# V4.net
KiCad netlist of a schematic drawn in Altium Designer
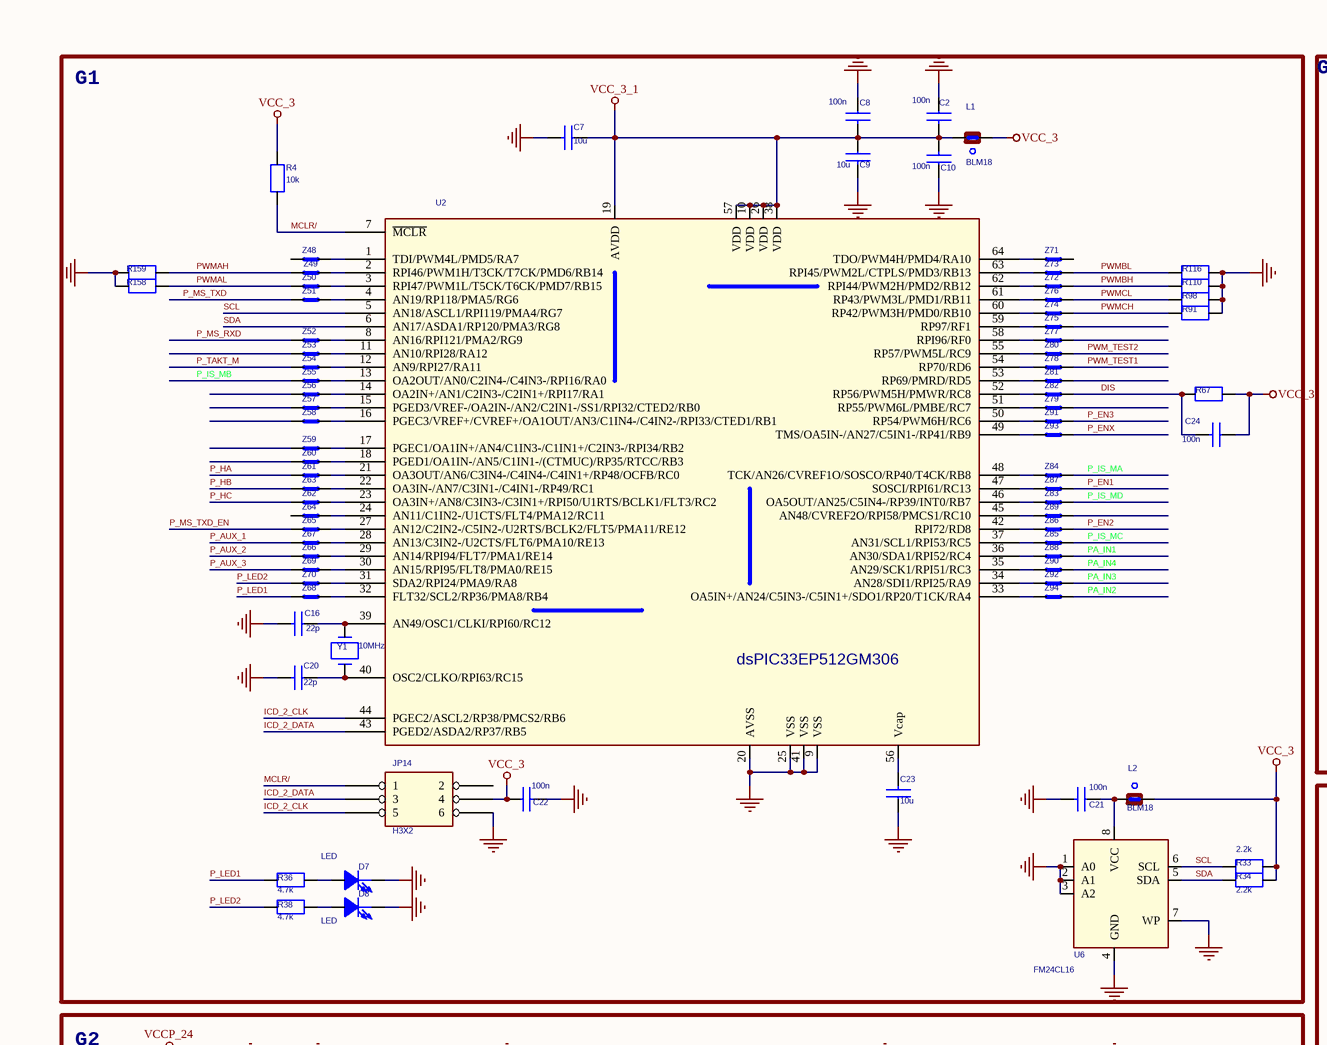
[diagram p0: V4.SchDoc, top left]
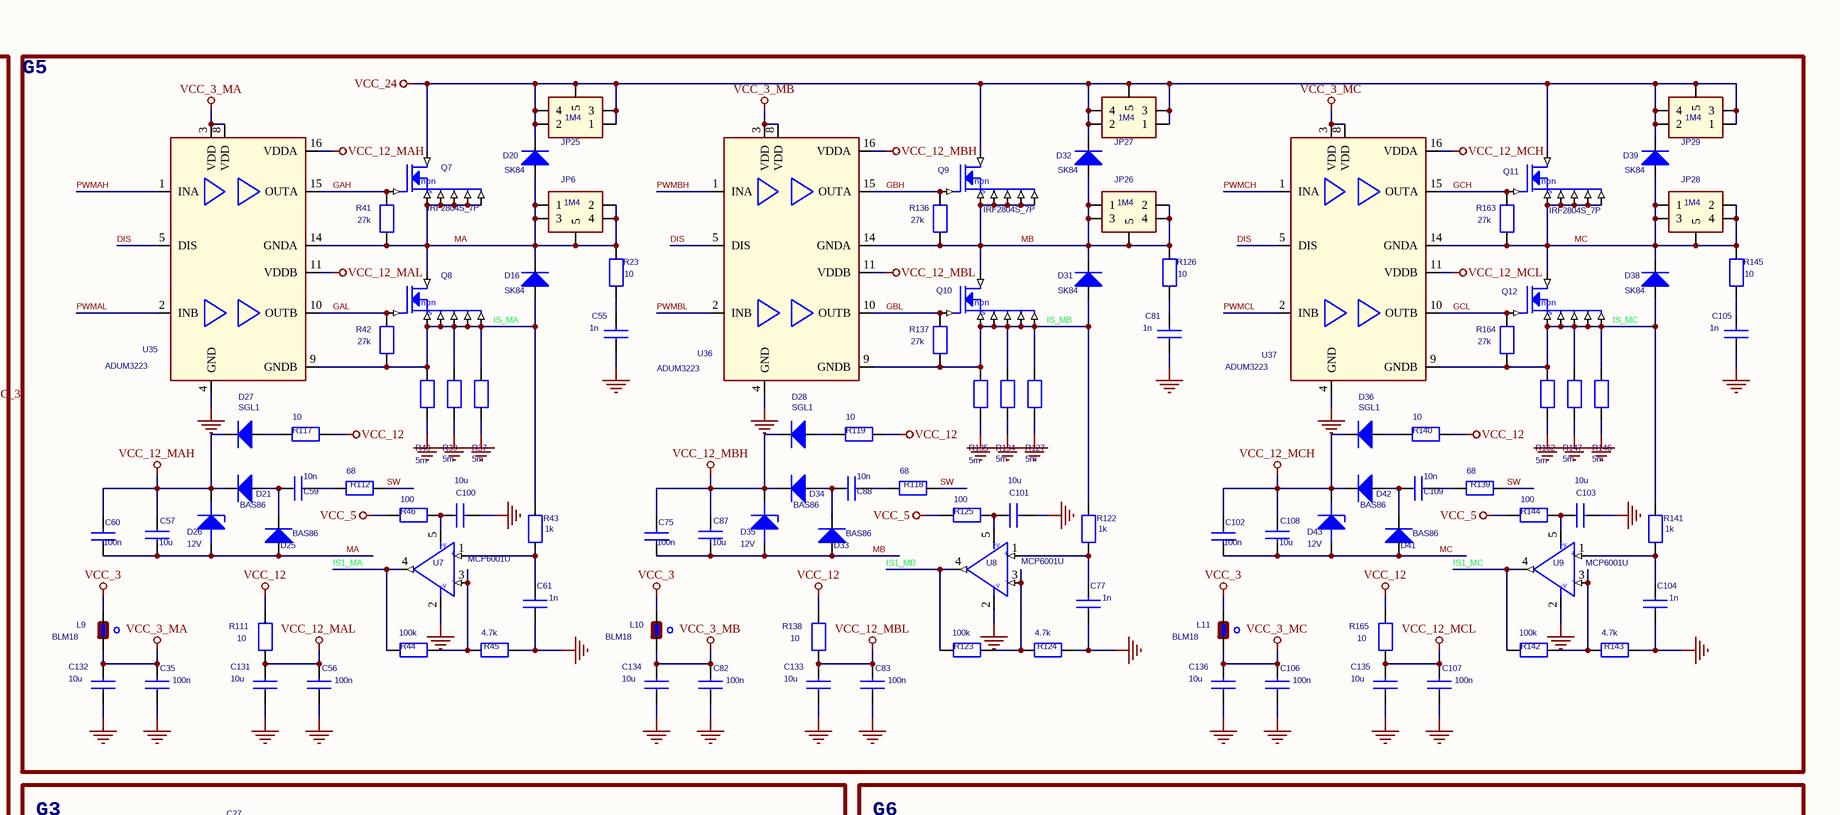
[diagram p1: V4.SchDoc, top right]
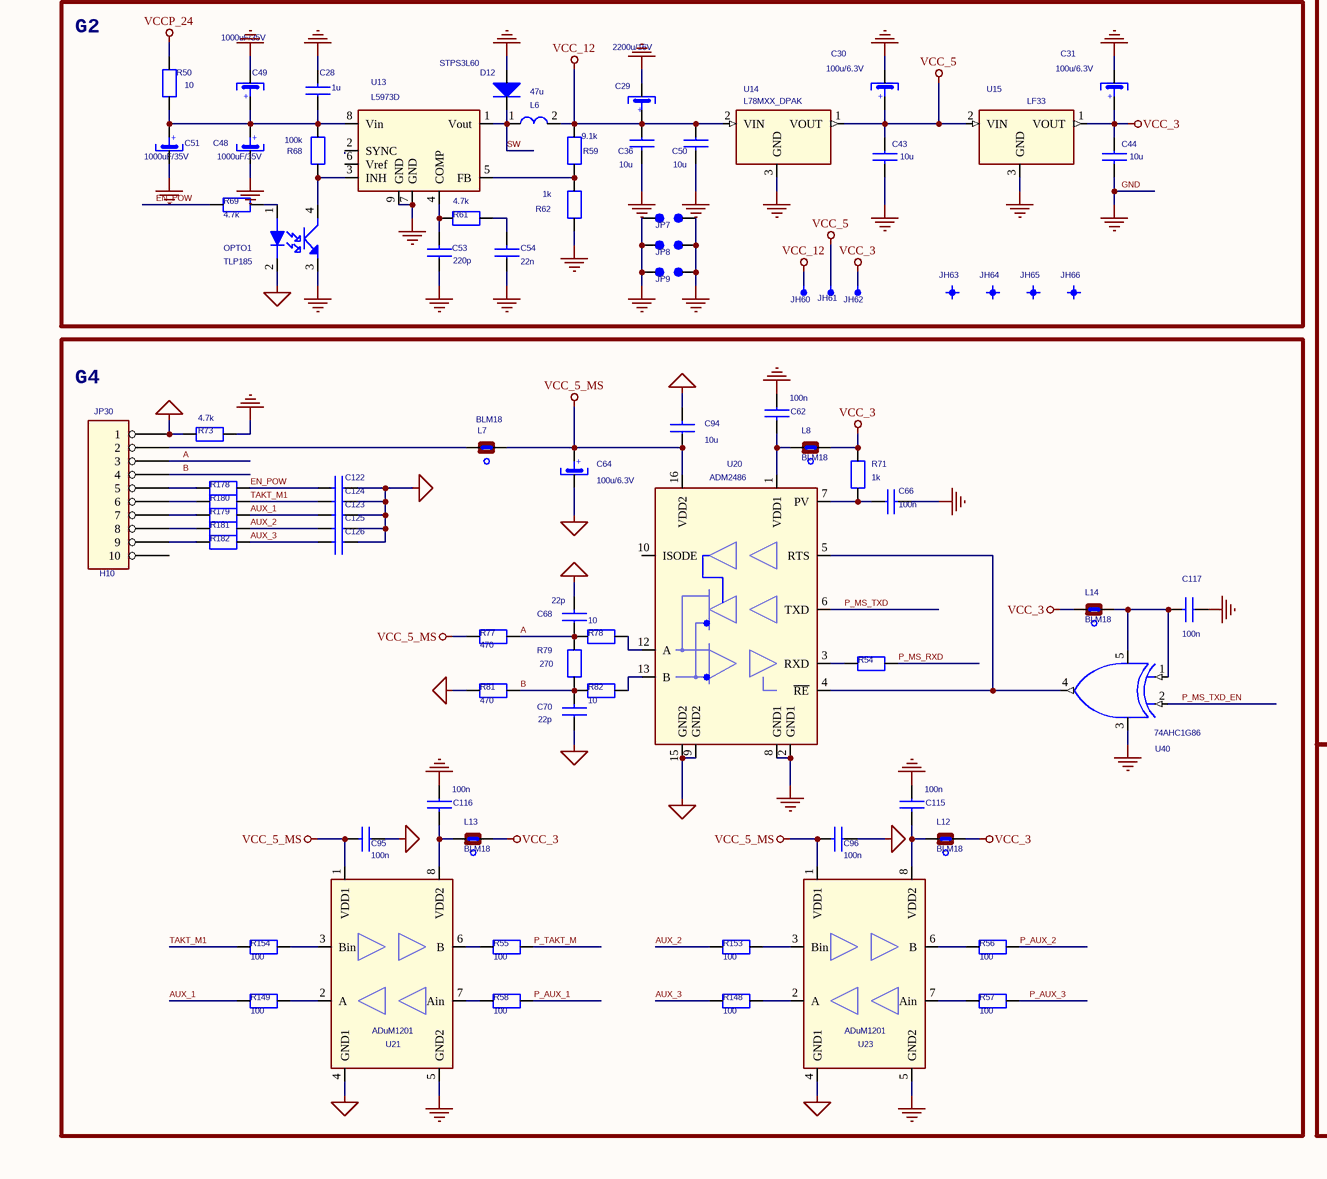
[diagram p2: V4.SchDoc, bottom left]
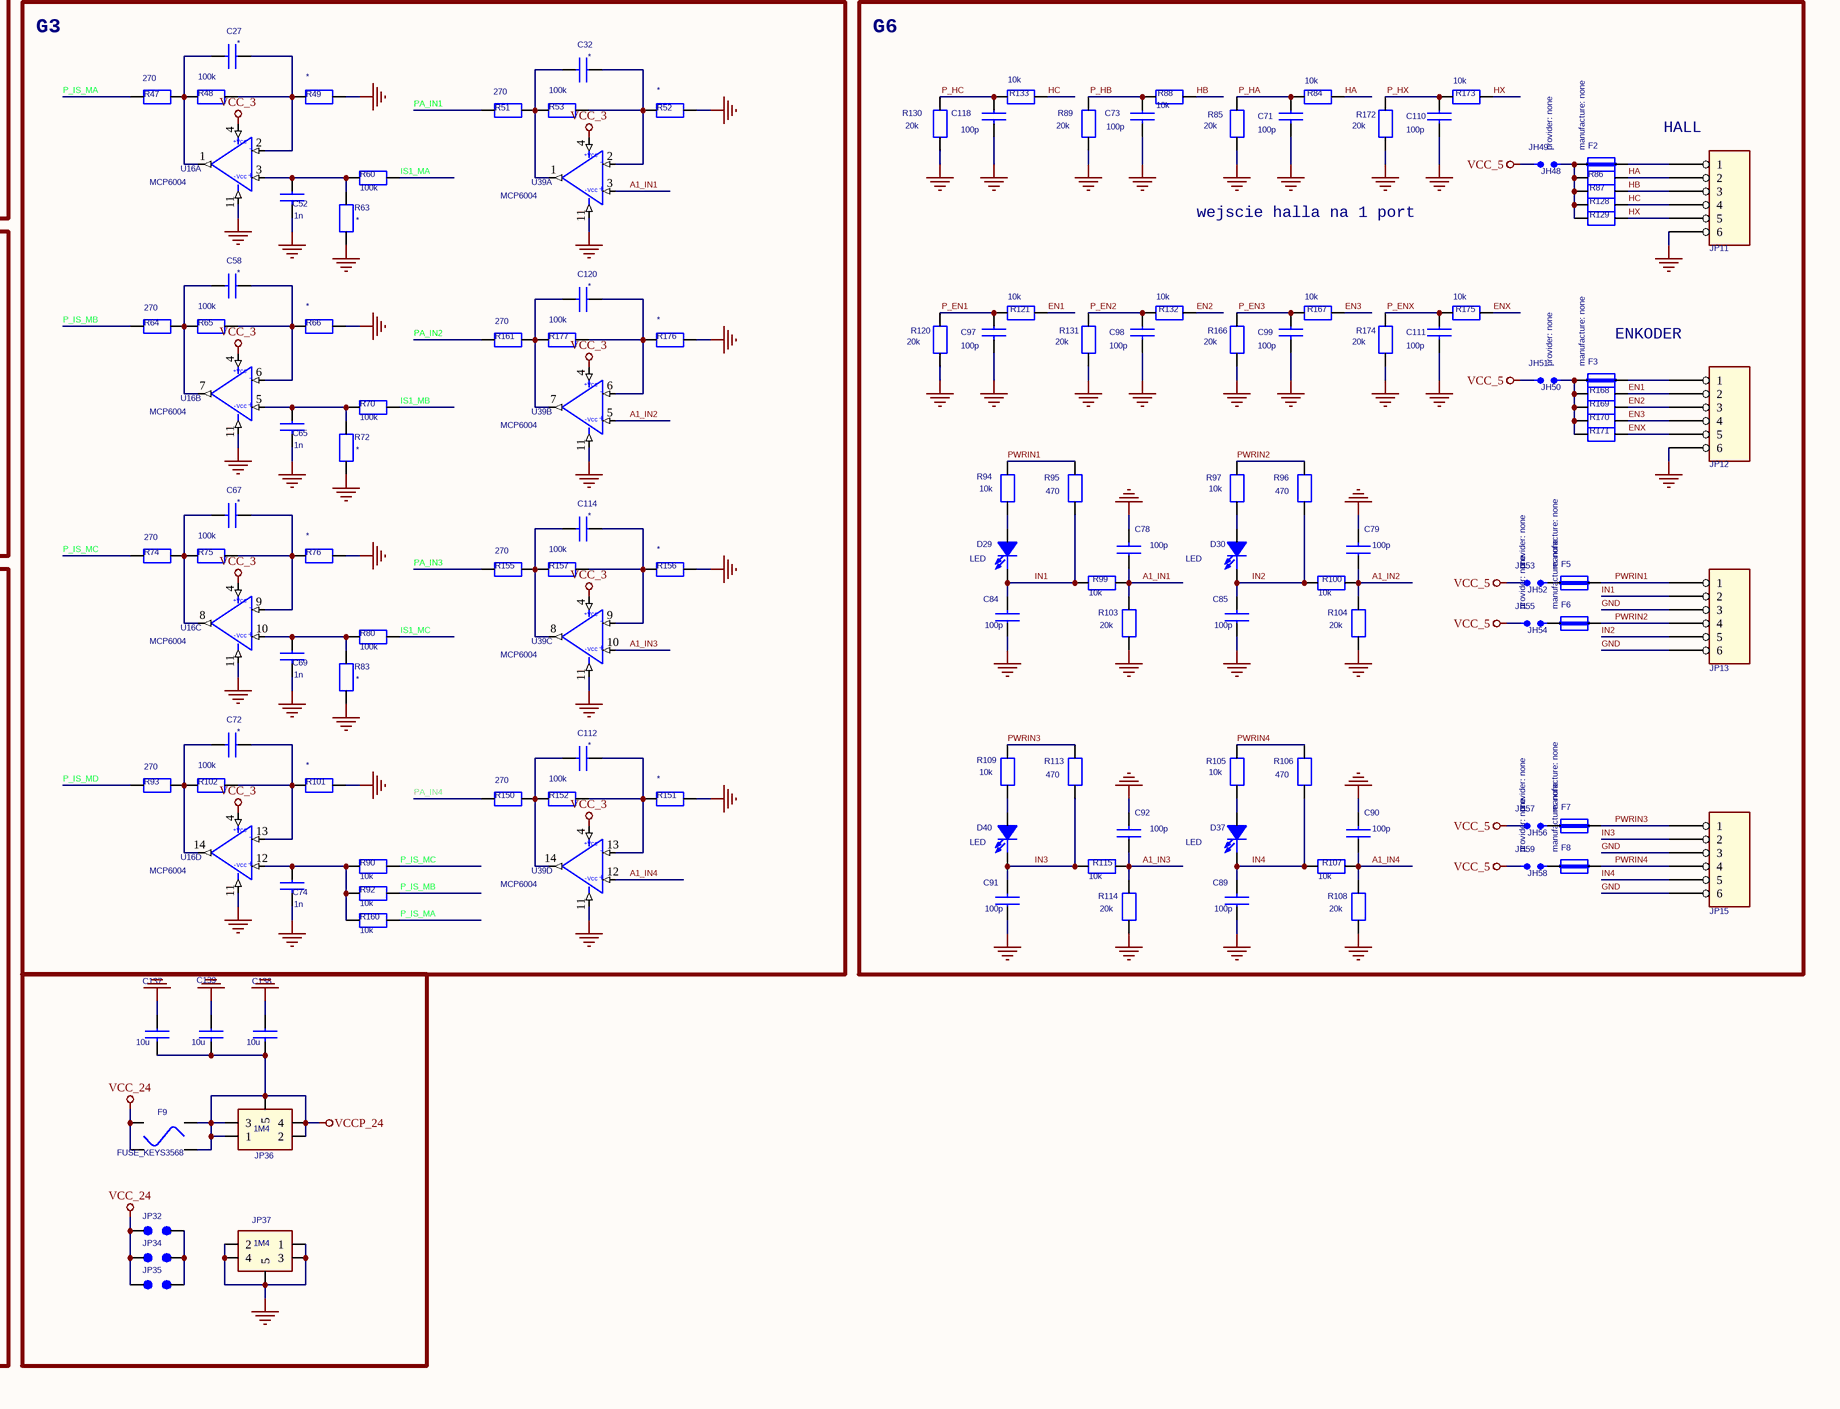
[diagram p3: V4.SchDoc, bottom right]

(export (version "E")
  (design (tool "Eeschema 10.0.6"))
  (components
    (comp (ref "C2")
      (value "100n")
      (footprint "0805")
      (description "100nF 0603 16V  X7R 10%")
      (fields (field (name "PROVIDER") "TME CL10B104KO8NNNC"))
      (libsource (lib "*") (part "C"))
    )
    (comp (ref "C7")
      (value "10u")
      (footprint "0805")
      (description "10uF 0603 6.3V 10% X5R")
      (fields (field (name "PROVIDER") "TME CL10A106KQ8NNNC"))
      (libsource (lib "*") (part "C"))
    )
    (comp (ref "C8") (value "100n") (footprint "0805") (libsource (lib "*") (part "C")))
    (comp (ref "C9")
      (value "10u")
      (footprint "0805")
      (description "10uF 0603 6.3V 10% X5R")
      (fields (field (name "PROVIDER") "TME CL10A106KQ8NNNC"))
      (libsource (lib "*") (part "C"))
    )
    (comp (ref "C10")
      (value "100n")
      (footprint "0805")
      (description "100nF 0603 16V  X7R 10%")
      (fields (field (name "PROVIDER") "TME CL10B104KO8NNNC"))
      (libsource (lib "*") (part "C"))
    )
    (comp (ref "C16")
      (value "22p")
      (footprint "0805")
      (description "22p 0603 50V C0G 5%")
      (fields (field (name "PROVIDER") "TME CL10C220JB8NNNC"))
      (libsource (lib "*") (part "C"))
    )
    (comp (ref "C20")
      (value "22p")
      (footprint "0805")
      (description "22p 0603 50V C0G 5%")
      (fields (field (name "PROVIDER") "TME CL10C220JB8NNNC"))
      (libsource (lib "*") (part "C"))
    )
    (comp (ref "C21") (value "100n") (footprint "0805") (libsource (lib "*") (part "C")))
    (comp (ref "C22")
      (value "100n")
      (footprint "0805")
      (description "100nF 0603 16V  X7R 10%")
      (fields (field (name "PROVIDER") "TME CL10B104KO8NNNC"))
      (libsource (lib "*") (part "C"))
    )
    (comp (ref "C23")
      (value "10u")
      (footprint "0805")
      (description "10uF 0603 6.3V 10% X5R")
      (fields (field (name "PROVIDER") "TME CL10A106KQ8NNNC"))
      (libsource (lib "*") (part "C"))
    )
    (comp (ref "C24") (value "100n") (footprint "0805") (libsource (lib "*") (part "C")))
    (comp (ref "C27")
      (value "*")
      (footprint "0805")
      (description "10nF 0603 50V X7R 10%")
      (fields (field (name "PROVIDER") "TME CL10B103KB8NNNC"))
      (libsource (lib "*") (part "C"))
    )
    (comp (ref "C28")
      (value "1u")
      (footprint "0805")
      (description "1u 1206 50V X7R 10%")
      (fields (field (name "PROVIDER") "TME CL31B105KBHNNNE"))
      (libsource (lib "*") (part "C"))
    )
    (comp (ref "C29")
      (value "2200u/16V")
      (description "2200u 16V LI 105C")
      (fields (field (name "PROVIDER") "TME GF2200/16"))
      (libsource (lib "*") (part "EL"))
    )
    (comp (ref "C30")
      (value "100u/6.3V")
      (description "100U 6.3V B LI 0.25")
      (fields (field (name "PROVIDER") "TME TPSB107K006R0250"))
      (libsource (lib "*") (part "EL"))
    )
    (comp (ref "C31")
      (value "100u/6.3V")
      (description "100U 6.3V B LI 0.25")
      (fields (field (name "PROVIDER") "TME TPSB107K006R0250"))
      (libsource (lib "*") (part "EL"))
    )
    (comp (ref "C32")
      (value "*")
      (footprint "0805")
      (description "10nF 0603 50V X7R 10%")
      (fields (field (name "PROVIDER") "TME CL10B103KB8NNNC"))
      (libsource (lib "*") (part "C"))
    )
    (comp (ref "C35") (value "100n") (footprint "0805") (libsource (lib "*") (part "C")))
    (comp (ref "C36") (value "10u") (footprint "0805") (libsource (lib "*") (part "C")))
    (comp (ref "C43")
      (value "10u")
      (footprint "0805")
      (description "10uF 0603 6.3V 10% X5R")
      (fields (field (name "PROVIDER") "TME CL10A106KQ8NNNC"))
      (libsource (lib "*") (part "C"))
    )
    (comp (ref "C44")
      (value "10u")
      (footprint "0805")
      (description "10uF 0603 6.3V 10% X5R")
      (fields (field (name "PROVIDER") "TME CL10A106KQ8NNNC"))
      (libsource (lib "*") (part "C"))
    )
    (comp (ref "C48")
      (value "1000uF/35V")
      (footprint "CE_16/RM7.5MM")
      (libsource (lib "*") (part "CE 2200uF/35V ST"))
    )
    (comp (ref "C49")
      (value "1000uF/35V")
      (footprint "CE_16/RM7.5MM")
      (libsource (lib "*") (part "CE 2200uF/35V ST"))
    )
    (comp (ref "C50") (value "10u") (footprint "0805") (libsource (lib "*") (part "C")))
    (comp (ref "C51")
      (value "1000uF/35V")
      (footprint "CE_16/RM7.5MM")
      (libsource (lib "*") (part "CE 2200uF/35V ST"))
    )
    (comp (ref "C52") (value "1n") (footprint "0805") (libsource (lib "*") (part "C")))
    (comp (ref "C53")
      (value "220p")
      (footprint "0805")
      (description "220p 0805 50V C0G 5%")
      (fields (field (name "PROVIDER") "TME CL21C221JBANNNC"))
      (libsource (lib "*") (part "C"))
    )
    (comp (ref "C54")
      (value "22n")
      (footprint "0805")
      (description "22n 0805 50V X7R 10%")
      (fields (field (name "PROVIDER") "TME CL21B223KBANNNC"))
      (libsource (lib "*") (part "C"))
    )
    (comp (ref "C55") (value "1n") (footprint "0805") (libsource (lib "*") (part "C")))
    (comp (ref "C56") (value "100n") (footprint "0805") (libsource (lib "*") (part "C")))
    (comp (ref "C57") (value "10u") (footprint "0805") (libsource (lib "*") (part "C")))
    (comp (ref "C58")
      (value "*")
      (footprint "0805")
      (description "10nF 0603 50V X7R 10%")
      (fields (field (name "PROVIDER") "TME CL10B103KB8NNNC"))
      (libsource (lib "*") (part "C"))
    )
    (comp (ref "C59") (value "10n") (footprint "0805") (libsource (lib "*") (part "C")))
    (comp (ref "C60") (value "100n") (footprint "0805") (libsource (lib "*") (part "C")))
    (comp (ref "C61")
      (value "1n")
      (footprint "0805")
      (description "1n 0603 50V 5% C0G")
      (fields (field (name "PROVIDER") "TME CL10C102JB8NNNC"))
      (libsource (lib "*") (part "C"))
    )
    (comp (ref "C62") (value "100n") (footprint "0805") (libsource (lib "*") (part "C")))
    (comp (ref "C64")
      (value "100u/6.3V")
      (description "100U 6.3V B LI 0.25")
      (fields (field (name "PROVIDER") "TME TPSB107K006R0250"))
      (libsource (lib "*") (part "EL"))
    )
    (comp (ref "C65") (value "1n") (footprint "0805") (libsource (lib "*") (part "C")))
    (comp (ref "C66") (value "100n") (footprint "0805") (libsource (lib "*") (part "C")))
    (comp (ref "C67")
      (value "*")
      (footprint "0805")
      (description "10nF 0603 50V X7R 10%")
      (fields (field (name "PROVIDER") "TME CL10B103KB8NNNC"))
      (libsource (lib "*") (part "C"))
    )
    (comp (ref "C68") (value "22p") (footprint "0805") (libsource (lib "*") (part "C")))
    (comp (ref "C69") (value "1n") (footprint "0805") (libsource (lib "*") (part "C")))
    (comp (ref "C70") (value "22p") (footprint "0805") (libsource (lib "*") (part "C")))
    (comp (ref "C71")
      (value "100p")
      (footprint "0805")
      (description "10nF 0603 50V X7R 10%")
      (fields (field (name "PROVIDER") "TME CL10B103KB8NNNC"))
      (libsource (lib "*") (part "C"))
    )
    (comp (ref "C72")
      (value "*")
      (footprint "0805")
      (description "10nF 0603 50V X7R 10%")
      (fields (field (name "PROVIDER") "TME CL10B103KB8NNNC"))
      (libsource (lib "*") (part "C"))
    )
    (comp (ref "C73")
      (value "100p")
      (footprint "0805")
      (description "10nF 0603 50V X7R 10%")
      (fields (field (name "PROVIDER") "TME CL10B103KB8NNNC"))
      (libsource (lib "*") (part "C"))
    )
    (comp (ref "C74") (value "1n") (footprint "0805") (libsource (lib "*") (part "C")))
    (comp (ref "C75") (value "100n") (footprint "0805") (libsource (lib "*") (part "C")))
    (comp (ref "C77")
      (value "1n")
      (footprint "0805")
      (description "1n 0603 50V 5% C0G")
      (fields (field (name "PROVIDER") "TME CL10C102JB8NNNC"))
      (libsource (lib "*") (part "C"))
    )
    (comp (ref "C78")
      (value "100p")
      (footprint "0805")
      (description "10nF 0603 50V X7R 10%")
      (fields (field (name "PROVIDER") "TME CL10B103KB8NNNC"))
      (libsource (lib "*") (part "C"))
    )
    (comp (ref "C79")
      (value "100p")
      (footprint "0805")
      (description "10nF 0603 50V X7R 10%")
      (fields (field (name "PROVIDER") "TME CL10B103KB8NNNC"))
      (libsource (lib "*") (part "C"))
    )
    (comp (ref "C81") (value "1n") (footprint "0805") (libsource (lib "*") (part "C")))
    (comp (ref "C82") (value "100n") (footprint "0805") (libsource (lib "*") (part "C")))
    (comp (ref "C83") (value "100n") (footprint "0805") (libsource (lib "*") (part "C")))
    (comp (ref "C84") (value "100p") (footprint "0805") (libsource (lib "*") (part "C")))
    (comp (ref "C85") (value "100p") (footprint "0805") (libsource (lib "*") (part "C")))
    (comp (ref "C87") (value "10u") (footprint "0805") (libsource (lib "*") (part "C")))
    (comp (ref "C88") (value "10n") (footprint "0805") (libsource (lib "*") (part "C")))
    (comp (ref "C89") (value "100p") (footprint "0805") (libsource (lib "*") (part "C")))
    (comp (ref "C90")
      (value "100p")
      (footprint "0805")
      (description "10nF 0603 50V X7R 10%")
      (fields (field (name "PROVIDER") "TME CL10B103KB8NNNC"))
      (libsource (lib "*") (part "C"))
    )
    (comp (ref "C91") (value "100p") (footprint "0805") (libsource (lib "*") (part "C")))
    (comp (ref "C92")
      (value "100p")
      (footprint "0805")
      (description "10nF 0603 50V X7R 10%")
      (fields (field (name "PROVIDER") "TME CL10B103KB8NNNC"))
      (libsource (lib "*") (part "C"))
    )
    (comp (ref "C94") (value "10u") (footprint "0805") (libsource (lib "*") (part "C")))
    (comp (ref "C95") (value "100n") (footprint "0805") (libsource (lib "*") (part "C")))
    (comp (ref "C96") (value "100n") (footprint "0805") (libsource (lib "*") (part "C")))
    (comp (ref "C97")
      (value "100p")
      (footprint "0805")
      (description "10nF 0603 50V X7R 10%")
      (fields (field (name "PROVIDER") "TME CL10B103KB8NNNC"))
      (libsource (lib "*") (part "C"))
    )
    (comp (ref "C98")
      (value "100p")
      (footprint "0805")
      (description "10nF 0603 50V X7R 10%")
      (fields (field (name "PROVIDER") "TME CL10B103KB8NNNC"))
      (libsource (lib "*") (part "C"))
    )
    (comp (ref "C99")
      (value "100p")
      (footprint "0805")
      (description "10nF 0603 50V X7R 10%")
      (fields (field (name "PROVIDER") "TME CL10B103KB8NNNC"))
      (libsource (lib "*") (part "C"))
    )
    (comp (ref "C100") (value "10u") (footprint "0805") (libsource (lib "*") (part "C")))
    (comp (ref "C101") (value "10u") (footprint "0805") (libsource (lib "*") (part "C")))
    (comp (ref "C102") (value "100n") (footprint "0805") (libsource (lib "*") (part "C")))
    (comp (ref "C103") (value "10u") (footprint "0805") (libsource (lib "*") (part "C")))
    (comp (ref "C104")
      (value "1n")
      (footprint "0805")
      (description "1n 0603 50V 5% C0G")
      (fields (field (name "PROVIDER") "TME CL10C102JB8NNNC"))
      (libsource (lib "*") (part "C"))
    )
    (comp (ref "C105") (value "1n") (footprint "0805") (libsource (lib "*") (part "C")))
    (comp (ref "C106") (value "100n") (footprint "0805") (libsource (lib "*") (part "C")))
    (comp (ref "C107") (value "100n") (footprint "0805") (libsource (lib "*") (part "C")))
    (comp (ref "C108") (value "10u") (footprint "0805") (libsource (lib "*") (part "C")))
    (comp (ref "C109") (value "10n") (footprint "0805") (libsource (lib "*") (part "C")))
    (comp (ref "C110")
      (value "100p")
      (footprint "0805")
      (description "10nF 0603 50V X7R 10%")
      (fields (field (name "PROVIDER") "TME CL10B103KB8NNNC"))
      (libsource (lib "*") (part "C"))
    )
    (comp (ref "C111")
      (value "100p")
      (footprint "0805")
      (description "10nF 0603 50V X7R 10%")
      (fields (field (name "PROVIDER") "TME CL10B103KB8NNNC"))
      (libsource (lib "*") (part "C"))
    )
    (comp (ref "C112")
      (value "*")
      (footprint "0805")
      (description "10nF 0603 50V X7R 10%")
      (fields (field (name "PROVIDER") "TME CL10B103KB8NNNC"))
      (libsource (lib "*") (part "C"))
    )
    (comp (ref "C114")
      (value "*")
      (footprint "0805")
      (description "10nF 0603 50V X7R 10%")
      (fields (field (name "PROVIDER") "TME CL10B103KB8NNNC"))
      (libsource (lib "*") (part "C"))
    )
    (comp (ref "C115") (value "100n") (footprint "0805") (libsource (lib "*") (part "C")))
    (comp (ref "C116") (value "100n") (footprint "0805") (libsource (lib "*") (part "C")))
    (comp (ref "C117") (value "100n") (footprint "0805") (libsource (lib "*") (part "C")))
    (comp (ref "C118")
      (value "100p")
      (footprint "0805")
      (description "10nF 0603 50V X7R 10%")
      (fields (field (name "PROVIDER") "TME CL10B103KB8NNNC"))
      (libsource (lib "*") (part "C"))
    )
    (comp (ref "C120")
      (value "*")
      (footprint "0805")
      (description "10nF 0603 50V X7R 10%")
      (fields (field (name "PROVIDER") "TME CL10B103KB8NNNC"))
      (libsource (lib "*") (part "C"))
    )
    (comp (ref "C122") (value "22p") (footprint "0805") (libsource (lib "*") (part "C")))
    (comp (ref "C123") (value "22p") (footprint "0805") (libsource (lib "*") (part "C")))
    (comp (ref "C124") (value "22p") (footprint "0805") (libsource (lib "*") (part "C")))
    (comp (ref "C125") (value "22p") (footprint "0805") (libsource (lib "*") (part "C")))
    (comp (ref "C126") (value "22p") (footprint "0805") (libsource (lib "*") (part "C")))
    (comp (ref "C131") (value "10u") (footprint "0805") (libsource (lib "*") (part "C")))
    (comp (ref "C132") (value "10u") (footprint "0805") (libsource (lib "*") (part "C")))
    (comp (ref "C133") (value "10u") (footprint "0805") (libsource (lib "*") (part "C")))
    (comp (ref "C134") (value "10u") (footprint "0805") (libsource (lib "*") (part "C")))
    (comp (ref "C135") (value "10u") (footprint "0805") (libsource (lib "*") (part "C")))
    (comp (ref "C136") (value "10u") (footprint "0805") (libsource (lib "*") (part "C")))
    (comp (ref "C137") (value "10u") (footprint "0805") (libsource (lib "*") (part "C")))
    (comp (ref "C138") (value "10u") (footprint "0805") (libsource (lib "*") (part "C")))
    (comp (ref "C139") (value "10u") (footprint "0805") (libsource (lib "*") (part "C")))
    (comp (ref "D7")
      (value "LED")
      (footprint "led5")
      (description "OSR50603C1C")
      (fields (field (name "PROVIDER") "TME  OSR50603C1C"))
      (libsource (lib "*") (part "LED"))
    )
    (comp (ref "D8")
      (value "LED")
      (footprint "led5")
      (description "OSR50603C1C")
      (fields (field (name "PROVIDER") "TME  OSR50603C1C"))
      (libsource (lib "*") (part "LED"))
    )
    (comp (ref "D12")
      (value "STPS3L60")
      (footprint "minimelf")
      (description "STPS3L60U")
      (fields (field (name "PROVIDER") "TME STPS3L60U"))
      (libsource (lib "*") (part "D"))
    )
    (comp (ref "D16") (value "SK84") (footprint "minimelf") (libsource (lib "*") (part "D")))
    (comp (ref "D20") (value "SK84") (footprint "minimelf") (libsource (lib "*") (part "D")))
    (comp (ref "D21")
      (value "BAS86")
      (footprint "minimelf")
      (fields (field (name "PROVIDER") "TME BAS86"))
      (libsource (lib "*") (part "D"))
    )
    (comp (ref "D25")
      (value "BAS86")
      (footprint "minimelf")
      (fields (field (name "PROVIDER") "TME BAS86"))
      (libsource (lib "*") (part "D"))
    )
    (comp (ref "D26") (value "12V") (footprint "D_minimelf") (libsource (lib "*") (part "DZ")))
    (comp (ref "D27")
      (value "SGL1")
      (footprint "minimelf")
      (fields (field (name "PROVIDER") "TME SGL1"))
      (libsource (lib "*") (part "D"))
    )
    (comp (ref "D28")
      (value "SGL1")
      (footprint "minimelf")
      (fields (field (name "PROVIDER") "TME SGL1"))
      (libsource (lib "*") (part "D"))
    )
    (comp (ref "D29")
      (value "LED")
      (footprint "led5")
      (description "OSR50603C1C")
      (fields (field (name "PROVIDER") "TME  OSR50603C1C"))
      (libsource (lib "*") (part "LED"))
    )
    (comp (ref "D30")
      (value "LED")
      (footprint "led5")
      (description "OSR50603C1C")
      (fields (field (name "PROVIDER") "TME  OSR50603C1C"))
      (libsource (lib "*") (part "LED"))
    )
    (comp (ref "D31") (value "SK84") (footprint "minimelf") (libsource (lib "*") (part "D")))
    (comp (ref "D32") (value "SK84") (footprint "minimelf") (libsource (lib "*") (part "D")))
    (comp (ref "D33")
      (value "BAS86")
      (footprint "minimelf")
      (fields (field (name "PROVIDER") "TME BAS86"))
      (libsource (lib "*") (part "D"))
    )
    (comp (ref "D34")
      (value "BAS86")
      (footprint "minimelf")
      (fields (field (name "PROVIDER") "TME BAS86"))
      (libsource (lib "*") (part "D"))
    )
    (comp (ref "D35") (value "12V") (footprint "D_minimelf") (libsource (lib "*") (part "DZ")))
    (comp (ref "D36")
      (value "SGL1")
      (footprint "minimelf")
      (fields (field (name "PROVIDER") "TME SGL1"))
      (libsource (lib "*") (part "D"))
    )
    (comp (ref "D37")
      (value "LED")
      (footprint "led5")
      (description "OSR50603C1C")
      (fields (field (name "PROVIDER") "TME  OSR50603C1C"))
      (libsource (lib "*") (part "LED"))
    )
    (comp (ref "D38") (value "SK84") (footprint "minimelf") (libsource (lib "*") (part "D")))
    (comp (ref "D39") (value "SK84") (footprint "minimelf") (libsource (lib "*") (part "D")))
    (comp (ref "D40")
      (value "LED")
      (footprint "led5")
      (description "OSR50603C1C")
      (fields (field (name "PROVIDER") "TME  OSR50603C1C"))
      (libsource (lib "*") (part "LED"))
    )
    (comp (ref "D41")
      (value "BAS86")
      (footprint "minimelf")
      (fields (field (name "PROVIDER") "TME BAS86"))
      (libsource (lib "*") (part "D"))
    )
    (comp (ref "D42")
      (value "BAS86")
      (footprint "minimelf")
      (fields (field (name "PROVIDER") "TME BAS86"))
      (libsource (lib "*") (part "D"))
    )
    (comp (ref "D43") (value "12V") (footprint "D_minimelf") (libsource (lib "*") (part "DZ")))
    (comp (ref "F2")
      (value "FUSE_PTC_1206")
      (footprint "1206")
      (description "none")
      (fields (field (name "MANUFACTURE") "none") (field (name "PROVIDER") "none"))
      (libsource (lib "*") (part "FUSE_PTC_1206"))
    )
    (comp (ref "F3")
      (value "FUSE_PTC_1206")
      (footprint "1206")
      (description "none")
      (fields (field (name "MANUFACTURE") "none") (field (name "PROVIDER") "none"))
      (libsource (lib "*") (part "FUSE_PTC_1206"))
    )
    (comp (ref "F5")
      (value "FUSE_PTC_1206")
      (footprint "1206")
      (description "none")
      (fields (field (name "MANUFACTURE") "none") (field (name "PROVIDER") "none"))
      (libsource (lib "*") (part "FUSE_PTC_1206"))
    )
    (comp (ref "F6")
      (value "FUSE_PTC_1206")
      (footprint "1206")
      (description "none")
      (fields (field (name "MANUFACTURE") "none") (field (name "PROVIDER") "none"))
      (libsource (lib "*") (part "FUSE_PTC_1206"))
    )
    (comp (ref "F7")
      (value "FUSE_PTC_1206")
      (footprint "1206")
      (description "none")
      (fields (field (name "MANUFACTURE") "none") (field (name "PROVIDER") "none"))
      (libsource (lib "*") (part "FUSE_PTC_1206"))
    )
    (comp (ref "F8")
      (value "FUSE_PTC_1206")
      (footprint "1206")
      (description "none")
      (fields (field (name "MANUFACTURE") "none") (field (name "PROVIDER") "none"))
      (libsource (lib "*") (part "FUSE_PTC_1206"))
    )
    (comp (ref "F9")
      (value "FUSE_KEYS3568")
      (footprint "FUSE_KEYS3557-2")
      (libsource (lib "*") (part "FUSE_KEYS3568_CAR"))
    )
    (comp (ref "JH48") (value "H1") (libsource (lib "*") (part "H1")))
    (comp (ref "JH49") (value "H1") (libsource (lib "*") (part "H1")))
    (comp (ref "JH50") (value "H1") (libsource (lib "*") (part "H1")))
    (comp (ref "JH51") (value "H1") (libsource (lib "*") (part "H1")))
    (comp (ref "JH52") (value "H1") (libsource (lib "*") (part "H1")))
    (comp (ref "JH53") (value "H1") (libsource (lib "*") (part "H1")))
    (comp (ref "JH54") (value "H1") (libsource (lib "*") (part "H1")))
    (comp (ref "JH55") (value "H1") (libsource (lib "*") (part "H1")))
    (comp (ref "JH56") (value "H1") (libsource (lib "*") (part "H1")))
    (comp (ref "JH57") (value "H1") (libsource (lib "*") (part "H1")))
    (comp (ref "JH58") (value "H1") (libsource (lib "*") (part "H1")))
    (comp (ref "JH59") (value "H1") (libsource (lib "*") (part "H1")))
    (comp (ref "JH60") (value "H1") (libsource (lib "*") (part "H1")))
    (comp (ref "JH61") (value "H1") (libsource (lib "*") (part "H1")))
    (comp (ref "JH62") (value "H1") (libsource (lib "*") (part "H1")))
    (comp (ref "JH63") (value "HOLE_4MM") (footprint "SMD_CENT1") (libsource (lib "*") (part "SRUBA_3MM")))
    (comp (ref "JH64") (value "HOLE_4MM") (footprint "SMD_CENT1") (libsource (lib "*") (part "SRUBA_3MM")))
    (comp (ref "JH65") (value "HOLE_4MM") (footprint "SMD_CENT1") (libsource (lib "*") (part "SRUBA_3MM")))
    (comp (ref "JH66") (value "HOLE_4MM") (footprint "SMD_CENT1") (libsource (lib "*") (part "SRUBA_3MM")))
    (comp (ref "JP6")
      (value "1M4")
      (fields (field (name "PROVIDER") "TME 1M4"))
      (libsource (lib "*") (part "PCB-1M4"))
    )
    (comp (ref "JP7") (value "JUMPER") (libsource (lib "*") (part "JUMPER")))
    (comp (ref "JP8") (value "JUMPER") (libsource (lib "*") (part "JUMPER")))
    (comp (ref "JP9") (value "JUMPER") (libsource (lib "*") (part "JUMPER")))
    (comp (ref "JP11") (value "H6") (libsource (lib "*") (part "H6")))
    (comp (ref "JP12") (value "H6") (libsource (lib "*") (part "H6")))
    (comp (ref "JP13") (value "H6") (libsource (lib "*") (part "H6")))
    (comp (ref "JP14") (value "H3X2") (libsource (lib "*") (part "H3X2")))
    (comp (ref "JP15") (value "H6") (libsource (lib "*") (part "H6")))
    (comp (ref "JP25")
      (value "1M4")
      (fields (field (name "PROVIDER") "TME 1M4"))
      (libsource (lib "") (part "PCB-1M4_2"))
    )
    (comp (ref "JP26")
      (value "1M4")
      (fields (field (name "PROVIDER") "TME 1M4"))
      (libsource (lib "*") (part "PCB-1M4"))
    )
    (comp (ref "JP27")
      (value "1M4")
      (fields (field (name "PROVIDER") "TME 1M4"))
      (libsource (lib "") (part "PCB-1M4_2"))
    )
    (comp (ref "JP28")
      (value "1M4")
      (fields (field (name "PROVIDER") "TME 1M4"))
      (libsource (lib "*") (part "PCB-1M4"))
    )
    (comp (ref "JP29")
      (value "1M4")
      (fields (field (name "PROVIDER") "TME 1M4"))
      (libsource (lib "") (part "PCB-1M4_2"))
    )
    (comp (ref "JP30") (value "H10") (libsource (lib "*") (part "H10")))
    (comp (ref "JP32") (value "JUMPER") (libsource (lib "*") (part "JUMPER")))
    (comp (ref "JP34") (value "JUMPER") (libsource (lib "*") (part "JUMPER")))
    (comp (ref "JP35") (value "JUMPER") (libsource (lib "*") (part "JUMPER")))
    (comp (ref "JP36")
      (value "1M4")
      (fields (field (name "PROVIDER") "TME 1M4"))
      (libsource (lib "") (part "PCB-1M4_1"))
    )
    (comp (ref "JP37")
      (value "1M4")
      (fields (field (name "PROVIDER") "TME 1M4"))
      (libsource (lib "") (part "PCB-1M4_3"))
    )
    (comp (ref "L1")
      (value "BLM18")
      (footprint "0603")
      (fields (field (name "PROVIDER") "TME LCBA-601"))
      (libsource (lib "*") (part "BLM18"))
    )
    (comp (ref "L2")
      (value "BLM18")
      (footprint "0603")
      (fields (field (name "PROVIDER") "TME LCBA-601"))
      (libsource (lib "") (part "BLM18_2"))
    )
    (comp (ref "L6")
      (value "47u")
      (footprint "L10")
      (description "47u 1205 3A")
      (fields (field (name "PROVIDER") "TME DE1205-47"))
      (libsource (lib "*") (part "L"))
    )
    (comp (ref "L7")
      (value "BLM18")
      (footprint "0603")
      (fields (field (name "PROVIDER") "TME LCBA-601"))
      (libsource (lib "*") (part "BLM18"))
    )
    (comp (ref "L8") (value "BLM18") (footprint "0603") (libsource (lib "*") (part "BLM18")))
    (comp (ref "L9")
      (value "BLM18")
      (footprint "0603")
      (fields (field (name "PROVIDER") "TME LCBA-601"))
      (libsource (lib "") (part "BLM18_1"))
    )
    (comp (ref "L10")
      (value "BLM18")
      (footprint "0603")
      (fields (field (name "PROVIDER") "TME LCBA-601"))
      (libsource (lib "") (part "BLM18_1"))
    )
    (comp (ref "L11")
      (value "BLM18")
      (footprint "0603")
      (fields (field (name "PROVIDER") "TME LCBA-601"))
      (libsource (lib "") (part "BLM18_1"))
    )
    (comp (ref "L12") (value "BLM18") (footprint "0603") (libsource (lib "*") (part "BLM18")))
    (comp (ref "L13") (value "BLM18") (footprint "0603") (libsource (lib "*") (part "BLM18")))
    (comp (ref "L14") (value "BLM18") (footprint "0603") (libsource (lib "*") (part "BLM18")))
    (comp (ref "OPTO1")
      (value "TLP185")
      (footprint "SMDIP4")
      (libsource (lib "*") (part "OPTO_TLP185_SMDIP4"))
    )
    (comp (ref "Q7") (value "IRF2804S_7P") (footprint "D2PAK_7P") (libsource (lib "*") (part "IRF2804S_7P")))
    (comp (ref "Q8") (value "IRF2804S_7P") (footprint "D2PAK_7P") (libsource (lib "*") (part "IRF2804S_7P")))
    (comp (ref "Q9") (value "IRF2804S_7P") (footprint "D2PAK_7P") (libsource (lib "*") (part "IRF2804S_7P")))
    (comp (ref "Q10") (value "IRF2804S_7P") (footprint "D2PAK_7P") (libsource (lib "*") (part "IRF2804S_7P")))
    (comp (ref "Q11") (value "IRF2804S_7P") (footprint "D2PAK_7P") (libsource (lib "*") (part "IRF2804S_7P")))
    (comp (ref "Q12") (value "IRF2804S_7P") (footprint "D2PAK_7P") (libsource (lib "*") (part "IRF2804S_7P")))
    (comp (ref "R4")
      (value "10k")
      (footprint "0805")
      (description "10k 0603")
      (fields (field (name "PROVIDER") "TME SMD0603-10K-1%"))
      (libsource (lib "*") (part "R"))
    )
    (comp (ref "R23") (value "10") (footprint "0805") (libsource (lib "*") (part "R")))
    (comp (ref "R33")
      (value "2.2k")
      (footprint "0805")
      (description "2.2k 0603")
      (libsource (lib "*") (part "R"))
    )
    (comp (ref "R34")
      (value "2.2k")
      (footprint "0805")
      (description "2.2k 0603")
      (libsource (lib "*") (part "R"))
    )
    (comp (ref "R36")
      (value "4.7k")
      (footprint "0805")
      (description "4.7k 0805")
      (fields (field (name "PROVIDER") "TME SMD0805-4K7-1%"))
      (libsource (lib "*") (part "R"))
    )
    (comp (ref "R37") (value "5m") (footprint "0805") (libsource (lib "*") (part "R")))
    (comp (ref "R38")
      (value "4.7k")
      (footprint "0805")
      (description "4.7k 0805")
      (fields (field (name "PROVIDER") "TME SMD0805-4K7-1%"))
      (libsource (lib "*") (part "R"))
    )
    (comp (ref "R39") (value "5m") (footprint "0805") (libsource (lib "*") (part "R")))
    (comp (ref "R40") (value "5m") (footprint "0805") (libsource (lib "*") (part "R")))
    (comp (ref "R41") (value "27k") (footprint "0805") (libsource (lib "*") (part "R")))
    (comp (ref "R42") (value "27k") (footprint "0805") (libsource (lib "*") (part "R")))
    (comp (ref "R43") (value "1k") (footprint "0805") (libsource (lib "*") (part "R")))
    (comp (ref "R44")
      (value "100k")
      (footprint "0805")
      (description "100k 0805")
      (fields (field (name "PROVIDER") "TME SMD0805-100K-1%"))
      (libsource (lib "*") (part "R"))
    )
    (comp (ref "R45")
      (value "4.7k")
      (footprint "0805")
      (description "100k 0805")
      (fields (field (name "PROVIDER") "TME SMD0805-100K-1%"))
      (libsource (lib "*") (part "R"))
    )
    (comp (ref "R46") (value "100") (footprint "0805") (libsource (lib "*") (part "R")))
    (comp (ref "R47")
      (value "270")
      (footprint "0805")
      (description "270 0603")
      (libsource (lib "*") (part "R"))
    )
    (comp (ref "R48")
      (value "100k")
      (footprint "0805")
      (description "100k 0805")
      (fields (field (name "PROVIDER") "TME SMD0805-100K-1%"))
      (libsource (lib "*") (part "R"))
    )
    (comp (ref "R49")
      (value "*")
      (footprint "0805")
      (description "100k 0805")
      (fields (field (name "PROVIDER") "TME SMD0805-100K-1%"))
      (libsource (lib "*") (part "R"))
    )
    (comp (ref "R50")
      (value "10")
      (footprint "0805")
      (description "10   2010")
      (libsource (lib "*") (part "R"))
    )
    (comp (ref "R51")
      (value "270")
      (footprint "0805")
      (description "270 0603")
      (libsource (lib "*") (part "R"))
    )
    (comp (ref "R52")
      (value "*")
      (footprint "0805")
      (description "100k 0805")
      (fields (field (name "PROVIDER") "TME SMD0805-100K-1%"))
      (libsource (lib "*") (part "R"))
    )
    (comp (ref "R53")
      (value "100k")
      (footprint "0805")
      (description "100k 0805")
      (fields (field (name "PROVIDER") "TME SMD0805-100K-1%"))
      (libsource (lib "*") (part "R"))
    )
    (comp (ref "R54") (value "100") (footprint "0805") (libsource (lib "*") (part "R")))
    (comp (ref "R55") (value "100") (footprint "0805") (libsource (lib "*") (part "R")))
    (comp (ref "R56") (value "100") (footprint "0805") (libsource (lib "*") (part "R")))
    (comp (ref "R57") (value "100") (footprint "0805") (libsource (lib "*") (part "R")))
    (comp (ref "R58") (value "100") (footprint "0805") (libsource (lib "*") (part "R")))
    (comp (ref "R59")
      (value "9.1k")
      (footprint "0805")
      (description "9.1k 0805 1%")
      (fields (field (name "PROVIDER") "TME SMD0805-9K1-1%"))
      (libsource (lib "*") (part "R"))
    )
    (comp (ref "R60")
      (value "100k")
      (footprint "0805")
      (description "100k 0805")
      (fields (field (name "PROVIDER") "TME SMD0805-100K-1%"))
      (libsource (lib "*") (part "R"))
    )
    (comp (ref "R61")
      (value "4.7k")
      (footprint "0805")
      (description "4.7k 0805")
      (fields (field (name "PROVIDER") "TME SMD0805-4K7-1%"))
      (libsource (lib "*") (part "R"))
    )
    (comp (ref "R62")
      (value "1k")
      (footprint "0805")
      (description "1k 0805 1%")
      (fields (field (name "PROVIDER") "TME SMD0805-1K-1%"))
      (libsource (lib "*") (part "R"))
    )
    (comp (ref "R63")
      (value "*")
      (footprint "0805")
      (description "68k 0805")
      (fields (field (name "PROVIDER") "TME SMD0805-68K-1%"))
      (libsource (lib "*") (part "R"))
    )
    (comp (ref "R64")
      (value "270")
      (footprint "0805")
      (description "270 0603")
      (libsource (lib "*") (part "R"))
    )
    (comp (ref "R65")
      (value "100k")
      (footprint "0805")
      (description "100k 0805")
      (fields (field (name "PROVIDER") "TME SMD0805-100K-1%"))
      (libsource (lib "*") (part "R"))
    )
    (comp (ref "R66")
      (value "*")
      (footprint "0805")
      (description "100k 0805")
      (fields (field (name "PROVIDER") "TME SMD0805-100K-1%"))
      (libsource (lib "*") (part "R"))
    )
    (comp (ref "R67") (value "10k") (footprint "0805") (libsource (lib "*") (part "R")))
    (comp (ref "R68")
      (value "100k")
      (footprint "0805")
      (description "9.1k 0805 1%")
      (fields (field (name "PROVIDER") "TME SMD0805-9K1-1%"))
      (libsource (lib "*") (part "R"))
    )
    (comp (ref "R69")
      (value "4.7k")
      (footprint "0805")
      (description "4.7k 0805")
      (fields (field (name "PROVIDER") "TME SMD0805-4K7-1%"))
      (libsource (lib "*") (part "R"))
    )
    (comp (ref "R70")
      (value "100k")
      (footprint "0805")
      (description "100k 0805")
      (fields (field (name "PROVIDER") "TME SMD0805-100K-1%"))
      (libsource (lib "*") (part "R"))
    )
    (comp (ref "R71")
      (value "1k")
      (footprint "0805")
      (description "1k 0805 1%")
      (fields (field (name "PROVIDER") "TME SMD0805-1K-1%"))
      (libsource (lib "*") (part "R"))
    )
    (comp (ref "R72")
      (value "*")
      (footprint "0805")
      (description "68k 0805")
      (fields (field (name "PROVIDER") "TME SMD0805-68K-1%"))
      (libsource (lib "*") (part "R"))
    )
    (comp (ref "R73")
      (value "4.7k")
      (footprint "0805")
      (description "4.7k 0805")
      (fields (field (name "PROVIDER") "TME SMD0805-4K7-1%"))
      (libsource (lib "*") (part "R"))
    )
    (comp (ref "R74")
      (value "270")
      (footprint "0805")
      (description "270 0603")
      (libsource (lib "*") (part "R"))
    )
    (comp (ref "R75")
      (value "100k")
      (footprint "0805")
      (description "100k 0805")
      (fields (field (name "PROVIDER") "TME SMD0805-100K-1%"))
      (libsource (lib "*") (part "R"))
    )
    (comp (ref "R76")
      (value "*")
      (footprint "0805")
      (description "100k 0805")
      (fields (field (name "PROVIDER") "TME SMD0805-100K-1%"))
      (libsource (lib "*") (part "R"))
    )
    (comp (ref "R77")
      (value "470")
      (footprint "0805")
      (description "4.7k 0805")
      (fields (field (name "PROVIDER") "TME SMD0805-4K7-1%"))
      (libsource (lib "*") (part "R"))
    )
    (comp (ref "R78")
      (value "10")
      (footprint "0805")
      (description "4.7k 0805")
      (fields (field (name "PROVIDER") "TME SMD0805-4K7-1%"))
      (libsource (lib "*") (part "R"))
    )
    (comp (ref "R79")
      (value "270")
      (footprint "0805")
      (description "4.7k 0805")
      (fields (field (name "PROVIDER") "TME SMD0805-4K7-1%"))
      (libsource (lib "*") (part "R"))
    )
    (comp (ref "R80")
      (value "100k")
      (footprint "0805")
      (description "100k 0805")
      (fields (field (name "PROVIDER") "TME SMD0805-100K-1%"))
      (libsource (lib "*") (part "R"))
    )
    (comp (ref "R81")
      (value "470")
      (footprint "0805")
      (description "4.7k 0805")
      (fields (field (name "PROVIDER") "TME SMD0805-4K7-1%"))
      (libsource (lib "*") (part "R"))
    )
    (comp (ref "R82")
      (value "10")
      (footprint "0805")
      (description "4.7k 0805")
      (fields (field (name "PROVIDER") "TME SMD0805-4K7-1%"))
      (libsource (lib "*") (part "R"))
    )
    (comp (ref "R83")
      (value "*")
      (footprint "0805")
      (description "68k 0805")
      (fields (field (name "PROVIDER") "TME SMD0805-68K-1%"))
      (libsource (lib "*") (part "R"))
    )
    (comp (ref "R84") (value "10k") (footprint "0805") (libsource (lib "*") (part "R")))
    (comp (ref "R85") (value "20k") (footprint "0805") (libsource (lib "*") (part "R")))
    (comp (ref "R86") (value "470") (footprint "0805") (libsource (lib "*") (part "R")))
    (comp (ref "R87") (value "470") (footprint "0805") (libsource (lib "*") (part "R")))
    (comp (ref "R88") (value "10k") (footprint "0805") (libsource (lib "*") (part "R")))
    (comp (ref "R89") (value "20k") (footprint "0805") (libsource (lib "*") (part "R")))
    (comp (ref "R90") (value "10k") (footprint "0805") (libsource (lib "*") (part "R")))
    (comp (ref "R91") (value "10k") (footprint "0805") (libsource (lib "*") (part "R")))
    (comp (ref "R92") (value "10k") (footprint "0805") (libsource (lib "*") (part "R")))
    (comp (ref "R93")
      (value "270")
      (footprint "0805")
      (description "270 0603")
      (libsource (lib "*") (part "R"))
    )
    (comp (ref "R94")
      (value "10k")
      (footprint "0805")
      (description "10k 0603")
      (fields (field (name "PROVIDER") "TME SMD0603-10K-1%"))
      (libsource (lib "*") (part "R"))
    )
    (comp (ref "R95")
      (value "470")
      (footprint "0805")
      (description "470 1206 1% HP06")
      (fields (field (name "PROVIDER") "TME  HP06-470R1%"))
      (libsource (lib "*") (part "R"))
    )
    (comp (ref "R96")
      (value "470")
      (footprint "0805")
      (description "470 1206 1% HP06")
      (fields (field (name "PROVIDER") "TME  HP06-470R1%"))
      (libsource (lib "*") (part "R"))
    )
    (comp (ref "R97")
      (value "10k")
      (footprint "0805")
      (description "10k 0603")
      (fields (field (name "PROVIDER") "TME SMD0603-10K-1%"))
      (libsource (lib "*") (part "R"))
    )
    (comp (ref "R98") (value "10k") (footprint "0805") (libsource (lib "*") (part "R")))
    (comp (ref "R99") (value "10k") (footprint "0805") (libsource (lib "*") (part "R")))
    (comp (ref "R100") (value "10k") (footprint "0805") (libsource (lib "*") (part "R")))
    (comp (ref "R101")
      (value "*")
      (footprint "0805")
      (description "100k 0805")
      (fields (field (name "PROVIDER") "TME SMD0805-100K-1%"))
      (libsource (lib "*") (part "R"))
    )
    (comp (ref "R102")
      (value "100k")
      (footprint "0805")
      (description "100k 0805")
      (fields (field (name "PROVIDER") "TME SMD0805-100K-1%"))
      (libsource (lib "*") (part "R"))
    )
    (comp (ref "R103") (value "20k") (footprint "0805") (libsource (lib "*") (part "R")))
    (comp (ref "R104") (value "20k") (footprint "0805") (libsource (lib "*") (part "R")))
    (comp (ref "R105")
      (value "10k")
      (footprint "0805")
      (description "10k 0603")
      (fields (field (name "PROVIDER") "TME SMD0603-10K-1%"))
      (libsource (lib "*") (part "R"))
    )
    (comp (ref "R106")
      (value "470")
      (footprint "0805")
      (description "470 1206 1% HP06")
      (fields (field (name "PROVIDER") "TME  HP06-470R1%"))
      (libsource (lib "*") (part "R"))
    )
    (comp (ref "R107") (value "10k") (footprint "0805") (libsource (lib "*") (part "R")))
    (comp (ref "R108") (value "20k") (footprint "0805") (libsource (lib "*") (part "R")))
    (comp (ref "R109")
      (value "10k")
      (footprint "0805")
      (description "10k 0603")
      (fields (field (name "PROVIDER") "TME SMD0603-10K-1%"))
      (libsource (lib "*") (part "R"))
    )
    (comp (ref "R110") (value "10k") (footprint "0805") (libsource (lib "*") (part "R")))
    (comp (ref "R111") (value "10") (footprint "0805") (libsource (lib "*") (part "R")))
    (comp (ref "R112") (value "68") (footprint "0805") (libsource (lib "*") (part "R")))
    (comp (ref "R113")
      (value "470")
      (footprint "0805")
      (description "470 1206 1% HP06")
      (fields (field (name "PROVIDER") "TME  HP06-470R1%"))
      (libsource (lib "*") (part "R"))
    )
    (comp (ref "R114") (value "20k") (footprint "0805") (libsource (lib "*") (part "R")))
    (comp (ref "R115") (value "10k") (footprint "0805") (libsource (lib "*") (part "R")))
    (comp (ref "R116") (value "10k") (footprint "0805") (libsource (lib "*") (part "R")))
    (comp (ref "R117") (value "10") (footprint "0805") (libsource (lib "*") (part "R")))
    (comp (ref "R118") (value "68") (footprint "0805") (libsource (lib "*") (part "R")))
    (comp (ref "R119") (value "10") (footprint "0805") (libsource (lib "*") (part "R")))
    (comp (ref "R120") (value "20k") (footprint "0805") (libsource (lib "*") (part "R")))
    (comp (ref "R121") (value "10k") (footprint "0805") (libsource (lib "*") (part "R")))
    (comp (ref "R122") (value "1k") (footprint "0805") (libsource (lib "*") (part "R")))
    (comp (ref "R123")
      (value "100k")
      (footprint "0805")
      (description "100k 0805")
      (fields (field (name "PROVIDER") "TME SMD0805-100K-1%"))
      (libsource (lib "*") (part "R"))
    )
    (comp (ref "R124")
      (value "4.7k")
      (footprint "0805")
      (description "100k 0805")
      (fields (field (name "PROVIDER") "TME SMD0805-100K-1%"))
      (libsource (lib "*") (part "R"))
    )
    (comp (ref "R125") (value "100") (footprint "0805") (libsource (lib "*") (part "R")))
    (comp (ref "R126") (value "10") (footprint "0805") (libsource (lib "*") (part "R")))
    (comp (ref "R127") (value "5m") (footprint "0805") (libsource (lib "*") (part "R")))
    (comp (ref "R128") (value "470") (footprint "0805") (libsource (lib "*") (part "R")))
    (comp (ref "R129") (value "470") (footprint "0805") (libsource (lib "*") (part "R")))
    (comp (ref "R130") (value "20k") (footprint "0805") (libsource (lib "*") (part "R")))
    (comp (ref "R131") (value "20k") (footprint "0805") (libsource (lib "*") (part "R")))
    (comp (ref "R132") (value "10k") (footprint "0805") (libsource (lib "*") (part "R")))
    (comp (ref "R133") (value "10k") (footprint "0805") (libsource (lib "*") (part "R")))
    (comp (ref "R134") (value "5m") (footprint "0805") (libsource (lib "*") (part "R")))
    (comp (ref "R135") (value "5m") (footprint "0805") (libsource (lib "*") (part "R")))
    (comp (ref "R136") (value "27k") (footprint "0805") (libsource (lib "*") (part "R")))
    (comp (ref "R137") (value "27k") (footprint "0805") (libsource (lib "*") (part "R")))
    (comp (ref "R138") (value "10") (footprint "0805") (libsource (lib "*") (part "R")))
    (comp (ref "R139") (value "68") (footprint "0805") (libsource (lib "*") (part "R")))
    (comp (ref "R140") (value "10") (footprint "0805") (libsource (lib "*") (part "R")))
    (comp (ref "R141") (value "1k") (footprint "0805") (libsource (lib "*") (part "R")))
    (comp (ref "R142")
      (value "100k")
      (footprint "0805")
      (description "100k 0805")
      (fields (field (name "PROVIDER") "TME SMD0805-100K-1%"))
      (libsource (lib "*") (part "R"))
    )
    (comp (ref "R143")
      (value "4.7k")
      (footprint "0805")
      (description "100k 0805")
      (fields (field (name "PROVIDER") "TME SMD0805-100K-1%"))
      (libsource (lib "*") (part "R"))
    )
    (comp (ref "R144") (value "100") (footprint "0805") (libsource (lib "*") (part "R")))
    (comp (ref "R145") (value "10") (footprint "0805") (libsource (lib "*") (part "R")))
    (comp (ref "R146") (value "5m") (footprint "0805") (libsource (lib "*") (part "R")))
    (comp (ref "R147") (value "5m") (footprint "0805") (libsource (lib "*") (part "R")))
    (comp (ref "R148") (value "100") (footprint "0805") (libsource (lib "*") (part "R")))
    (comp (ref "R149") (value "100") (footprint "0805") (libsource (lib "*") (part "R")))
    (comp (ref "R150")
      (value "270")
      (footprint "0805")
      (description "270 0603")
      (libsource (lib "*") (part "R"))
    )
    (comp (ref "R151")
      (value "*")
      (footprint "0805")
      (description "100k 0805")
      (fields (field (name "PROVIDER") "TME SMD0805-100K-1%"))
      (libsource (lib "*") (part "R"))
    )
    (comp (ref "R152")
      (value "100k")
      (footprint "0805")
      (description "100k 0805")
      (fields (field (name "PROVIDER") "TME SMD0805-100K-1%"))
      (libsource (lib "*") (part "R"))
    )
    (comp (ref "R153") (value "100") (footprint "0805") (libsource (lib "*") (part "R")))
    (comp (ref "R154") (value "100") (footprint "0805") (libsource (lib "*") (part "R")))
    (comp (ref "R155")
      (value "270")
      (footprint "0805")
      (description "270 0603")
      (libsource (lib "*") (part "R"))
    )
    (comp (ref "R156")
      (value "*")
      (footprint "0805")
      (description "100k 0805")
      (fields (field (name "PROVIDER") "TME SMD0805-100K-1%"))
      (libsource (lib "*") (part "R"))
    )
    (comp (ref "R157")
      (value "100k")
      (footprint "0805")
      (description "100k 0805")
      (fields (field (name "PROVIDER") "TME SMD0805-100K-1%"))
      (libsource (lib "*") (part "R"))
    )
    (comp (ref "R158") (value "10k") (footprint "0805") (libsource (lib "*") (part "R")))
    (comp (ref "R159") (value "10k") (footprint "0805") (libsource (lib "*") (part "R")))
    (comp (ref "R160") (value "10k") (footprint "0805") (libsource (lib "*") (part "R")))
    (comp (ref "R161")
      (value "270")
      (footprint "0805")
      (description "270 0603")
      (libsource (lib "*") (part "R"))
    )
    (comp (ref "R162") (value "5m") (footprint "0805") (libsource (lib "*") (part "R")))
    (comp (ref "R163") (value "27k") (footprint "0805") (libsource (lib "*") (part "R")))
    (comp (ref "R164") (value "27k") (footprint "0805") (libsource (lib "*") (part "R")))
    (comp (ref "R165") (value "10") (footprint "0805") (libsource (lib "*") (part "R")))
    (comp (ref "R166") (value "20k") (footprint "0805") (libsource (lib "*") (part "R")))
    (comp (ref "R167") (value "10k") (footprint "0805") (libsource (lib "*") (part "R")))
    (comp (ref "R168") (value "470") (footprint "0805") (libsource (lib "*") (part "R")))
    (comp (ref "R169") (value "470") (footprint "0805") (libsource (lib "*") (part "R")))
    (comp (ref "R170") (value "470") (footprint "0805") (libsource (lib "*") (part "R")))
    (comp (ref "R171") (value "470") (footprint "0805") (libsource (lib "*") (part "R")))
    (comp (ref "R172") (value "20k") (footprint "0805") (libsource (lib "*") (part "R")))
    (comp (ref "R173") (value "10k") (footprint "0805") (libsource (lib "*") (part "R")))
    (comp (ref "R174") (value "20k") (footprint "0805") (libsource (lib "*") (part "R")))
    (comp (ref "R175") (value "10k") (footprint "0805") (libsource (lib "*") (part "R")))
    (comp (ref "R176")
      (value "*")
      (footprint "0805")
      (description "100k 0805")
      (fields (field (name "PROVIDER") "TME SMD0805-100K-1%"))
      (libsource (lib "*") (part "R"))
    )
    (comp (ref "R177")
      (value "100k")
      (footprint "0805")
      (description "100k 0805")
      (fields (field (name "PROVIDER") "TME SMD0805-100K-1%"))
      (libsource (lib "*") (part "R"))
    )
    (comp (ref "R178") (value "100") (footprint "0805") (libsource (lib "*") (part "R")))
    (comp (ref "R179") (value "100") (footprint "0805") (libsource (lib "*") (part "R")))
    (comp (ref "R180") (value "100") (footprint "0805") (libsource (lib "*") (part "R")))
    (comp (ref "R181") (value "100") (footprint "0805") (libsource (lib "*") (part "R")))
    (comp (ref "R182") (value "100") (footprint "0805") (libsource (lib "*") (part "R")))
    (comp (ref "U2")
      (value "dsPIC33EP512GM306")
      (footprint "TQFP64/0.50MM")
      (libsource (lib "*") (part "dsPIC33EP512GM306_QFN64_B"))
    )
    (comp (ref "U6")
      (value "FM24CL16")
      (footprint "SOIC8")
      (description "FM24CL16B-GTR")
      (fields (field (name "PROVIDER") "TME FM24CL16B-GTR"))
      (libsource (lib "*") (part "24LC64"))
    )
    (comp (ref "U7")
      (value "MCP6001U")
      (footprint "SOT23-5")
      (libsource (lib "*") (part "OP_MCP6001U_SOT23-5"))
    )
    (comp (ref "U8")
      (value "MCP6001U")
      (footprint "SOT23-5")
      (libsource (lib "*") (part "OP_MCP6001U_SOT23-5"))
    )
    (comp (ref "U9")
      (value "MCP6001U")
      (footprint "SOT23-5")
      (libsource (lib "*") (part "OP_MCP6001U_SOT23-5"))
    )
    (comp (ref "U13")
      (value "L5973D")
      (footprint "SOIC8_PWR1")
      (libsource (lib "*") (part "L5973D_SOIC8_PWR1"))
    )
    (comp (ref "U14") (value "L78MXX_DPAK") (footprint "DPAK") (libsource (lib "*") (part "L78MXX_DPAK")))
    (comp (ref "U15")
      (value "LF33")
      (footprint "DPAK")
      (description "LF33CDT")
      (fields (field (name "PROVIDER") "TME LF33CDT"))
      (libsource (lib "*") (part "LFxx_DPAK"))
    )
    (comp (ref "U16")
      (value "MCP6004")
      (footprint "SOIC14")
      (description "MCP6004-I/SL")
      (fields (field (name "PROVIDER") "TMP MCP6004-I/SL"))
      (libsource (lib "*") (part "324"))
    )
    (comp (ref "U20")
      (value "ADM2486")
      (footprint "SOIC16M")
      (libsource (lib "*") (part "RS485_ISOL_ADM2486_SOIC16M"))
    )
    (comp (ref "U21")
      (value "ADuM1201")
      (footprint "SOIC8")
      (libsource (lib "*") (part "ISOL_ADuM1201_SOIC8"))
    )
    (comp (ref "U23")
      (value "ADuM1201")
      (footprint "SOIC8")
      (libsource (lib "*") (part "ISOL_ADuM1201_SOIC8"))
    )
    (comp (ref "U35")
      (value "ADUM3223")
      (footprint "SOIC16")
      (libsource (lib "*") (part "ISOL_MOS_DRV_ADUM3223_SOIC16"))
    )
    (comp (ref "U36")
      (value "ADUM3223")
      (footprint "SOIC16")
      (libsource (lib "*") (part "ISOL_MOS_DRV_ADUM3223_SOIC16"))
    )
    (comp (ref "U37")
      (value "ADUM3223")
      (footprint "SOIC16")
      (libsource (lib "*") (part "ISOL_MOS_DRV_ADUM3223_SOIC16"))
    )
    (comp (ref "U39")
      (value "MCP6004")
      (footprint "SOIC14")
      (description "MCP6004-I/SL")
      (fields (field (name "PROVIDER") "TMP MCP6004-I/SL"))
      (libsource (lib "*") (part "324"))
    )
    (comp (ref "U40") (value "74AHC1G86") (footprint "SOT23") (libsource (lib "*") (part "74_1G86_SOT23")))
    (comp (ref "Y1")
      (value "10MHz")
      (footprint "QS")
      (description "KWARC 10MHz")
      (fields (field (name "PROVIDER") "TME 10.00M-HC49-S"))
      (libsource (lib "*") (part "QS"))
    )
    (comp (ref "Z48") (value "ZWTP") (footprint "ZWTP") (libsource (lib "*") (part "ZWTP")))
    (comp (ref "Z49") (value "ZWTP") (footprint "ZWTP") (libsource (lib "*") (part "ZWTP")))
    (comp (ref "Z50") (value "ZWTP") (footprint "ZWTP") (libsource (lib "*") (part "ZWTP")))
    (comp (ref "Z51") (value "ZWTP") (footprint "ZWTP") (libsource (lib "*") (part "ZWTP")))
    (comp (ref "Z52") (value "ZWTP") (footprint "ZWTP") (libsource (lib "*") (part "ZWTP")))
    (comp (ref "Z53") (value "ZWTP") (footprint "ZWTP") (libsource (lib "*") (part "ZWTP")))
    (comp (ref "Z54") (value "ZWTP") (footprint "ZWTP") (libsource (lib "*") (part "ZWTP")))
    (comp (ref "Z55") (value "ZWTP") (footprint "ZWTP") (libsource (lib "*") (part "ZWTP")))
    (comp (ref "Z56") (value "ZWTP") (footprint "ZWTP") (libsource (lib "*") (part "ZWTP")))
    (comp (ref "Z57") (value "ZWTP") (footprint "ZWTP") (libsource (lib "*") (part "ZWTP")))
    (comp (ref "Z58") (value "ZWTP") (footprint "ZWTP") (libsource (lib "*") (part "ZWTP")))
    (comp (ref "Z59") (value "ZWTP") (footprint "ZWTP") (libsource (lib "*") (part "ZWTP")))
    (comp (ref "Z60") (value "ZWTP") (footprint "ZWTP") (libsource (lib "*") (part "ZWTP")))
    (comp (ref "Z61") (value "ZWTP") (footprint "ZWTP") (libsource (lib "*") (part "ZWTP")))
    (comp (ref "Z62") (value "ZWTP") (footprint "ZWTP") (libsource (lib "*") (part "ZWTP")))
    (comp (ref "Z63") (value "ZWTP") (footprint "ZWTP") (libsource (lib "*") (part "ZWTP")))
    (comp (ref "Z64") (value "ZWTP") (footprint "ZWTP") (libsource (lib "*") (part "ZWTP")))
    (comp (ref "Z65") (value "ZWTP") (footprint "ZWTP") (libsource (lib "*") (part "ZWTP")))
    (comp (ref "Z66") (value "ZWTP") (footprint "ZWTP") (libsource (lib "*") (part "ZWTP")))
    (comp (ref "Z67") (value "ZWTP") (footprint "ZWTP") (libsource (lib "*") (part "ZWTP")))
    (comp (ref "Z68") (value "ZWTP") (footprint "ZWTP") (libsource (lib "*") (part "ZWTP")))
    (comp (ref "Z69") (value "ZWTP") (footprint "ZWTP") (libsource (lib "*") (part "ZWTP")))
    (comp (ref "Z70") (value "ZWTP") (footprint "ZWTP") (libsource (lib "*") (part "ZWTP")))
    (comp (ref "Z71") (value "ZWTP") (footprint "ZWTP") (libsource (lib "*") (part "ZWTP")))
    (comp (ref "Z72") (value "ZWTP") (footprint "ZWTP") (libsource (lib "*") (part "ZWTP")))
    (comp (ref "Z73") (value "ZWTP") (footprint "ZWTP") (libsource (lib "*") (part "ZWTP")))
    (comp (ref "Z74") (value "ZWTP") (footprint "ZWTP") (libsource (lib "*") (part "ZWTP")))
    (comp (ref "Z75") (value "ZWTP") (footprint "ZWTP") (libsource (lib "*") (part "ZWTP")))
    (comp (ref "Z76") (value "ZWTP") (footprint "ZWTP") (libsource (lib "*") (part "ZWTP")))
    (comp (ref "Z77") (value "ZWTP") (footprint "ZWTP") (libsource (lib "*") (part "ZWTP")))
    (comp (ref "Z78") (value "ZWTP") (footprint "ZWTP") (libsource (lib "*") (part "ZWTP")))
    (comp (ref "Z79") (value "ZWTP") (footprint "ZWTP") (libsource (lib "*") (part "ZWTP")))
    (comp (ref "Z80") (value "ZWTP") (footprint "ZWTP") (libsource (lib "*") (part "ZWTP")))
    (comp (ref "Z81") (value "ZWTP") (footprint "ZWTP") (libsource (lib "*") (part "ZWTP")))
    (comp (ref "Z82") (value "ZWTP") (footprint "ZWTP") (libsource (lib "*") (part "ZWTP")))
    (comp (ref "Z83") (value "ZWTP") (footprint "ZWTP") (libsource (lib "*") (part "ZWTP")))
    (comp (ref "Z84") (value "ZWTP") (footprint "ZWTP") (libsource (lib "*") (part "ZWTP")))
    (comp (ref "Z85") (value "ZWTP") (footprint "ZWTP") (libsource (lib "*") (part "ZWTP")))
    (comp (ref "Z86") (value "ZWTP") (footprint "ZWTP") (libsource (lib "*") (part "ZWTP")))
    (comp (ref "Z87") (value "ZWTP") (footprint "ZWTP") (libsource (lib "*") (part "ZWTP")))
    (comp (ref "Z88") (value "ZWTP") (footprint "ZWTP") (libsource (lib "*") (part "ZWTP")))
    (comp (ref "Z89") (value "ZWTP") (footprint "ZWTP") (libsource (lib "*") (part "ZWTP")))
    (comp (ref "Z90") (value "ZWTP") (footprint "ZWTP") (libsource (lib "*") (part "ZWTP")))
    (comp (ref "Z91") (value "ZWTP") (footprint "ZWTP") (libsource (lib "*") (part "ZWTP")))
    (comp (ref "Z92") (value "ZWTP") (footprint "ZWTP") (libsource (lib "*") (part "ZWTP")))
    (comp (ref "Z93") (value "ZWTP") (footprint "ZWTP") (libsource (lib "*") (part "ZWTP")))
    (comp (ref "Z94") (value "ZWTP") (footprint "ZWTP") (libsource (lib "*") (part "ZWTP")))
  )
  (nets
    (net (code "1") (name "/A") (class "Default")
      (node (ref "C68") (pin "1") (pinfunction "1_1") (pintype "passive"))
      (node (ref "JP30") (pin "3") (pinfunction "3_3") (pintype "passive"))
      (node (ref "R77") (pin "1") (pinfunction "1_1") (pintype "passive"))
      (node (ref "R78") (pin "2") (pinfunction "2_2") (pintype "passive"))
      (node (ref "R79") (pin "2") (pinfunction "2_2") (pintype "passive"))
    )
    (net (code "2") (name "/A1_IN1") (class "Default")
      (node (ref "C78") (pin "1") (pinfunction "1_1") (pintype "passive"))
      (node (ref "R103") (pin "2") (pinfunction "2_2") (pintype "passive"))
      (node (ref "R99") (pin "1") (pinfunction "1_1") (pintype "passive"))
      (node (ref "U39") (pin "3") (pinfunction "IN+_3") (pintype "input"))
    )
    (net (code "3") (name "/A1_IN2") (class "Default")
      (node (ref "C79") (pin "1") (pinfunction "1_1") (pintype "passive"))
      (node (ref "R100") (pin "1") (pinfunction "1_1") (pintype "passive"))
      (node (ref "R104") (pin "2") (pinfunction "2_2") (pintype "passive"))
      (node (ref "U39") (pin "5") (pinfunction "IN+_5") (pintype "input"))
    )
    (net (code "4") (name "/A1_IN3") (class "Default")
      (node (ref "C92") (pin "1") (pinfunction "1_1") (pintype "passive"))
      (node (ref "R114") (pin "2") (pinfunction "2_2") (pintype "passive"))
      (node (ref "R115") (pin "1") (pinfunction "1_1") (pintype "passive"))
      (node (ref "U39") (pin "10") (pinfunction "IN+_10") (pintype "input"))
    )
    (net (code "5") (name "/A1_IN4") (class "Default")
      (node (ref "C90") (pin "1") (pinfunction "1_1") (pintype "passive"))
      (node (ref "R107") (pin "1") (pinfunction "1_1") (pintype "passive"))
      (node (ref "R108") (pin "2") (pinfunction "2_2") (pintype "passive"))
      (node (ref "U39") (pin "12") (pinfunction "IN+_12") (pintype "input"))
    )
    (net (code "6") (name "/AUX_1") (class "Default")
      (node (ref "C123") (pin "2") (pinfunction "2_2") (pintype "passive"))
      (node (ref "R149") (pin "2") (pinfunction "2_2") (pintype "passive"))
      (node (ref "R179") (pin "1") (pinfunction "1_1") (pintype "passive"))
    )
    (net (code "7") (name "/AUX_2") (class "Default")
      (node (ref "C125") (pin "2") (pinfunction "2_2") (pintype "passive"))
      (node (ref "R153") (pin "2") (pinfunction "2_2") (pintype "passive"))
      (node (ref "R181") (pin "1") (pinfunction "1_1") (pintype "passive"))
    )
    (net (code "8") (name "/AUX_3") (class "Default")
      (node (ref "C126") (pin "2") (pinfunction "2_2") (pintype "passive"))
      (node (ref "R148") (pin "2") (pinfunction "2_2") (pintype "passive"))
      (node (ref "R182") (pin "1") (pinfunction "1_1") (pintype "passive"))
    )
    (net (code "9") (name "/B") (class "Default")
      (node (ref "C70") (pin "2") (pinfunction "2_2") (pintype "passive"))
      (node (ref "JP30") (pin "4") (pinfunction "4_4") (pintype "passive"))
      (node (ref "R79") (pin "1") (pinfunction "1_1") (pintype "passive"))
      (node (ref "R81") (pin "1") (pinfunction "1_1") (pintype "passive"))
      (node (ref "R82") (pin "2") (pinfunction "2_2") (pintype "passive"))
    )
    (net (code "10") (name "/DIS") (class "Default")
      (node (ref "C24") (pin "2") (pinfunction "2_2") (pintype "passive"))
      (node (ref "R67") (pin "1") (pinfunction "1_1") (pintype "passive"))
      (node (ref "U35") (pin "5") (pinfunction "DIS_5") (pintype "passive"))
      (node (ref "U36") (pin "5") (pinfunction "DIS_5") (pintype "passive"))
      (node (ref "U37") (pin "5") (pinfunction "DIS_5") (pintype "passive"))
      (node (ref "Z82") (pin "2") (pinfunction "2_2") (pintype "passive"))
    )
    (net (code "11") (name "/EN1") (class "Default")
      (node (ref "JP12") (pin "2") (pinfunction "2_2") (pintype "passive"))
      (node (ref "R121") (pin "1") (pinfunction "1_1") (pintype "passive"))
      (node (ref "R168") (pin "1") (pinfunction "1_1") (pintype "passive"))
    )
    (net (code "12") (name "/EN2") (class "Default")
      (node (ref "JP12") (pin "3") (pinfunction "3_3") (pintype "passive"))
      (node (ref "R132") (pin "1") (pinfunction "1_1") (pintype "passive"))
      (node (ref "R169") (pin "1") (pinfunction "1_1") (pintype "passive"))
    )
    (net (code "13") (name "/EN3") (class "Default")
      (node (ref "JP12") (pin "4") (pinfunction "4_4") (pintype "passive"))
      (node (ref "R167") (pin "1") (pinfunction "1_1") (pintype "passive"))
      (node (ref "R170") (pin "1") (pinfunction "1_1") (pintype "passive"))
    )
    (net (code "14") (name "/ENX") (class "Default")
      (node (ref "JP12") (pin "5") (pinfunction "5_5") (pintype "passive"))
      (node (ref "R171") (pin "1") (pinfunction "1_1") (pintype "passive"))
      (node (ref "R175") (pin "1") (pinfunction "1_1") (pintype "passive"))
    )
    (net (code "15") (name "/EN_POW") (class "Default")
      (node (ref "C122") (pin "2") (pinfunction "2_2") (pintype "passive"))
      (node (ref "R178") (pin "1") (pinfunction "1_1") (pintype "passive"))
      (node (ref "R69") (pin "1") (pinfunction "1_1") (pintype "passive"))
    )
    (net (code "16") (name "/GAH") (class "Default")
      (node (ref "Q7") (pin "1") (pinfunction "1_1") (pintype "input"))
      (node (ref "R41") (pin "2") (pinfunction "2_2") (pintype "passive"))
      (node (ref "U35") (pin "15") (pinfunction "OUTA_15") (pintype "passive"))
    )
    (net (code "17") (name "/GAL") (class "Default")
      (node (ref "Q8") (pin "1") (pinfunction "1_1") (pintype "input"))
      (node (ref "R42") (pin "1") (pinfunction "1_1") (pintype "passive"))
      (node (ref "U35") (pin "10") (pinfunction "OUTB_10") (pintype "passive"))
    )
    (net (code "18") (name "/GBH") (class "Default")
      (node (ref "Q9") (pin "1") (pinfunction "1_1") (pintype "input"))
      (node (ref "R136") (pin "2") (pinfunction "2_2") (pintype "passive"))
      (node (ref "U36") (pin "15") (pinfunction "OUTA_15") (pintype "passive"))
    )
    (net (code "19") (name "/GBL") (class "Default")
      (node (ref "Q10") (pin "1") (pinfunction "1_1") (pintype "input"))
      (node (ref "R137") (pin "1") (pinfunction "1_1") (pintype "passive"))
      (node (ref "U36") (pin "10") (pinfunction "OUTB_10") (pintype "passive"))
    )
    (net (code "20") (name "/GCH") (class "Default")
      (node (ref "Q11") (pin "1") (pinfunction "1_1") (pintype "input"))
      (node (ref "R163") (pin "2") (pinfunction "2_2") (pintype "passive"))
      (node (ref "U37") (pin "15") (pinfunction "OUTA_15") (pintype "passive"))
    )
    (net (code "21") (name "/GCL") (class "Default")
      (node (ref "Q12") (pin "1") (pinfunction "1_1") (pintype "input"))
      (node (ref "R164") (pin "1") (pinfunction "1_1") (pintype "passive"))
      (node (ref "U37") (pin "10") (pinfunction "OUTB_10") (pintype "passive"))
    )
    (net (code "22") (name "/HA") (class "Default")
      (node (ref "JP11") (pin "2") (pinfunction "2_2") (pintype "passive"))
      (node (ref "R84") (pin "1") (pinfunction "1_1") (pintype "passive"))
      (node (ref "R86") (pin "1") (pinfunction "1_1") (pintype "passive"))
    )
    (net (code "23") (name "/HB") (class "Default")
      (node (ref "JP11") (pin "3") (pinfunction "3_3") (pintype "passive"))
      (node (ref "R87") (pin "1") (pinfunction "1_1") (pintype "passive"))
      (node (ref "R88") (pin "1") (pinfunction "1_1") (pintype "passive"))
    )
    (net (code "24") (name "/HC") (class "Default")
      (node (ref "JP11") (pin "4") (pinfunction "4_4") (pintype "passive"))
      (node (ref "R128") (pin "1") (pinfunction "1_1") (pintype "passive"))
      (node (ref "R133") (pin "1") (pinfunction "1_1") (pintype "passive"))
    )
    (net (code "25") (name "/HX") (class "Default")
      (node (ref "JP11") (pin "5") (pinfunction "5_5") (pintype "passive"))
      (node (ref "R129") (pin "1") (pinfunction "1_1") (pintype "passive"))
      (node (ref "R173") (pin "1") (pinfunction "1_1") (pintype "passive"))
    )
    (net (code "26") (name "/ICD_2_CLK") (class "Default")
      (node (ref "JP14") (pin "5") (pinfunction "5_5") (pintype "passive"))
      (node (ref "U2") (pin "44") (pinfunction "PGEC2/ASCL2/RP38/PMCS2/RB6_44") (pintype "passive"))
    )
    (net (code "27") (name "/ICD_2_DATA") (class "Default")
      (node (ref "JP14") (pin "3") (pinfunction "3_3") (pintype "passive"))
      (node (ref "U2") (pin "43") (pinfunction "PGED2/ASDA2/RP37/RB5_43") (pintype "passive"))
    )
    (net (code "28") (name "/IN1") (class "Default")
      (node (ref "C84") (pin "2") (pinfunction "2_2") (pintype "passive"))
      (node (ref "D29") (pin "1") (pinfunction "1_1") (pintype "passive"))
      (node (ref "JP13") (pin "2") (pinfunction "2_2") (pintype "passive"))
      (node (ref "R95") (pin "2") (pinfunction "2_2") (pintype "passive"))
      (node (ref "R99") (pin "2") (pinfunction "2_2") (pintype "passive"))
    )
    (net (code "29") (name "/IN2") (class "Default")
      (node (ref "C85") (pin "2") (pinfunction "2_2") (pintype "passive"))
      (node (ref "D30") (pin "1") (pinfunction "1_1") (pintype "passive"))
      (node (ref "JP13") (pin "5") (pinfunction "5_5") (pintype "passive"))
      (node (ref "R100") (pin "2") (pinfunction "2_2") (pintype "passive"))
      (node (ref "R96") (pin "2") (pinfunction "2_2") (pintype "passive"))
    )
    (net (code "30") (name "/IN3") (class "Default")
      (node (ref "C91") (pin "2") (pinfunction "2_2") (pintype "passive"))
      (node (ref "D40") (pin "1") (pinfunction "1_1") (pintype "passive"))
      (node (ref "JP15") (pin "2") (pinfunction "2_2") (pintype "passive"))
      (node (ref "R113") (pin "2") (pinfunction "2_2") (pintype "passive"))
      (node (ref "R115") (pin "2") (pinfunction "2_2") (pintype "passive"))
    )
    (net (code "31") (name "/IN4") (class "Default")
      (node (ref "C89") (pin "2") (pinfunction "2_2") (pintype "passive"))
      (node (ref "D37") (pin "1") (pinfunction "1_1") (pintype "passive"))
      (node (ref "JP15") (pin "5") (pinfunction "5_5") (pintype "passive"))
      (node (ref "R106") (pin "2") (pinfunction "2_2") (pintype "passive"))
      (node (ref "R107") (pin "2") (pinfunction "2_2") (pintype "passive"))
    )
    (net (code "32") (name "/IS1_MA") (class "Default")
      (node (ref "R44") (pin "2") (pinfunction "2_2") (pintype "passive"))
      (node (ref "R60") (pin "2") (pinfunction "2_2") (pintype "passive"))
      (node (ref "U7") (pin "4") (pinfunction "OUT_4") (pintype "output"))
    )
    (net (code "33") (name "/IS1_MB") (class "Default")
      (node (ref "R123") (pin "2") (pinfunction "2_2") (pintype "passive"))
      (node (ref "R70") (pin "2") (pinfunction "2_2") (pintype "passive"))
      (node (ref "U8") (pin "4") (pinfunction "OUT_4") (pintype "output"))
    )
    (net (code "34") (name "/IS1_MC") (class "Default")
      (node (ref "R142") (pin "2") (pinfunction "2_2") (pintype "passive"))
      (node (ref "R80") (pin "2") (pinfunction "2_2") (pintype "passive"))
      (node (ref "U9") (pin "4") (pinfunction "OUT_4") (pintype "output"))
    )
    (net (code "35") (name "/IS_MA") (class "Default")
      (node (ref "D16") (pin "2") (pinfunction "2_2") (pintype "passive"))
      (node (ref "Q8") (pin "2") (pinfunction "2_2") (pintype "input"))
      (node (ref "Q8") (pin "3") (pinfunction "3_3") (pintype "input"))
      (node (ref "Q8") (pin "5") (pinfunction "5_5") (pintype "input"))
      (node (ref "Q8") (pin "6") (pinfunction "6_6") (pintype "input"))
      (node (ref "Q8") (pin "7") (pinfunction "7_7") (pintype "input"))
      (node (ref "R37") (pin "2") (pinfunction "2_2") (pintype "passive"))
      (node (ref "R39") (pin "2") (pinfunction "2_2") (pintype "passive"))
      (node (ref "R40") (pin "2") (pinfunction "2_2") (pintype "passive"))
      (node (ref "R42") (pin "2") (pinfunction "2_2") (pintype "passive"))
      (node (ref "R43") (pin "1") (pinfunction "1_1") (pintype "passive"))
      (node (ref "U35") (pin "9") (pinfunction "GNDB_9") (pintype "passive"))
    )
    (net (code "36") (name "/IS_MB") (class "Default")
      (node (ref "D31") (pin "2") (pinfunction "2_2") (pintype "passive"))
      (node (ref "Q10") (pin "2") (pinfunction "2_2") (pintype "input"))
      (node (ref "Q10") (pin "3") (pinfunction "3_3") (pintype "input"))
      (node (ref "Q10") (pin "5") (pinfunction "5_5") (pintype "input"))
      (node (ref "Q10") (pin "6") (pinfunction "6_6") (pintype "input"))
      (node (ref "Q10") (pin "7") (pinfunction "7_7") (pintype "input"))
      (node (ref "R122") (pin "1") (pinfunction "1_1") (pintype "passive"))
      (node (ref "R127") (pin "2") (pinfunction "2_2") (pintype "passive"))
      (node (ref "R134") (pin "2") (pinfunction "2_2") (pintype "passive"))
      (node (ref "R135") (pin "2") (pinfunction "2_2") (pintype "passive"))
      (node (ref "R137") (pin "2") (pinfunction "2_2") (pintype "passive"))
      (node (ref "U36") (pin "9") (pinfunction "GNDB_9") (pintype "passive"))
    )
    (net (code "37") (name "/IS_MC") (class "Default")
      (node (ref "D38") (pin "2") (pinfunction "2_2") (pintype "passive"))
      (node (ref "Q12") (pin "2") (pinfunction "2_2") (pintype "input"))
      (node (ref "Q12") (pin "3") (pinfunction "3_3") (pintype "input"))
      (node (ref "Q12") (pin "5") (pinfunction "5_5") (pintype "input"))
      (node (ref "Q12") (pin "6") (pinfunction "6_6") (pintype "input"))
      (node (ref "Q12") (pin "7") (pinfunction "7_7") (pintype "input"))
      (node (ref "R141") (pin "1") (pinfunction "1_1") (pintype "passive"))
      (node (ref "R146") (pin "2") (pinfunction "2_2") (pintype "passive"))
      (node (ref "R147") (pin "2") (pinfunction "2_2") (pintype "passive"))
      (node (ref "R162") (pin "2") (pinfunction "2_2") (pintype "passive"))
      (node (ref "R164") (pin "2") (pinfunction "2_2") (pintype "passive"))
      (node (ref "U37") (pin "9") (pinfunction "GNDB_9") (pintype "passive"))
    )
    (net (code "38") (name "/MA") (class "Default")
      (node (ref "C57") (pin "2") (pinfunction "2_2") (pintype "passive"))
      (node (ref "C60") (pin "1") (pinfunction "1_1") (pintype "passive"))
      (node (ref "D16") (pin "1") (pinfunction "1_1") (pintype "passive"))
      (node (ref "D20") (pin "2") (pinfunction "2_2") (pintype "passive"))
      (node (ref "D25") (pin "2") (pinfunction "2_2") (pintype "passive"))
      (node (ref "D26") (pin "2") (pinfunction "2_2") (pintype "passive"))
      (node (ref "JP6") (pin "1") (pinfunction "1_1") (pintype "passive"))
      (node (ref "JP6") (pin "2") (pinfunction "2_2") (pintype "passive"))
      (node (ref "JP6") (pin "3") (pinfunction "3_3") (pintype "passive"))
      (node (ref "JP6") (pin "4") (pinfunction "4_4") (pintype "passive"))
      (node (ref "JP6") (pin "5") (pinfunction "5_5") (pintype "passive"))
      (node (ref "Q7") (pin "2") (pinfunction "2_2") (pintype "input"))
      (node (ref "Q7") (pin "3") (pinfunction "3_3") (pintype "input"))
      (node (ref "Q7") (pin "5") (pinfunction "5_5") (pintype "input"))
      (node (ref "Q7") (pin "6") (pinfunction "6_6") (pintype "input"))
      (node (ref "Q7") (pin "7") (pinfunction "7_7") (pintype "input"))
      (node (ref "Q8") (pin "8") (pinfunction "8_8") (pintype "input"))
      (node (ref "R23") (pin "2") (pinfunction "2_2") (pintype "passive"))
      (node (ref "R41") (pin "1") (pinfunction "1_1") (pintype "passive"))
      (node (ref "U35") (pin "14") (pinfunction "GNDA_14") (pintype "passive"))
    )
    (net (code "39") (name "/MB") (class "Default")
      (node (ref "C75") (pin "1") (pinfunction "1_1") (pintype "passive"))
      (node (ref "C87") (pin "2") (pinfunction "2_2") (pintype "passive"))
      (node (ref "D31") (pin "1") (pinfunction "1_1") (pintype "passive"))
      (node (ref "D32") (pin "2") (pinfunction "2_2") (pintype "passive"))
      (node (ref "D33") (pin "2") (pinfunction "2_2") (pintype "passive"))
      (node (ref "D35") (pin "2") (pinfunction "2_2") (pintype "passive"))
      (node (ref "JP26") (pin "1") (pinfunction "1_1") (pintype "passive"))
      (node (ref "JP26") (pin "2") (pinfunction "2_2") (pintype "passive"))
      (node (ref "JP26") (pin "3") (pinfunction "3_3") (pintype "passive"))
      (node (ref "JP26") (pin "4") (pinfunction "4_4") (pintype "passive"))
      (node (ref "JP26") (pin "5") (pinfunction "5_5") (pintype "passive"))
      (node (ref "Q10") (pin "8") (pinfunction "8_8") (pintype "input"))
      (node (ref "Q9") (pin "2") (pinfunction "2_2") (pintype "input"))
      (node (ref "Q9") (pin "3") (pinfunction "3_3") (pintype "input"))
      (node (ref "Q9") (pin "5") (pinfunction "5_5") (pintype "input"))
      (node (ref "Q9") (pin "6") (pinfunction "6_6") (pintype "input"))
      (node (ref "Q9") (pin "7") (pinfunction "7_7") (pintype "input"))
      (node (ref "R126") (pin "2") (pinfunction "2_2") (pintype "passive"))
      (node (ref "R136") (pin "1") (pinfunction "1_1") (pintype "passive"))
      (node (ref "U36") (pin "14") (pinfunction "GNDA_14") (pintype "passive"))
    )
    (net (code "40") (name "/MC") (class "Default")
      (node (ref "C102") (pin "1") (pinfunction "1_1") (pintype "passive"))
      (node (ref "C108") (pin "2") (pinfunction "2_2") (pintype "passive"))
      (node (ref "D38") (pin "1") (pinfunction "1_1") (pintype "passive"))
      (node (ref "D39") (pin "2") (pinfunction "2_2") (pintype "passive"))
      (node (ref "D41") (pin "2") (pinfunction "2_2") (pintype "passive"))
      (node (ref "D43") (pin "2") (pinfunction "2_2") (pintype "passive"))
      (node (ref "JP28") (pin "1") (pinfunction "1_1") (pintype "passive"))
      (node (ref "JP28") (pin "2") (pinfunction "2_2") (pintype "passive"))
      (node (ref "JP28") (pin "3") (pinfunction "3_3") (pintype "passive"))
      (node (ref "JP28") (pin "4") (pinfunction "4_4") (pintype "passive"))
      (node (ref "JP28") (pin "5") (pinfunction "5_5") (pintype "passive"))
      (node (ref "Q11") (pin "2") (pinfunction "2_2") (pintype "input"))
      (node (ref "Q11") (pin "3") (pinfunction "3_3") (pintype "input"))
      (node (ref "Q11") (pin "5") (pinfunction "5_5") (pintype "input"))
      (node (ref "Q11") (pin "6") (pinfunction "6_6") (pintype "input"))
      (node (ref "Q11") (pin "7") (pinfunction "7_7") (pintype "input"))
      (node (ref "Q12") (pin "8") (pinfunction "8_8") (pintype "input"))
      (node (ref "R145") (pin "2") (pinfunction "2_2") (pintype "passive"))
      (node (ref "R163") (pin "1") (pinfunction "1_1") (pintype "passive"))
      (node (ref "U37") (pin "14") (pinfunction "GNDA_14") (pintype "passive"))
    )
    (net (code "41") (name "/MCLR{slash}") (class "Default")
      (node (ref "JP14") (pin "1") (pinfunction "1_1") (pintype "passive"))
      (node (ref "R4") (pin "2") (pinfunction "2_2") (pintype "passive"))
      (node (ref "U2") (pin "7") (pinfunction "~{MCLR}_7") (pintype "passive"))
    )
    (net (code "42") (name "/PA_IN1") (class "Default")
      (node (ref "R51") (pin "2") (pinfunction "2_2") (pintype "passive"))
      (node (ref "Z88") (pin "2") (pinfunction "2_2") (pintype "passive"))
    )
    (net (code "43") (name "/PA_IN2") (class "Default")
      (node (ref "R161") (pin "2") (pinfunction "2_2") (pintype "passive"))
      (node (ref "Z94") (pin "2") (pinfunction "2_2") (pintype "passive"))
    )
    (net (code "44") (name "/PA_IN3") (class "Default")
      (node (ref "R155") (pin "2") (pinfunction "2_2") (pintype "passive"))
      (node (ref "Z92") (pin "2") (pinfunction "2_2") (pintype "passive"))
    )
    (net (code "45") (name "/PA_IN4") (class "Default")
      (node (ref "R150") (pin "2") (pinfunction "2_2") (pintype "passive"))
      (node (ref "Z90") (pin "2") (pinfunction "2_2") (pintype "passive"))
    )
    (net (code "46") (name "/PWMAH") (class "Default")
      (node (ref "R159") (pin "1") (pinfunction "1_1") (pintype "passive"))
      (node (ref "U35") (pin "1") (pinfunction "INA_1") (pintype "passive"))
      (node (ref "Z49") (pin "1") (pinfunction "1_1") (pintype "passive"))
    )
    (net (code "47") (name "/PWMAL") (class "Default")
      (node (ref "R158") (pin "1") (pinfunction "1_1") (pintype "passive"))
      (node (ref "U35") (pin "2") (pinfunction "INB_2") (pintype "passive"))
      (node (ref "Z50") (pin "1") (pinfunction "1_1") (pintype "passive"))
    )
    (net (code "48") (name "/PWMBH") (class "Default")
      (node (ref "R110") (pin "1") (pinfunction "1_1") (pintype "passive"))
      (node (ref "U36") (pin "1") (pinfunction "INA_1") (pintype "passive"))
      (node (ref "Z72") (pin "2") (pinfunction "2_2") (pintype "passive"))
    )
    (net (code "49") (name "/PWMBL") (class "Default")
      (node (ref "R116") (pin "1") (pinfunction "1_1") (pintype "passive"))
      (node (ref "U36") (pin "2") (pinfunction "INB_2") (pintype "passive"))
      (node (ref "Z73") (pin "2") (pinfunction "2_2") (pintype "passive"))
    )
    (net (code "50") (name "/PWMCH") (class "Default")
      (node (ref "R91") (pin "1") (pinfunction "1_1") (pintype "passive"))
      (node (ref "U37") (pin "1") (pinfunction "INA_1") (pintype "passive"))
      (node (ref "Z74") (pin "2") (pinfunction "2_2") (pintype "passive"))
    )
    (net (code "51") (name "/PWMCL") (class "Default")
      (node (ref "R98") (pin "1") (pinfunction "1_1") (pintype "passive"))
      (node (ref "U37") (pin "2") (pinfunction "INB_2") (pintype "passive"))
      (node (ref "Z76") (pin "2") (pinfunction "2_2") (pintype "passive"))
    )
    (net (code "52") (name "/PWM_TEST1") (class "Default")
      (node (ref "Z78") (pin "2") (pinfunction "2_2") (pintype "passive"))
    )
    (net (code "53") (name "/PWM_TEST2") (class "Default")
      (node (ref "Z80") (pin "2") (pinfunction "2_2") (pintype "passive"))
    )
    (net (code "54") (name "/PWRIN1") (class "Default")
      (node (ref "F5") (pin "1") (pinfunction "1_1") (pintype "passive"))
      (node (ref "JP13") (pin "1") (pinfunction "1_1") (pintype "passive"))
      (node (ref "R94") (pin "1") (pinfunction "1_1") (pintype "passive"))
      (node (ref "R95") (pin "1") (pinfunction "1_1") (pintype "passive"))
    )
    (net (code "55") (name "/PWRIN2") (class "Default")
      (node (ref "F6") (pin "1") (pinfunction "1_1") (pintype "passive"))
      (node (ref "JP13") (pin "4") (pinfunction "4_4") (pintype "passive"))
      (node (ref "R96") (pin "1") (pinfunction "1_1") (pintype "passive"))
      (node (ref "R97") (pin "1") (pinfunction "1_1") (pintype "passive"))
    )
    (net (code "56") (name "/PWRIN3") (class "Default")
      (node (ref "F7") (pin "1") (pinfunction "1_1") (pintype "passive"))
      (node (ref "JP15") (pin "1") (pinfunction "1_1") (pintype "passive"))
      (node (ref "R109") (pin "1") (pinfunction "1_1") (pintype "passive"))
      (node (ref "R113") (pin "1") (pinfunction "1_1") (pintype "passive"))
    )
    (net (code "57") (name "/PWRIN4") (class "Default")
      (node (ref "F8") (pin "1") (pinfunction "1_1") (pintype "passive"))
      (node (ref "JP15") (pin "4") (pinfunction "4_4") (pintype "passive"))
      (node (ref "R105") (pin "1") (pinfunction "1_1") (pintype "passive"))
      (node (ref "R106") (pin "1") (pinfunction "1_1") (pintype "passive"))
    )
    (net (code "58") (name "/P_AUX_1") (class "Default")
      (node (ref "R58") (pin "1") (pinfunction "1_1") (pintype "passive"))
      (node (ref "Z67") (pin "1") (pinfunction "1_1") (pintype "passive"))
    )
    (net (code "59") (name "/P_AUX_2") (class "Default")
      (node (ref "R56") (pin "1") (pinfunction "1_1") (pintype "passive"))
      (node (ref "Z66") (pin "1") (pinfunction "1_1") (pintype "passive"))
    )
    (net (code "60") (name "/P_AUX_3") (class "Default")
      (node (ref "R57") (pin "1") (pinfunction "1_1") (pintype "passive"))
      (node (ref "Z69") (pin "1") (pinfunction "1_1") (pintype "passive"))
    )
    (net (code "61") (name "/P_EN1") (class "Default")
      (node (ref "C97") (pin "1") (pinfunction "1_1") (pintype "passive"))
      (node (ref "R120") (pin "1") (pinfunction "1_1") (pintype "passive"))
      (node (ref "R121") (pin "2") (pinfunction "2_2") (pintype "passive"))
      (node (ref "Z87") (pin "2") (pinfunction "2_2") (pintype "passive"))
    )
    (net (code "62") (name "/P_EN2") (class "Default")
      (node (ref "C98") (pin "1") (pinfunction "1_1") (pintype "passive"))
      (node (ref "R131") (pin "1") (pinfunction "1_1") (pintype "passive"))
      (node (ref "R132") (pin "2") (pinfunction "2_2") (pintype "passive"))
      (node (ref "Z86") (pin "2") (pinfunction "2_2") (pintype "passive"))
    )
    (net (code "63") (name "/P_EN3") (class "Default")
      (node (ref "C99") (pin "1") (pinfunction "1_1") (pintype "passive"))
      (node (ref "R166") (pin "1") (pinfunction "1_1") (pintype "passive"))
      (node (ref "R167") (pin "2") (pinfunction "2_2") (pintype "passive"))
      (node (ref "Z91") (pin "2") (pinfunction "2_2") (pintype "passive"))
    )
    (net (code "64") (name "/P_ENX") (class "Default")
      (node (ref "C111") (pin "1") (pinfunction "1_1") (pintype "passive"))
      (node (ref "R174") (pin "1") (pinfunction "1_1") (pintype "passive"))
      (node (ref "R175") (pin "2") (pinfunction "2_2") (pintype "passive"))
      (node (ref "Z93") (pin "2") (pinfunction "2_2") (pintype "passive"))
    )
    (net (code "65") (name "/P_HA") (class "Default")
      (node (ref "C71") (pin "1") (pinfunction "1_1") (pintype "passive"))
      (node (ref "R84") (pin "2") (pinfunction "2_2") (pintype "passive"))
      (node (ref "R85") (pin "1") (pinfunction "1_1") (pintype "passive"))
      (node (ref "Z61") (pin "1") (pinfunction "1_1") (pintype "passive"))
    )
    (net (code "66") (name "/P_HB") (class "Default")
      (node (ref "C73") (pin "1") (pinfunction "1_1") (pintype "passive"))
      (node (ref "R88") (pin "2") (pinfunction "2_2") (pintype "passive"))
      (node (ref "R89") (pin "1") (pinfunction "1_1") (pintype "passive"))
      (node (ref "Z63") (pin "1") (pinfunction "1_1") (pintype "passive"))
    )
    (net (code "67") (name "/P_HC") (class "Default")
      (node (ref "C118") (pin "1") (pinfunction "1_1") (pintype "passive"))
      (node (ref "R130") (pin "1") (pinfunction "1_1") (pintype "passive"))
      (node (ref "R133") (pin "2") (pinfunction "2_2") (pintype "passive"))
      (node (ref "Z62") (pin "1") (pinfunction "1_1") (pintype "passive"))
    )
    (net (code "68") (name "/P_HX") (class "Default")
      (node (ref "C110") (pin "1") (pinfunction "1_1") (pintype "passive"))
      (node (ref "R172") (pin "1") (pinfunction "1_1") (pintype "passive"))
      (node (ref "R173") (pin "2") (pinfunction "2_2") (pintype "passive"))
    )
    (net (code "69") (name "/P_IS_MA") (class "Default")
      (node (ref "R160") (pin "2") (pinfunction "2_2") (pintype "passive"))
      (node (ref "R47") (pin "2") (pinfunction "2_2") (pintype "passive"))
      (node (ref "Z84") (pin "2") (pinfunction "2_2") (pintype "passive"))
    )
    (net (code "70") (name "/P_IS_MB") (class "Default")
      (node (ref "R64") (pin "2") (pinfunction "2_2") (pintype "passive"))
      (node (ref "R92") (pin "2") (pinfunction "2_2") (pintype "passive"))
      (node (ref "Z55") (pin "1") (pinfunction "1_1") (pintype "passive"))
    )
    (net (code "71") (name "/P_IS_MC") (class "Default")
      (node (ref "R74") (pin "2") (pinfunction "2_2") (pintype "passive"))
      (node (ref "R90") (pin "2") (pinfunction "2_2") (pintype "passive"))
      (node (ref "Z85") (pin "2") (pinfunction "2_2") (pintype "passive"))
    )
    (net (code "72") (name "/P_IS_MD") (class "Default")
      (node (ref "R93") (pin "2") (pinfunction "2_2") (pintype "passive"))
      (node (ref "Z83") (pin "2") (pinfunction "2_2") (pintype "passive"))
    )
    (net (code "73") (name "/P_LED1") (class "Default")
      (node (ref "R36") (pin "2") (pinfunction "2_2") (pintype "passive"))
      (node (ref "Z68") (pin "1") (pinfunction "1_1") (pintype "passive"))
    )
    (net (code "74") (name "/P_LED2") (class "Default")
      (node (ref "R38") (pin "2") (pinfunction "2_2") (pintype "passive"))
      (node (ref "Z70") (pin "1") (pinfunction "1_1") (pintype "passive"))
    )
    (net (code "75") (name "/P_MS_RXD") (class "Default")
      (node (ref "R54") (pin "1") (pinfunction "1_1") (pintype "passive"))
      (node (ref "Z52") (pin "1") (pinfunction "1_1") (pintype "passive"))
    )
    (net (code "76") (name "/P_MS_TXD") (class "Default")
      (node (ref "U20") (pin "6") (pinfunction "TXD_6") (pintype "passive"))
      (node (ref "Z51") (pin "1") (pinfunction "1_1") (pintype "passive"))
    )
    (net (code "77") (name "/P_MS_TXD_EN") (class "Default")
      (node (ref "U40") (pin "2") (pinfunction "I1_2") (pintype "input"))
      (node (ref "Z65") (pin "1") (pinfunction "1_1") (pintype "passive"))
    )
    (net (code "78") (name "/P_TAKT_M") (class "Default")
      (node (ref "R55") (pin "1") (pinfunction "1_1") (pintype "passive"))
      (node (ref "Z54") (pin "1") (pinfunction "1_1") (pintype "passive"))
    )
    (net (code "79") (name "/SCL") (class "Default")
      (node (ref "R33") (pin "2") (pinfunction "2_2") (pintype "passive"))
      (node (ref "U2") (pin "5") (pinfunction "AN18/ASCL1/RPI119/PMA4/RG7_5") (pintype "passive"))
      (node (ref "U6") (pin "6") (pinfunction "SCL_6") (pintype "passive"))
    )
    (net (code "80") (name "/SDA") (class "Default")
      (node (ref "R34") (pin "2") (pinfunction "2_2") (pintype "passive"))
      (node (ref "U2") (pin "6") (pinfunction "AN17/ASDA1/RP120/PMA3/RG8_6") (pintype "passive"))
      (node (ref "U6") (pin "5") (pinfunction "SDA_5") (pintype "passive"))
    )
    (net (code "81") (name "/SW") (class "Default")
      (node (ref "D12") (pin "1") (pinfunction "1_1") (pintype "passive"))
      (node (ref "L6") (pin "1") (pinfunction "1_1") (pintype "passive"))
      (node (ref "R112") (pin "2") (pinfunction "2_2") (pintype "passive"))
      (node (ref "R118") (pin "2") (pinfunction "2_2") (pintype "passive"))
      (node (ref "R139") (pin "2") (pinfunction "2_2") (pintype "passive"))
      (node (ref "U13") (pin "1") (pinfunction "Vout_1") (pintype "passive"))
    )
    (net (code "82") (name "/TAKT_M1") (class "Default")
      (node (ref "C124") (pin "2") (pinfunction "2_2") (pintype "passive"))
      (node (ref "R154") (pin "2") (pinfunction "2_2") (pintype "passive"))
      (node (ref "R180") (pin "1") (pinfunction "1_1") (pintype "passive"))
    )
    (net (code "83") (name "GND") (class "Default")
      (node (ref "C10") (pin "1") (pinfunction "1_1") (pintype "passive"))
      (node (ref "C100") (pin "2") (pinfunction "2_2") (pintype "passive"))
      (node (ref "C101") (pin "2") (pinfunction "2_2") (pintype "passive"))
      (node (ref "C103") (pin "2") (pinfunction "2_2") (pintype "passive"))
      (node (ref "C104") (pin "1") (pinfunction "1_1") (pintype "passive"))
      (node (ref "C105") (pin "1") (pinfunction "1_1") (pintype "passive"))
      (node (ref "C106") (pin "1") (pinfunction "1_1") (pintype "passive"))
      (node (ref "C107") (pin "1") (pinfunction "1_1") (pintype "passive"))
      (node (ref "C110") (pin "2") (pinfunction "2_2") (pintype "passive"))
      (node (ref "C111") (pin "2") (pinfunction "2_2") (pintype "passive"))
      (node (ref "C115") (pin "1") (pinfunction "1_1") (pintype "passive"))
      (node (ref "C116") (pin "1") (pinfunction "1_1") (pintype "passive"))
      (node (ref "C117") (pin "1") (pinfunction "1_1") (pintype "passive"))
      (node (ref "C118") (pin "2") (pinfunction "2_2") (pintype "passive"))
      (node (ref "C131") (pin "1") (pinfunction "1_1") (pintype "passive"))
      (node (ref "C132") (pin "1") (pinfunction "1_1") (pintype "passive"))
      (node (ref "C133") (pin "1") (pinfunction "1_1") (pintype "passive"))
      (node (ref "C134") (pin "1") (pinfunction "1_1") (pintype "passive"))
      (node (ref "C135") (pin "1") (pinfunction "1_1") (pintype "passive"))
      (node (ref "C136") (pin "1") (pinfunction "1_1") (pintype "passive"))
      (node (ref "C137") (pin "1") (pinfunction "1_1") (pintype "passive"))
      (node (ref "C138") (pin "1") (pinfunction "1_1") (pintype "passive"))
      (node (ref "C139") (pin "1") (pinfunction "1_1") (pintype "passive"))
      (node (ref "C16") (pin "2") (pinfunction "2_2") (pintype "passive"))
      (node (ref "C2") (pin "1") (pinfunction "1_1") (pintype "passive"))
      (node (ref "C20") (pin "2") (pinfunction "2_2") (pintype "passive"))
      (node (ref "C21") (pin "2") (pinfunction "2_2") (pintype "passive"))
      (node (ref "C22") (pin "2") (pinfunction "2_2") (pintype "passive"))
      (node (ref "C23") (pin "1") (pinfunction "1_1") (pintype "passive"))
      (node (ref "C28") (pin "2") (pinfunction "2_2") (pintype "passive"))
      (node (ref "C29") (pin "2") (pinfunction "2_2") (pintype "passive"))
      (node (ref "C30") (pin "2") (pinfunction "2_2") (pintype "passive"))
      (node (ref "C31") (pin "2") (pinfunction "2_2") (pintype "passive"))
      (node (ref "C35") (pin "1") (pinfunction "1_1") (pintype "passive"))
      (node (ref "C36") (pin "2") (pinfunction "2_2") (pintype "passive"))
      (node (ref "C43") (pin "2") (pinfunction "2_2") (pintype "passive"))
      (node (ref "C44") (pin "2") (pinfunction "2_2") (pintype "passive"))
      (node (ref "C48") (pin "2") (pinfunction "2_2") (pintype "passive"))
      (node (ref "C49") (pin "2") (pinfunction "2_2") (pintype "passive"))
      (node (ref "C50") (pin "2") (pinfunction "2_2") (pintype "passive"))
      (node (ref "C51") (pin "2") (pinfunction "2_2") (pintype "passive"))
      (node (ref "C52") (pin "2") (pinfunction "2_2") (pintype "passive"))
      (node (ref "C53") (pin "1") (pinfunction "1_1") (pintype "passive"))
      (node (ref "C54") (pin "1") (pinfunction "1_1") (pintype "passive"))
      (node (ref "C55") (pin "1") (pinfunction "1_1") (pintype "passive"))
      (node (ref "C56") (pin "1") (pinfunction "1_1") (pintype "passive"))
      (node (ref "C61") (pin "1") (pinfunction "1_1") (pintype "passive"))
      (node (ref "C62") (pin "1") (pinfunction "1_1") (pintype "passive"))
      (node (ref "C65") (pin "2") (pinfunction "2_2") (pintype "passive"))
      (node (ref "C66") (pin "2") (pinfunction "2_2") (pintype "passive"))
      (node (ref "C69") (pin "2") (pinfunction "2_2") (pintype "passive"))
      (node (ref "C7") (pin "2") (pinfunction "2_2") (pintype "passive"))
      (node (ref "C71") (pin "2") (pinfunction "2_2") (pintype "passive"))
      (node (ref "C73") (pin "2") (pinfunction "2_2") (pintype "passive"))
      (node (ref "C74") (pin "2") (pinfunction "2_2") (pintype "passive"))
      (node (ref "C77") (pin "1") (pinfunction "1_1") (pintype "passive"))
      (node (ref "C78") (pin "2") (pinfunction "2_2") (pintype "passive"))
      (node (ref "C79") (pin "2") (pinfunction "2_2") (pintype "passive"))
      (node (ref "C8") (pin "1") (pinfunction "1_1") (pintype "passive"))
      (node (ref "C81") (pin "1") (pinfunction "1_1") (pintype "passive"))
      (node (ref "C82") (pin "1") (pinfunction "1_1") (pintype "passive"))
      (node (ref "C83") (pin "1") (pinfunction "1_1") (pintype "passive"))
      (node (ref "C84") (pin "1") (pinfunction "1_1") (pintype "passive"))
      (node (ref "C85") (pin "1") (pinfunction "1_1") (pintype "passive"))
      (node (ref "C89") (pin "1") (pinfunction "1_1") (pintype "passive"))
      (node (ref "C9") (pin "2") (pinfunction "2_2") (pintype "passive"))
      (node (ref "C90") (pin "2") (pinfunction "2_2") (pintype "passive"))
      (node (ref "C91") (pin "1") (pinfunction "1_1") (pintype "passive"))
      (node (ref "C92") (pin "2") (pinfunction "2_2") (pintype "passive"))
      (node (ref "C97") (pin "2") (pinfunction "2_2") (pintype "passive"))
      (node (ref "C98") (pin "2") (pinfunction "2_2") (pintype "passive"))
      (node (ref "C99") (pin "2") (pinfunction "2_2") (pintype "passive"))
      (node (ref "D12") (pin "2") (pinfunction "2_2") (pintype "passive"))
      (node (ref "D7") (pin "1") (pinfunction "1_1") (pintype "passive"))
      (node (ref "D8") (pin "1") (pinfunction "1_1") (pintype "passive"))
      (node (ref "JP11") (pin "6") (pinfunction "6_6") (pintype "passive"))
      (node (ref "JP12") (pin "6") (pinfunction "6_6") (pintype "passive"))
      (node (ref "JP13") (pin "3") (pinfunction "3_3") (pintype "passive"))
      (node (ref "JP13") (pin "6") (pinfunction "6_6") (pintype "passive"))
      (node (ref "JP14") (pin "6") (pinfunction "6_6") (pintype "passive"))
      (node (ref "JP15") (pin "3") (pinfunction "3_3") (pintype "passive"))
      (node (ref "JP15") (pin "6") (pinfunction "6_6") (pintype "passive"))
      (node (ref "JP37") (pin "1") (pinfunction "1_1") (pintype "passive"))
      (node (ref "JP37") (pin "2") (pinfunction "2_2") (pintype "passive"))
      (node (ref "JP37") (pin "3") (pinfunction "3_3") (pintype "passive"))
      (node (ref "JP37") (pin "4") (pinfunction "4_4") (pintype "passive"))
      (node (ref "JP37") (pin "5") (pinfunction "5_5") (pintype "passive"))
      (node (ref "JP7") (pin "1") (pinfunction "1_1") (pintype "passive"))
      (node (ref "JP7") (pin "2") (pinfunction "2_2") (pintype "passive"))
      (node (ref "JP8") (pin "1") (pinfunction "1_1") (pintype "passive"))
      (node (ref "JP8") (pin "2") (pinfunction "2_2") (pintype "passive"))
      (node (ref "JP9") (pin "1") (pinfunction "1_1") (pintype "passive"))
      (node (ref "JP9") (pin "2") (pinfunction "2_2") (pintype "passive"))
      (node (ref "OPTO1") (pin "3") (pinfunction "3_3") (pintype "passive"))
      (node (ref "R101") (pin "1") (pinfunction "1_1") (pintype "passive"))
      (node (ref "R103") (pin "1") (pinfunction "1_1") (pintype "passive"))
      (node (ref "R104") (pin "1") (pinfunction "1_1") (pintype "passive"))
      (node (ref "R108") (pin "1") (pinfunction "1_1") (pintype "passive"))
      (node (ref "R110") (pin "2") (pinfunction "2_2") (pintype "passive"))
      (node (ref "R114") (pin "1") (pinfunction "1_1") (pintype "passive"))
      (node (ref "R116") (pin "2") (pinfunction "2_2") (pintype "passive"))
      (node (ref "R120") (pin "2") (pinfunction "2_2") (pintype "passive"))
      (node (ref "R124") (pin "1") (pinfunction "1_1") (pintype "passive"))
      (node (ref "R127") (pin "1") (pinfunction "1_1") (pintype "passive"))
      (node (ref "R130") (pin "2") (pinfunction "2_2") (pintype "passive"))
      (node (ref "R131") (pin "2") (pinfunction "2_2") (pintype "passive"))
      (node (ref "R134") (pin "1") (pinfunction "1_1") (pintype "passive"))
      (node (ref "R135") (pin "1") (pinfunction "1_1") (pintype "passive"))
      (node (ref "R143") (pin "1") (pinfunction "1_1") (pintype "passive"))
      (node (ref "R146") (pin "1") (pinfunction "1_1") (pintype "passive"))
      (node (ref "R147") (pin "1") (pinfunction "1_1") (pintype "passive"))
      (node (ref "R151") (pin "1") (pinfunction "1_1") (pintype "passive"))
      (node (ref "R156") (pin "1") (pinfunction "1_1") (pintype "passive"))
      (node (ref "R158") (pin "2") (pinfunction "2_2") (pintype "passive"))
      (node (ref "R159") (pin "2") (pinfunction "2_2") (pintype "passive"))
      (node (ref "R162") (pin "1") (pinfunction "1_1") (pintype "passive"))
      (node (ref "R166") (pin "2") (pinfunction "2_2") (pintype "passive"))
      (node (ref "R172") (pin "2") (pinfunction "2_2") (pintype "passive"))
      (node (ref "R174") (pin "2") (pinfunction "2_2") (pintype "passive"))
      (node (ref "R176") (pin "1") (pinfunction "1_1") (pintype "passive"))
      (node (ref "R37") (pin "1") (pinfunction "1_1") (pintype "passive"))
      (node (ref "R39") (pin "1") (pinfunction "1_1") (pintype "passive"))
      (node (ref "R40") (pin "1") (pinfunction "1_1") (pintype "passive"))
      (node (ref "R45") (pin "1") (pinfunction "1_1") (pintype "passive"))
      (node (ref "R49") (pin "1") (pinfunction "1_1") (pintype "passive"))
      (node (ref "R52") (pin "1") (pinfunction "1_1") (pintype "passive"))
      (node (ref "R62") (pin "2") (pinfunction "2_2") (pintype "passive"))
      (node (ref "R63") (pin "1") (pinfunction "1_1") (pintype "passive"))
      (node (ref "R66") (pin "1") (pinfunction "1_1") (pintype "passive"))
      (node (ref "R72") (pin "1") (pinfunction "1_1") (pintype "passive"))
      (node (ref "R73") (pin "1") (pinfunction "1_1") (pintype "passive"))
      (node (ref "R76") (pin "1") (pinfunction "1_1") (pintype "passive"))
      (node (ref "R83") (pin "1") (pinfunction "1_1") (pintype "passive"))
      (node (ref "R85") (pin "2") (pinfunction "2_2") (pintype "passive"))
      (node (ref "R89") (pin "2") (pinfunction "2_2") (pintype "passive"))
      (node (ref "R91") (pin "2") (pinfunction "2_2") (pintype "passive"))
      (node (ref "R98") (pin "2") (pinfunction "2_2") (pintype "passive"))
      (node (ref "U13") (pin "7") (pinfunction "GND_7") (pintype "passive"))
      (node (ref "U13") (pin "9") (pinfunction "GND_9") (pintype "passive"))
      (node (ref "U14") (pin "3") (pinfunction "GND_3") (pintype "passive"))
      (node (ref "U15") (pin "3") (pinfunction "GND_3") (pintype "passive"))
      (node (ref "U16") (pin "11") (pinfunction "V-_11") (pintype "input"))
      (node (ref "U2") (pin "20") (pinfunction "AVSS_20") (pintype "passive"))
      (node (ref "U2") (pin "25") (pinfunction "VSS_25") (pintype "passive"))
      (node (ref "U2") (pin "41") (pinfunction "VSS_41") (pintype "passive"))
      (node (ref "U2") (pin "9") (pinfunction "VSS_9") (pintype "passive"))
      (node (ref "U20") (pin "2") (pinfunction "GND1_2") (pintype "power_in"))
      (node (ref "U20") (pin "8") (pinfunction "GND1_8") (pintype "power_in"))
      (node (ref "U21") (pin "5") (pinfunction "GND2_5") (pintype "passive"))
      (node (ref "U23") (pin "5") (pinfunction "GND2_5") (pintype "passive"))
      (node (ref "U35") (pin "4") (pinfunction "GND_4") (pintype "passive"))
      (node (ref "U36") (pin "4") (pinfunction "GND_4") (pintype "passive"))
      (node (ref "U37") (pin "4") (pinfunction "GND_4") (pintype "passive"))
      (node (ref "U39") (pin "11") (pinfunction "V-_11") (pintype "input"))
      (node (ref "U40") (pin "3") (pinfunction "GND_3") (pintype "passive"))
      (node (ref "U6") (pin "1") (pinfunction "A0_1") (pintype "passive"))
      (node (ref "U6") (pin "2") (pinfunction "A1_2") (pintype "passive"))
      (node (ref "U6") (pin "3") (pinfunction "A2_3") (pintype "passive"))
      (node (ref "U6") (pin "4") (pinfunction "GND_4") (pintype "power_in"))
      (node (ref "U6") (pin "7") (pinfunction "WP_7") (pintype "passive"))
      (node (ref "U7") (pin "2") (pinfunction "V-_2") (pintype "passive"))
      (node (ref "U8") (pin "2") (pinfunction "V-_2") (pintype "passive"))
      (node (ref "U9") (pin "2") (pinfunction "V-_2") (pintype "passive"))
    )
    (net (code "84") (name "GND_FIELD SIGNAL") (class "Default")
      (node (ref "C122") (pin "1") (pinfunction "1_1") (pintype "passive"))
      (node (ref "C123") (pin "1") (pinfunction "1_1") (pintype "passive"))
      (node (ref "C124") (pin "1") (pinfunction "1_1") (pintype "passive"))
      (node (ref "C125") (pin "1") (pinfunction "1_1") (pintype "passive"))
      (node (ref "C126") (pin "1") (pinfunction "1_1") (pintype "passive"))
      (node (ref "C64") (pin "2") (pinfunction "2_2") (pintype "passive"))
      (node (ref "C68") (pin "2") (pinfunction "2_2") (pintype "passive"))
      (node (ref "C70") (pin "1") (pinfunction "1_1") (pintype "passive"))
      (node (ref "C94") (pin "2") (pinfunction "2_2") (pintype "passive"))
      (node (ref "C95") (pin "1") (pinfunction "1_1") (pintype "passive"))
      (node (ref "C96") (pin "1") (pinfunction "1_1") (pintype "passive"))
      (node (ref "JP30") (pin "1") (pinfunction "1_1") (pintype "passive"))
      (node (ref "OPTO1") (pin "2") (pinfunction "LED_CATHODE_2") (pintype "passive"))
      (node (ref "R73") (pin "2") (pinfunction "2_2") (pintype "passive"))
      (node (ref "R81") (pin "2") (pinfunction "2_2") (pintype "passive"))
      (node (ref "U20") (pin "15") (pinfunction "GND2_15") (pintype "power_in"))
      (node (ref "U20") (pin "9") (pinfunction "GND2_9") (pintype "power_in"))
      (node (ref "U21") (pin "4") (pinfunction "GND1_4") (pintype "passive"))
      (node (ref "U23") (pin "4") (pinfunction "GND1_4") (pintype "passive"))
    )
    (net (code "85") (name "Net-(C54-Pad2)") (class "Default")
      (node (ref "C54") (pin "2") (pinfunction "2_2") (pintype "passive"))
      (node (ref "R61") (pin "2") (pinfunction "2_2") (pintype "passive"))
    )
    (net (code "86") (name "Net-(C55-Pad2)") (class "Default")
      (node (ref "C55") (pin "2") (pinfunction "2_2") (pintype "passive"))
      (node (ref "R23") (pin "1") (pinfunction "1_1") (pintype "passive"))
    )
    (net (code "87") (name "Net-(C59-Pad1)") (class "Default")
      (node (ref "C59") (pin "1") (pinfunction "1_1") (pintype "passive"))
      (node (ref "D21") (pin "2") (pinfunction "2_2") (pintype "passive"))
      (node (ref "D25") (pin "1") (pinfunction "1_1") (pintype "passive"))
    )
    (net (code "88") (name "Net-(C59-Pad2)") (class "Default")
      (node (ref "C59") (pin "2") (pinfunction "2_2") (pintype "passive"))
      (node (ref "R112") (pin "1") (pinfunction "1_1") (pintype "passive"))
    )
    (net (code "89") (name "Net-(C81-Pad2)") (class "Default")
      (node (ref "C81") (pin "2") (pinfunction "2_2") (pintype "passive"))
      (node (ref "R126") (pin "1") (pinfunction "1_1") (pintype "passive"))
    )
    (net (code "90") (name "Net-(C88-Pad1)") (class "Default")
      (node (ref "C88") (pin "1") (pinfunction "1_1") (pintype "passive"))
      (node (ref "D33") (pin "1") (pinfunction "1_1") (pintype "passive"))
      (node (ref "D34") (pin "2") (pinfunction "2_2") (pintype "passive"))
    )
    (net (code "91") (name "Net-(C88-Pad2)") (class "Default")
      (node (ref "C88") (pin "2") (pinfunction "2_2") (pintype "passive"))
      (node (ref "R118") (pin "1") (pinfunction "1_1") (pintype "passive"))
    )
    (net (code "92") (name "Net-(C105-Pad2)") (class "Default")
      (node (ref "C105") (pin "2") (pinfunction "2_2") (pintype "passive"))
      (node (ref "R145") (pin "1") (pinfunction "1_1") (pintype "passive"))
    )
    (net (code "93") (name "Net-(C109-Pad1)") (class "Default")
      (node (ref "C109") (pin "1") (pinfunction "1_1") (pintype "passive"))
      (node (ref "D41") (pin "1") (pinfunction "1_1") (pintype "passive"))
      (node (ref "D42") (pin "2") (pinfunction "2_2") (pintype "passive"))
    )
    (net (code "94") (name "Net-(C109-Pad2)") (class "Default")
      (node (ref "C109") (pin "2") (pinfunction "2_2") (pintype "passive"))
      (node (ref "R139") (pin "1") (pinfunction "1_1") (pintype "passive"))
    )
    (net (code "95") (name "Net-(D7-Pad2)") (class "Default")
      (node (ref "D7") (pin "2") (pinfunction "2_2") (pintype "passive"))
      (node (ref "R36") (pin "1") (pinfunction "1_1") (pintype "passive"))
    )
    (net (code "96") (name "Net-(D8-Pad2)") (class "Default")
      (node (ref "D8") (pin "2") (pinfunction "2_2") (pintype "passive"))
      (node (ref "R38") (pin "1") (pinfunction "1_1") (pintype "passive"))
    )
    (net (code "97") (name "Net-(D27-Pad2)") (class "Default")
      (node (ref "D27") (pin "2") (pinfunction "2_2") (pintype "passive"))
      (node (ref "R117") (pin "2") (pinfunction "2_2") (pintype "passive"))
    )
    (net (code "98") (name "Net-(D28-Pad2)") (class "Default")
      (node (ref "D28") (pin "2") (pinfunction "2_2") (pintype "passive"))
      (node (ref "R119") (pin "2") (pinfunction "2_2") (pintype "passive"))
    )
    (net (code "99") (name "Net-(D29-Pad2)") (class "Default")
      (node (ref "D29") (pin "2") (pinfunction "2_2") (pintype "passive"))
      (node (ref "R94") (pin "2") (pinfunction "2_2") (pintype "passive"))
    )
    (net (code "100") (name "Net-(D30-Pad2)") (class "Default")
      (node (ref "D30") (pin "2") (pinfunction "2_2") (pintype "passive"))
      (node (ref "R97") (pin "2") (pinfunction "2_2") (pintype "passive"))
    )
    (net (code "101") (name "Net-(D36-Pad2)") (class "Default")
      (node (ref "D36") (pin "2") (pinfunction "2_2") (pintype "passive"))
      (node (ref "R140") (pin "2") (pinfunction "2_2") (pintype "passive"))
    )
    (net (code "102") (name "Net-(D37-Pad2)") (class "Default")
      (node (ref "D37") (pin "2") (pinfunction "2_2") (pintype "passive"))
      (node (ref "R105") (pin "2") (pinfunction "2_2") (pintype "passive"))
    )
    (net (code "103") (name "Net-(D40-Pad2)") (class "Default")
      (node (ref "D40") (pin "2") (pinfunction "2_2") (pintype "passive"))
      (node (ref "R109") (pin "2") (pinfunction "2_2") (pintype "passive"))
    )
    (net (code "104") (name "Net-(F2-Pad1)") (class "Default")
      (node (ref "F2") (pin "1") (pinfunction "1_1") (pintype "passive"))
      (node (ref "JP11") (pin "1") (pinfunction "1_1") (pintype "passive"))
    )
    (net (code "105") (name "Net-(F2-Pad2)") (class "Default")
      (node (ref "F2") (pin "2") (pinfunction "2_2") (pintype "passive"))
      (node (ref "JH48") (pin "1") (pinfunction "1_1") (pintype "passive"))
      (node (ref "R128") (pin "2") (pinfunction "2_2") (pintype "passive"))
      (node (ref "R129") (pin "2") (pinfunction "2_2") (pintype "passive"))
      (node (ref "R86") (pin "2") (pinfunction "2_2") (pintype "passive"))
      (node (ref "R87") (pin "2") (pinfunction "2_2") (pintype "passive"))
    )
    (net (code "106") (name "Net-(F3-Pad1)") (class "Default")
      (node (ref "F3") (pin "1") (pinfunction "1_1") (pintype "passive"))
      (node (ref "JP12") (pin "1") (pinfunction "1_1") (pintype "passive"))
    )
    (net (code "107") (name "Net-(F3-Pad2)") (class "Default")
      (node (ref "F3") (pin "2") (pinfunction "2_2") (pintype "passive"))
      (node (ref "JH50") (pin "1") (pinfunction "1_1") (pintype "passive"))
      (node (ref "R168") (pin "2") (pinfunction "2_2") (pintype "passive"))
      (node (ref "R169") (pin "2") (pinfunction "2_2") (pintype "passive"))
      (node (ref "R170") (pin "2") (pinfunction "2_2") (pintype "passive"))
      (node (ref "R171") (pin "2") (pinfunction "2_2") (pintype "passive"))
    )
    (net (code "108") (name "Net-(F5-Pad2)") (class "Default")
      (node (ref "F5") (pin "2") (pinfunction "2_2") (pintype "passive"))
      (node (ref "JH52") (pin "1") (pinfunction "1_1") (pintype "passive"))
    )
    (net (code "109") (name "Net-(F6-Pad2)") (class "Default")
      (node (ref "F6") (pin "2") (pinfunction "2_2") (pintype "passive"))
      (node (ref "JH54") (pin "1") (pinfunction "1_1") (pintype "passive"))
    )
    (net (code "110") (name "Net-(F7-Pad2)") (class "Default")
      (node (ref "F7") (pin "2") (pinfunction "2_2") (pintype "passive"))
      (node (ref "JH56") (pin "1") (pinfunction "1_1") (pintype "passive"))
    )
    (net (code "111") (name "Net-(F8-Pad2)") (class "Default")
      (node (ref "F8") (pin "2") (pinfunction "2_2") (pintype "passive"))
      (node (ref "JH58") (pin "1") (pinfunction "1_1") (pintype "passive"))
    )
    (net (code "112") (name "Net-(JP30-Pad2)") (class "Default")
      (node (ref "JP30") (pin "2") (pinfunction "2_2") (pintype "passive"))
      (node (ref "L7") (pin "1") (pinfunction "1_1") (pintype "passive"))
    )
    (net (code "113") (name "Net-(JP30-Pad5)") (class "Default")
      (node (ref "JP30") (pin "5") (pinfunction "5_5") (pintype "passive"))
      (node (ref "R178") (pin "2") (pinfunction "2_2") (pintype "passive"))
    )
    (net (code "114") (name "Net-(JP30-Pad6)") (class "Default")
      (node (ref "JP30") (pin "6") (pinfunction "6_6") (pintype "passive"))
      (node (ref "R180") (pin "2") (pinfunction "2_2") (pintype "passive"))
    )
    (net (code "115") (name "Net-(JP30-Pad7)") (class "Default")
      (node (ref "JP30") (pin "7") (pinfunction "7_7") (pintype "passive"))
      (node (ref "R179") (pin "2") (pinfunction "2_2") (pintype "passive"))
    )
    (net (code "116") (name "Net-(JP30-Pad8)") (class "Default")
      (node (ref "JP30") (pin "8") (pinfunction "8_8") (pintype "passive"))
      (node (ref "R181") (pin "2") (pinfunction "2_2") (pintype "passive"))
    )
    (net (code "117") (name "Net-(JP30-Pad9)") (class "Default")
      (node (ref "JP30") (pin "9") (pinfunction "9_9") (pintype "passive"))
      (node (ref "R182") (pin "2") (pinfunction "2_2") (pintype "passive"))
    )
    (net (code "118") (name "Net-(JP32-Pad1)") (class "Default")
      (node (ref "JP32") (pin "1") (pinfunction "1_1") (pintype "passive"))
      (node (ref "JP34") (pin "1") (pinfunction "1_1") (pintype "passive"))
      (node (ref "JP35") (pin "1") (pinfunction "1_1") (pintype "passive"))
    )
    (net (code "119") (name "Net-(OPTO1-Pad1)") (class "Default")
      (node (ref "OPTO1") (pin "1") (pinfunction "1_1") (pintype "passive"))
      (node (ref "R69") (pin "2") (pinfunction "2_2") (pintype "passive"))
    )
    (net (code "120") (name "Net-(U2-AN9{slash}RPI27{slash}RA11)") (class "Default")
      (node (ref "U2") (pin "12") (pinfunction "AN9/RPI27/RA11_12") (pintype "passive"))
      (node (ref "Z54") (pin "2") (pinfunction "2_2") (pintype "passive"))
    )
    (net (code "121") (name "Net-(U2-AN10{slash}RPI28{slash}RA12)") (class "Default")
      (node (ref "U2") (pin "11") (pinfunction "AN10/RPI28/RA12_11") (pintype "passive"))
      (node (ref "Z53") (pin "2") (pinfunction "2_2") (pintype "passive"))
    )
    (net (code "122") (name "Net-(U2-AN11{slash}C1IN2-{slash}U1CTS{slash}FLT4{slash}PMA12{slash}RC11)") (class "Default")
      (node (ref "U2") (pin "24") (pinfunction "AN11/C1IN2-/U1CTS/FLT4/PMA12/RC11_24") (pintype "passive"))
      (node (ref "Z64") (pin "2") (pinfunction "2_2") (pintype "passive"))
    )
    (net (code "123") (name "Net-(U2-AN12{slash}C2IN2-{slash}C5IN2-{slash}U2RTS{slash}BCLK2{slash}FLT5{slash}PMA11{slash}RE12)") (class "Default")
      (node (ref "U2") (pin "27") (pinfunction "AN12/C2IN2-/C5IN2-/U2RTS/BCLK2/FLT5/PMA11/RE12_27") (pintype "passive"))
      (node (ref "Z65") (pin "2") (pinfunction "2_2") (pintype "passive"))
    )
    (net (code "124") (name "Net-(U2-AN13{slash}C3IN2-{slash}U2CTS{slash}FLT6{slash}PMA10{slash}RE13)") (class "Default")
      (node (ref "U2") (pin "28") (pinfunction "AN13/C3IN2-/U2CTS/FLT6/PMA10/RE13_28") (pintype "passive"))
      (node (ref "Z67") (pin "2") (pinfunction "2_2") (pintype "passive"))
    )
    (net (code "125") (name "Net-(U2-AN14{slash}RPI94{slash}FLT7{slash}PMA1{slash}RE14)") (class "Default")
      (node (ref "U2") (pin "29") (pinfunction "AN14/RPI94/FLT7/PMA1/RE14_29") (pintype "passive"))
      (node (ref "Z66") (pin "2") (pinfunction "2_2") (pintype "passive"))
    )
    (net (code "126") (name "Net-(U2-AN15{slash}RPI95{slash}FLT8{slash}PMA0{slash}RE15)") (class "Default")
      (node (ref "U2") (pin "30") (pinfunction "AN15/RPI95/FLT8/PMA0/RE15_30") (pintype "passive"))
      (node (ref "Z69") (pin "2") (pinfunction "2_2") (pintype "passive"))
    )
    (net (code "127") (name "Net-(U2-AN16{slash}RPI121{slash}PMA2{slash}RG9)") (class "Default")
      (node (ref "U2") (pin "8") (pinfunction "AN16/RPI121/PMA2/RG9_8") (pintype "passive"))
      (node (ref "Z52") (pin "2") (pinfunction "2_2") (pintype "passive"))
    )
    (net (code "128") (name "Net-(U2-AN19{slash}RP118{slash}PMA5{slash}RG6)") (class "Default")
      (node (ref "U2") (pin "4") (pinfunction "AN19/RP118/PMA5/RG6_4") (pintype "passive"))
      (node (ref "Z51") (pin "2") (pinfunction "2_2") (pintype "passive"))
    )
    (net (code "129") (name "Net-(U2-AN28{slash}SDI1{slash}RPI25{slash}RA9)") (class "Default")
      (node (ref "U2") (pin "34") (pinfunction "AN28/SDI1/RPI25/RA9_34") (pintype "passive"))
      (node (ref "Z92") (pin "1") (pinfunction "1_1") (pintype "passive"))
    )
    (net (code "130") (name "Net-(U2-AN29{slash}SCK1{slash}RPI51{slash}RC3)") (class "Default")
      (node (ref "U2") (pin "35") (pinfunction "AN29/SCK1/RPI51/RC3_35") (pintype "passive"))
      (node (ref "Z90") (pin "1") (pinfunction "1_1") (pintype "passive"))
    )
    (net (code "131") (name "Net-(U2-AN30{slash}SDA1{slash}RPI52{slash}RC4)") (class "Default")
      (node (ref "U2") (pin "36") (pinfunction "AN30/SDA1/RPI52/RC4_36") (pintype "passive"))
      (node (ref "Z88") (pin "1") (pinfunction "1_1") (pintype "passive"))
    )
    (net (code "132") (name "Net-(U2-AN31{slash}SCL1{slash}RPI53{slash}RC5)") (class "Default")
      (node (ref "U2") (pin "37") (pinfunction "AN31/SCL1/RPI53/RC5_37") (pintype "passive"))
      (node (ref "Z85") (pin "1") (pinfunction "1_1") (pintype "passive"))
    )
    (net (code "133") (name "Net-(U2-AN48{slash}CVREF2O{slash}RPI58{slash}PMCS1{slash}RC10)") (class "Default")
      (node (ref "U2") (pin "45") (pinfunction "AN48/CVREF2O/RPI58/PMCS1/RC10_45") (pintype "passive"))
      (node (ref "Z89") (pin "1") (pinfunction "1_1") (pintype "passive"))
    )
    (net (code "134") (name "Net-(U2-AN49{slash}OSC1{slash}CLKI{slash}RPI60{slash}RC12)") (class "Default")
      (node (ref "C16") (pin "1") (pinfunction "1_1") (pintype "passive"))
      (node (ref "U2") (pin "39") (pinfunction "AN49/OSC1/CLKI/RPI60/RC12_39") (pintype "passive"))
      (node (ref "Y1") (pin "2") (pinfunction "2_2") (pintype "passive"))
    )
    (net (code "135") (name "Net-(U2-FLT32{slash}SCL2{slash}RP36{slash}PMA8{slash}RB4)") (class "Default")
      (node (ref "U2") (pin "32") (pinfunction "FLT32/SCL2/RP36/PMA8/RB4_32") (pintype "passive"))
      (node (ref "Z68") (pin "2") (pinfunction "2_2") (pintype "passive"))
    )
    (net (code "136") (name "Net-(U2-OA2IN+{slash}AN1{slash}C2IN3-{slash}C2IN1+{slash}RPI17{slash}RA1)") (class "Default")
      (node (ref "U2") (pin "14") (pinfunction "OA2IN+/AN1/C2IN3-/C2IN1+/RPI17/RA1_14") (pintype "passive"))
      (node (ref "Z56") (pin "2") (pinfunction "2_2") (pintype "passive"))
    )
    (net (code "137") (name "Net-(U2-OA2OUT{slash}AN0{slash}C2IN4-{slash}C4IN3-{slash}RPI16{slash}RA0)") (class "Default")
      (node (ref "U2") (pin "13") (pinfunction "OA2OUT/AN0/C2IN4-/C4IN3-/RPI16/RA0_13") (pintype "passive"))
      (node (ref "Z55") (pin "2") (pinfunction "2_2") (pintype "passive"))
    )
    (net (code "138") (name "Net-(U2-OA3IN+{slash}AN8{slash}C3IN3-{slash}C3IN1+{slash}RPI50{slash}U1RTS{slash}BCLK1{slash}FLT3{slash}RC2)") (class "Default")
      (node (ref "U2") (pin "23") (pinfunction "OA3IN+/AN8/C3IN3-/C3IN1+/RPI50/U1RTS/BCLK1/FLT3/RC2_23") (pintype "passive"))
      (node (ref "Z62") (pin "2") (pinfunction "2_2") (pintype "passive"))
    )
    (net (code "139") (name "Net-(U2-OA3IN-{slash}AN7{slash}C3IN1-{slash}C4IN1-{slash}RP49{slash}RC1)") (class "Default")
      (node (ref "U2") (pin "22") (pinfunction "OA3IN-/AN7/C3IN1-/C4IN1-/RP49/RC1_22") (pintype "passive"))
      (node (ref "Z63") (pin "2") (pinfunction "2_2") (pintype "passive"))
    )
    (net (code "140") (name "Net-(U2-OA3OUT{slash}AN6{slash}C3IN4-{slash}C4IN4-{slash}C4IN1+{slash}RP48{slash}OCFB{slash}RC0)") (class "Default")
      (node (ref "U2") (pin "21") (pinfunction "OA3OUT/AN6/C3IN4-/C4IN4-/C4IN1+/RP48/OCFB/RC0_21") (pintype "passive"))
      (node (ref "Z61") (pin "2") (pinfunction "2_2") (pintype "passive"))
    )
    (net (code "141") (name "Net-(U2-OA5IN+{slash}AN24{slash}C5IN3-{slash}C5IN1+{slash}SDO1{slash}RP20{slash}T1CK{slash}RA4)") (class "Default")
      (node (ref "U2") (pin "33") (pinfunction "OA5IN+/AN24/C5IN3-/C5IN1+/SDO1/RP20/T1CK/RA4_33") (pintype "passive"))
      (node (ref "Z94") (pin "1") (pinfunction "1_1") (pintype "passive"))
    )
    (net (code "142") (name "Net-(U2-OA5OUT{slash}AN25{slash}C5IN4-{slash}RP39{slash}INT0{slash}RB7)") (class "Default")
      (node (ref "U2") (pin "46") (pinfunction "OA5OUT/AN25/C5IN4-/RP39/INT0/RB7_46") (pintype "passive"))
      (node (ref "Z83") (pin "1") (pinfunction "1_1") (pintype "passive"))
    )
    (net (code "143") (name "Net-(U2-OSC2{slash}CLKO{slash}RPI63{slash}RC15)") (class "Default")
      (node (ref "C20") (pin "1") (pinfunction "1_1") (pintype "passive"))
      (node (ref "U2") (pin "40") (pinfunction "OSC2/CLKO/RPI63/RC15_40") (pintype "passive"))
      (node (ref "Y1") (pin "1") (pinfunction "1_1") (pintype "passive"))
    )
    (net (code "144") (name "Net-(U2-PGEC1{slash}OA1IN+{slash}AN4{slash}C1IN3-{slash}C1IN1+{slash}C2IN3-{slash}RPI34{slash}RB2)") (class "Default")
      (node (ref "U2") (pin "17") (pinfunction "PGEC1/OA1IN+/AN4/C1IN3-/C1IN1+/C2IN3-/RPI34/RB2_17") (pintype "passive"))
      (node (ref "Z59") (pin "2") (pinfunction "2_2") (pintype "passive"))
    )
    (net (code "145") (name "Net-(U2-PGEC3{slash}VREF+{slash}CVREF+{slash}OA1OUT{slash}AN3{slash}C1IN4-{slash}C4IN2-{slash}RPI33{slash}CTED1{slash}RB1)") (class "Default")
      (node (ref "U2") (pin "16") (pinfunction "PGEC3/VREF+/CVREF+/OA1OUT/AN3/C1IN4-/C4IN2-/RPI33/CTED1/RB1_16") (pintype "passive"))
      (node (ref "Z58") (pin "2") (pinfunction "2_2") (pintype "passive"))
    )
    (net (code "146") (name "Net-(U2-PGED1{slash}OA1IN-{slash}AN5{slash}C1IN1-{slash}(CTMUC){slash}RP35{slash}RTCC{slash}RB3)") (class "Default")
      (node (ref "U2") (pin "18") (pinfunction "PGED1/OA1IN-/AN5/C1IN1-/(CTMUC)/RP35/RTCC/RB3_18") (pintype "passive"))
      (node (ref "Z60") (pin "2") (pinfunction "2_2") (pintype "passive"))
    )
    (net (code "147") (name "Net-(U2-PGED3{slash}VREF-{slash}OA2IN-{slash}AN2{slash}C2IN1-{slash}SS1{slash}RPI32{slash}CTED2{slash}RB0)") (class "Default")
      (node (ref "U2") (pin "15") (pinfunction "PGED3/VREF-/OA2IN-/AN2/C2IN1-/SS1/RPI32/CTED2/RB0_15") (pintype "passive"))
      (node (ref "Z57") (pin "2") (pinfunction "2_2") (pintype "passive"))
    )
    (net (code "148") (name "Net-(U2-RP42{slash}PWM3H{slash}PMD0{slash}RB10)") (class "Default")
      (node (ref "U2") (pin "60") (pinfunction "RP42/PWM3H/PMD0/RB10_60") (pintype "passive"))
      (node (ref "Z74") (pin "1") (pinfunction "1_1") (pintype "passive"))
    )
    (net (code "149") (name "Net-(U2-RP43{slash}PWM3L{slash}PMD1{slash}RB11)") (class "Default")
      (node (ref "U2") (pin "61") (pinfunction "RP43/PWM3L/PMD1/RB11_61") (pintype "passive"))
      (node (ref "Z76") (pin "1") (pinfunction "1_1") (pintype "passive"))
    )
    (net (code "150") (name "Net-(U2-RP54{slash}PWM6H{slash}RC6)") (class "Default")
      (node (ref "U2") (pin "50") (pinfunction "RP54/PWM6H/RC6_50") (pintype "passive"))
      (node (ref "Z91") (pin "1") (pinfunction "1_1") (pintype "passive"))
    )
    (net (code "151") (name "Net-(U2-RP55{slash}PWM6L{slash}PMBE{slash}RC7)") (class "Default")
      (node (ref "U2") (pin "51") (pinfunction "RP55/PWM6L/PMBE/RC7_51") (pintype "passive"))
      (node (ref "Z79") (pin "1") (pinfunction "1_1") (pintype "passive"))
    )
    (net (code "152") (name "Net-(U2-RP56{slash}PWM5H{slash}PMWR{slash}RC8)") (class "Default")
      (node (ref "U2") (pin "52") (pinfunction "RP56/PWM5H/PMWR/RC8_52") (pintype "passive"))
      (node (ref "Z82") (pin "1") (pinfunction "1_1") (pintype "passive"))
    )
    (net (code "153") (name "Net-(U2-RP57{slash}PWM5L{slash}RC9)") (class "Default")
      (node (ref "U2") (pin "55") (pinfunction "RP57/PWM5L/RC9_55") (pintype "passive"))
      (node (ref "Z80") (pin "1") (pinfunction "1_1") (pintype "passive"))
    )
    (net (code "154") (name "Net-(U2-RP69{slash}PMRD{slash}RD5)") (class "Default")
      (node (ref "U2") (pin "53") (pinfunction "RP69/PMRD/RD5_53") (pintype "passive"))
      (node (ref "Z81") (pin "1") (pinfunction "1_1") (pintype "passive"))
    )
    (net (code "155") (name "Net-(U2-RP70{slash}RD6)") (class "Default")
      (node (ref "U2") (pin "54") (pinfunction "RP70/RD6_54") (pintype "passive"))
      (node (ref "Z78") (pin "1") (pinfunction "1_1") (pintype "passive"))
    )
    (net (code "156") (name "Net-(U2-RP97{slash}RF1)") (class "Default")
      (node (ref "U2") (pin "59") (pinfunction "RP97/RF1_59") (pintype "passive"))
      (node (ref "Z75") (pin "1") (pinfunction "1_1") (pintype "passive"))
    )
    (net (code "157") (name "Net-(U2-RPI44{slash}PWM2H{slash}PMD2{slash}RB12)") (class "Default")
      (node (ref "U2") (pin "62") (pinfunction "RPI44/PWM2H/PMD2/RB12_62") (pintype "passive"))
      (node (ref "Z72") (pin "1") (pinfunction "1_1") (pintype "passive"))
    )
    (net (code "158") (name "Net-(U2-RPI45{slash}PWM2L{slash}CTPLS{slash}PMD3{slash}RB13)") (class "Default")
      (node (ref "U2") (pin "63") (pinfunction "RPI45/PWM2L/CTPLS/PMD3/RB13_63") (pintype "passive"))
      (node (ref "Z73") (pin "1") (pinfunction "1_1") (pintype "passive"))
    )
    (net (code "159") (name "Net-(U2-RPI46{slash}PWM1H{slash}T3CK{slash}T7CK{slash}PMD6{slash}RB14)") (class "Default")
      (node (ref "U2") (pin "2") (pinfunction "RPI46/PWM1H/T3CK/T7CK/PMD6/RB14_2") (pintype "passive"))
      (node (ref "Z49") (pin "2") (pinfunction "2_2") (pintype "passive"))
    )
    (net (code "160") (name "Net-(U2-RPI47{slash}PWM1L{slash}T5CK{slash}T6CK{slash}PMD7{slash}RB15)") (class "Default")
      (node (ref "U2") (pin "3") (pinfunction "RPI47/PWM1L/T5CK/T6CK/PMD7/RB15_3") (pintype "passive"))
      (node (ref "Z50") (pin "2") (pinfunction "2_2") (pintype "passive"))
    )
    (net (code "161") (name "Net-(U2-RPI72{slash}RD8)") (class "Default")
      (node (ref "U2") (pin "42") (pinfunction "RPI72/RD8_42") (pintype "passive"))
      (node (ref "Z86") (pin "1") (pinfunction "1_1") (pintype "passive"))
    )
    (net (code "162") (name "Net-(U2-RPI96{slash}RF0)") (class "Default")
      (node (ref "U2") (pin "58") (pinfunction "RPI96/RF0_58") (pintype "passive"))
      (node (ref "Z77") (pin "1") (pinfunction "1_1") (pintype "passive"))
    )
    (net (code "163") (name "Net-(U2-SDA2{slash}RPI24{slash}PMA9{slash}RA8)") (class "Default")
      (node (ref "U2") (pin "31") (pinfunction "SDA2/RPI24/PMA9/RA8_31") (pintype "passive"))
      (node (ref "Z70") (pin "2") (pinfunction "2_2") (pintype "passive"))
    )
    (net (code "164") (name "Net-(U2-SOSCI{slash}RPI61{slash}RC13)") (class "Default")
      (node (ref "U2") (pin "47") (pinfunction "SOSCI/RPI61/RC13_47") (pintype "passive"))
      (node (ref "Z87") (pin "1") (pinfunction "1_1") (pintype "passive"))
    )
    (net (code "165") (name "Net-(U2-TCK{slash}AN26{slash}CVREF1O{slash}SOSCO{slash}RP40{slash}T4CK{slash}RB8)") (class "Default")
      (node (ref "U2") (pin "48") (pinfunction "TCK/AN26/CVREF1O/SOSCO/RP40/T4CK/RB8_48") (pintype "passive"))
      (node (ref "Z84") (pin "1") (pinfunction "1_1") (pintype "passive"))
    )
    (net (code "166") (name "Net-(U2-TDI{slash}PWM4L{slash}PMD5{slash}RA7)") (class "Default")
      (node (ref "U2") (pin "1") (pinfunction "TDI/PWM4L/PMD5/RA7_1") (pintype "passive"))
      (node (ref "Z48") (pin "2") (pinfunction "2_2") (pintype "passive"))
    )
    (net (code "167") (name "Net-(U2-TDO{slash}PWM4H{slash}PMD4{slash}RA10)") (class "Default")
      (node (ref "U2") (pin "64") (pinfunction "TDO/PWM4H/PMD4/RA10_64") (pintype "passive"))
      (node (ref "Z71") (pin "1") (pinfunction "1_1") (pintype "passive"))
    )
    (net (code "168") (name "Net-(U2-TMS{slash}OA5IN-{slash}AN27{slash}C5IN1-{slash}RP41{slash}RB9)") (class "Default")
      (node (ref "U2") (pin "49") (pinfunction "TMS/OA5IN-/AN27/C5IN1-/RP41/RB9_49") (pintype "passive"))
      (node (ref "Z93") (pin "1") (pinfunction "1_1") (pintype "passive"))
    )
    (net (code "169") (name "Net-(U2-Vcap)") (class "Default")
      (node (ref "C23") (pin "2") (pinfunction "2_2") (pintype "passive"))
      (node (ref "U2") (pin "56") (pinfunction "Vcap_56") (pintype "passive"))
    )
    (net (code "170") (name "Net-(U6-VCC)") (class "Default")
      (node (ref "C21") (pin "1") (pinfunction "1_1") (pintype "passive"))
      (node (ref "L2") (pin "2") (pinfunction "2_2") (pintype "passive"))
      (node (ref "U6") (pin "8") (pinfunction "VCC_8") (pintype "passive"))
    )
    (net (code "171") (name "Net-(U7-IN+)") (class "Default")
      (node (ref "C61") (pin "2") (pinfunction "2_2") (pintype "passive"))
      (node (ref "R43") (pin "2") (pinfunction "2_2") (pintype "passive"))
      (node (ref "U7") (pin "1") (pinfunction "IN+_1") (pintype "input"))
    )
    (net (code "172") (name "Net-(U7-IN-)") (class "Default")
      (node (ref "R44") (pin "1") (pinfunction "1_1") (pintype "passive"))
      (node (ref "R45") (pin "2") (pinfunction "2_2") (pintype "passive"))
      (node (ref "U7") (pin "3") (pinfunction "IN-_3") (pintype "input"))
    )
    (net (code "173") (name "Net-(U7-V+)") (class "Default")
      (node (ref "C100") (pin "1") (pinfunction "1_1") (pintype "passive"))
      (node (ref "R46") (pin "1") (pinfunction "1_1") (pintype "passive"))
      (node (ref "U7") (pin "5") (pinfunction "V+_5") (pintype "passive"))
    )
    (net (code "174") (name "Net-(U8-IN+)") (class "Default")
      (node (ref "C77") (pin "2") (pinfunction "2_2") (pintype "passive"))
      (node (ref "R122") (pin "2") (pinfunction "2_2") (pintype "passive"))
      (node (ref "U8") (pin "1") (pinfunction "IN+_1") (pintype "input"))
    )
    (net (code "175") (name "Net-(U8-IN-)") (class "Default")
      (node (ref "R123") (pin "1") (pinfunction "1_1") (pintype "passive"))
      (node (ref "R124") (pin "2") (pinfunction "2_2") (pintype "passive"))
      (node (ref "U8") (pin "3") (pinfunction "IN-_3") (pintype "input"))
    )
    (net (code "176") (name "Net-(U8-V+)") (class "Default")
      (node (ref "C101") (pin "1") (pinfunction "1_1") (pintype "passive"))
      (node (ref "R125") (pin "1") (pinfunction "1_1") (pintype "passive"))
      (node (ref "U8") (pin "5") (pinfunction "V+_5") (pintype "passive"))
    )
    (net (code "177") (name "Net-(U9-IN+)") (class "Default")
      (node (ref "C104") (pin "2") (pinfunction "2_2") (pintype "passive"))
      (node (ref "R141") (pin "2") (pinfunction "2_2") (pintype "passive"))
      (node (ref "U9") (pin "1") (pinfunction "IN+_1") (pintype "input"))
    )
    (net (code "178") (name "Net-(U9-IN-)") (class "Default")
      (node (ref "R142") (pin "1") (pinfunction "1_1") (pintype "passive"))
      (node (ref "R143") (pin "2") (pinfunction "2_2") (pintype "passive"))
      (node (ref "U9") (pin "3") (pinfunction "IN-_3") (pintype "input"))
    )
    (net (code "179") (name "Net-(U9-V+)") (class "Default")
      (node (ref "C103") (pin "1") (pinfunction "1_1") (pintype "passive"))
      (node (ref "R144") (pin "1") (pinfunction "1_1") (pintype "passive"))
      (node (ref "U9") (pin "5") (pinfunction "V+_5") (pintype "passive"))
    )
    (net (code "180") (name "Net-(U13-COMP)") (class "Default")
      (node (ref "C53") (pin "2") (pinfunction "2_2") (pintype "passive"))
      (node (ref "R61") (pin "1") (pinfunction "1_1") (pintype "passive"))
      (node (ref "U13") (pin "4") (pinfunction "COMP_4") (pintype "passive"))
    )
    (net (code "181") (name "Net-(U13-FB)") (class "Default")
      (node (ref "R59") (pin "2") (pinfunction "2_2") (pintype "passive"))
      (node (ref "R62") (pin "1") (pinfunction "1_1") (pintype "passive"))
      (node (ref "U13") (pin "5") (pinfunction "FB_5") (pintype "passive"))
    )
    (net (code "182") (name "Net-(U13-INH)") (class "Default")
      (node (ref "OPTO1") (pin "4") (pinfunction "4_4") (pintype "passive"))
      (node (ref "R68") (pin "2") (pinfunction "2_2") (pintype "passive"))
      (node (ref "U13") (pin "3") (pinfunction "INH_3") (pintype "passive"))
    )
    (net (code "183") (name "Net-(U13-Vin)") (class "Default")
      (node (ref "C28") (pin "1") (pinfunction "1_1") (pintype "passive"))
      (node (ref "C48") (pin "1") (pinfunction "1_1") (pintype "passive"))
      (node (ref "C49") (pin "1") (pinfunction "1_1") (pintype "passive"))
      (node (ref "C51") (pin "1") (pinfunction "1_1") (pintype "passive"))
      (node (ref "R50") (pin "1") (pinfunction "1_1") (pintype "passive"))
      (node (ref "R68") (pin "1") (pinfunction "1_1") (pintype "passive"))
      (node (ref "U13") (pin "8") (pinfunction "Vin_8") (pintype "passive"))
    )
    (net (code "184") (name "Net-(U16A-IN+)") (class "Default")
      (node (ref "C52") (pin "1") (pinfunction "1_1") (pintype "passive"))
      (node (ref "R60") (pin "1") (pinfunction "1_1") (pintype "passive"))
      (node (ref "R63") (pin "2") (pinfunction "2_2") (pintype "passive"))
      (node (ref "U16") (pin "3") (pinfunction "IN+_3") (pintype "input"))
    )
    (net (code "185") (name "Net-(U16A-IN-)") (class "Default")
      (node (ref "C27") (pin "1") (pinfunction "1_1") (pintype "passive"))
      (node (ref "R48") (pin "1") (pinfunction "1_1") (pintype "passive"))
      (node (ref "R49") (pin "2") (pinfunction "2_2") (pintype "passive"))
      (node (ref "U16") (pin "2") (pinfunction "IN-_2") (pintype "input"))
    )
    (net (code "186") (name "Net-(U16A-OUT)") (class "Default")
      (node (ref "C27") (pin "2") (pinfunction "2_2") (pintype "passive"))
      (node (ref "R47") (pin "1") (pinfunction "1_1") (pintype "passive"))
      (node (ref "R48") (pin "2") (pinfunction "2_2") (pintype "passive"))
      (node (ref "U16") (pin "1") (pinfunction "OUT_1") (pintype "output"))
    )
    (net (code "187") (name "Net-(U16B-IN+)") (class "Default")
      (node (ref "C65") (pin "1") (pinfunction "1_1") (pintype "passive"))
      (node (ref "R70") (pin "1") (pinfunction "1_1") (pintype "passive"))
      (node (ref "R72") (pin "2") (pinfunction "2_2") (pintype "passive"))
      (node (ref "U16") (pin "5") (pinfunction "IN+_5") (pintype "input"))
    )
    (net (code "188") (name "Net-(U16B-IN-)") (class "Default")
      (node (ref "C58") (pin "1") (pinfunction "1_1") (pintype "passive"))
      (node (ref "R65") (pin "1") (pinfunction "1_1") (pintype "passive"))
      (node (ref "R66") (pin "2") (pinfunction "2_2") (pintype "passive"))
      (node (ref "U16") (pin "6") (pinfunction "IN-_6") (pintype "input"))
    )
    (net (code "189") (name "Net-(U16B-OUT)") (class "Default")
      (node (ref "C58") (pin "2") (pinfunction "2_2") (pintype "passive"))
      (node (ref "R64") (pin "1") (pinfunction "1_1") (pintype "passive"))
      (node (ref "R65") (pin "2") (pinfunction "2_2") (pintype "passive"))
      (node (ref "U16") (pin "7") (pinfunction "OUT_7") (pintype "output"))
    )
    (net (code "190") (name "Net-(U16C-IN+)") (class "Default")
      (node (ref "C69") (pin "1") (pinfunction "1_1") (pintype "passive"))
      (node (ref "R80") (pin "1") (pinfunction "1_1") (pintype "passive"))
      (node (ref "R83") (pin "2") (pinfunction "2_2") (pintype "passive"))
      (node (ref "U16") (pin "10") (pinfunction "IN+_10") (pintype "input"))
    )
    (net (code "191") (name "Net-(U16C-IN-)") (class "Default")
      (node (ref "C67") (pin "1") (pinfunction "1_1") (pintype "passive"))
      (node (ref "R75") (pin "1") (pinfunction "1_1") (pintype "passive"))
      (node (ref "R76") (pin "2") (pinfunction "2_2") (pintype "passive"))
      (node (ref "U16") (pin "9") (pinfunction "IN-_9") (pintype "input"))
    )
    (net (code "192") (name "Net-(U16C-OUT)") (class "Default")
      (node (ref "C67") (pin "2") (pinfunction "2_2") (pintype "passive"))
      (node (ref "R74") (pin "1") (pinfunction "1_1") (pintype "passive"))
      (node (ref "R75") (pin "2") (pinfunction "2_2") (pintype "passive"))
      (node (ref "U16") (pin "8") (pinfunction "OUT_8") (pintype "output"))
    )
    (net (code "193") (name "Net-(U16D-IN+)") (class "Default")
      (node (ref "C74") (pin "1") (pinfunction "1_1") (pintype "passive"))
      (node (ref "R160") (pin "1") (pinfunction "1_1") (pintype "passive"))
      (node (ref "R90") (pin "1") (pinfunction "1_1") (pintype "passive"))
      (node (ref "R92") (pin "1") (pinfunction "1_1") (pintype "passive"))
      (node (ref "U16") (pin "12") (pinfunction "IN+_12") (pintype "input"))
    )
    (net (code "194") (name "Net-(U16D-IN-)") (class "Default")
      (node (ref "C72") (pin "1") (pinfunction "1_1") (pintype "passive"))
      (node (ref "R101") (pin "2") (pinfunction "2_2") (pintype "passive"))
      (node (ref "R102") (pin "1") (pinfunction "1_1") (pintype "passive"))
      (node (ref "U16") (pin "13") (pinfunction "IN-_13") (pintype "input"))
    )
    (net (code "195") (name "Net-(U16D-OUT)") (class "Default")
      (node (ref "C72") (pin "2") (pinfunction "2_2") (pintype "passive"))
      (node (ref "R102") (pin "2") (pinfunction "2_2") (pintype "passive"))
      (node (ref "R93") (pin "1") (pinfunction "1_1") (pintype "passive"))
      (node (ref "U16") (pin "14") (pinfunction "OUT_14") (pintype "output"))
    )
    (net (code "196") (name "Net-(U20-A)") (class "Default")
      (node (ref "R78") (pin "1") (pinfunction "1_1") (pintype "passive"))
      (node (ref "U20") (pin "12") (pinfunction "A_12") (pintype "passive"))
    )
    (net (code "197") (name "Net-(U20-B)") (class "Default")
      (node (ref "R82") (pin "1") (pinfunction "1_1") (pintype "passive"))
      (node (ref "U20") (pin "13") (pinfunction "B_13") (pintype "passive"))
    )
    (net (code "198") (name "Net-(U20-PV)") (class "Default")
      (node (ref "C66") (pin "1") (pinfunction "1_1") (pintype "passive"))
      (node (ref "R71") (pin "1") (pinfunction "1_1") (pintype "passive"))
      (node (ref "U20") (pin "7") (pinfunction "PV_7") (pintype "passive"))
    )
    (net (code "199") (name "Net-(U20-RTS)") (class "Default")
      (node (ref "U20") (pin "4") (pinfunction "~{RE}_4") (pintype "passive"))
      (node (ref "U20") (pin "5") (pinfunction "RTS_5") (pintype "passive"))
      (node (ref "U40") (pin "4") (pinfunction "O_4") (pintype "output"))
    )
    (net (code "200") (name "Net-(U20-RXD)") (class "Default")
      (node (ref "R54") (pin "2") (pinfunction "2_2") (pintype "passive"))
      (node (ref "U20") (pin "3") (pinfunction "RXD_3") (pintype "passive"))
    )
    (net (code "201") (name "Net-(U20-VDD1)") (class "Default")
      (node (ref "C62") (pin "2") (pinfunction "2_2") (pintype "passive"))
      (node (ref "L8") (pin "1") (pinfunction "1_1") (pintype "passive"))
      (node (ref "U20") (pin "1") (pinfunction "VDD1_1") (pintype "passive"))
    )
    (net (code "202") (name "Net-(U21-A)") (class "Default")
      (node (ref "R149") (pin "1") (pinfunction "1_1") (pintype "passive"))
      (node (ref "U21") (pin "2") (pinfunction "A_2") (pintype "passive"))
    )
    (net (code "203") (name "Net-(U21-Ain)") (class "Default")
      (node (ref "R58") (pin "2") (pinfunction "2_2") (pintype "passive"))
      (node (ref "U21") (pin "7") (pinfunction "Ain_7") (pintype "passive"))
    )
    (net (code "204") (name "Net-(U21-B)") (class "Default")
      (node (ref "R55") (pin "2") (pinfunction "2_2") (pintype "passive"))
      (node (ref "U21") (pin "6") (pinfunction "B_6") (pintype "passive"))
    )
    (net (code "205") (name "Net-(U21-Bin)") (class "Default")
      (node (ref "R154") (pin "1") (pinfunction "1_1") (pintype "passive"))
      (node (ref "U21") (pin "3") (pinfunction "Bin_3") (pintype "passive"))
    )
    (net (code "206") (name "Net-(U21-VDD2)") (class "Default")
      (node (ref "C116") (pin "2") (pinfunction "2_2") (pintype "passive"))
      (node (ref "L13") (pin "1") (pinfunction "1_1") (pintype "passive"))
      (node (ref "U21") (pin "8") (pinfunction "VDD2_8") (pintype "passive"))
    )
    (net (code "207") (name "Net-(U23-A)") (class "Default")
      (node (ref "R148") (pin "1") (pinfunction "1_1") (pintype "passive"))
      (node (ref "U23") (pin "2") (pinfunction "A_2") (pintype "passive"))
    )
    (net (code "208") (name "Net-(U23-Ain)") (class "Default")
      (node (ref "R57") (pin "2") (pinfunction "2_2") (pintype "passive"))
      (node (ref "U23") (pin "7") (pinfunction "Ain_7") (pintype "passive"))
    )
    (net (code "209") (name "Net-(U23-B)") (class "Default")
      (node (ref "R56") (pin "2") (pinfunction "2_2") (pintype "passive"))
      (node (ref "U23") (pin "6") (pinfunction "B_6") (pintype "passive"))
    )
    (net (code "210") (name "Net-(U23-Bin)") (class "Default")
      (node (ref "R153") (pin "1") (pinfunction "1_1") (pintype "passive"))
      (node (ref "U23") (pin "3") (pinfunction "Bin_3") (pintype "passive"))
    )
    (net (code "211") (name "Net-(U23-VDD2)") (class "Default")
      (node (ref "C115") (pin "2") (pinfunction "2_2") (pintype "passive"))
      (node (ref "L12") (pin "1") (pinfunction "1_1") (pintype "passive"))
      (node (ref "U23") (pin "8") (pinfunction "VDD2_8") (pintype "passive"))
    )
    (net (code "212") (name "Net-(U39A-IN-)") (class "Default")
      (node (ref "C32") (pin "1") (pinfunction "1_1") (pintype "passive"))
      (node (ref "R52") (pin "2") (pinfunction "2_2") (pintype "passive"))
      (node (ref "R53") (pin "1") (pinfunction "1_1") (pintype "passive"))
      (node (ref "U39") (pin "2") (pinfunction "IN-_2") (pintype "input"))
    )
    (net (code "213") (name "Net-(U39A-OUT)") (class "Default")
      (node (ref "C32") (pin "2") (pinfunction "2_2") (pintype "passive"))
      (node (ref "R51") (pin "1") (pinfunction "1_1") (pintype "passive"))
      (node (ref "R53") (pin "2") (pinfunction "2_2") (pintype "passive"))
      (node (ref "U39") (pin "1") (pinfunction "OUT_1") (pintype "output"))
    )
    (net (code "214") (name "Net-(U39B-IN-)") (class "Default")
      (node (ref "C120") (pin "1") (pinfunction "1_1") (pintype "passive"))
      (node (ref "R176") (pin "2") (pinfunction "2_2") (pintype "passive"))
      (node (ref "R177") (pin "1") (pinfunction "1_1") (pintype "passive"))
      (node (ref "U39") (pin "6") (pinfunction "IN-_6") (pintype "input"))
    )
    (net (code "215") (name "Net-(U39B-OUT)") (class "Default")
      (node (ref "C120") (pin "2") (pinfunction "2_2") (pintype "passive"))
      (node (ref "R161") (pin "1") (pinfunction "1_1") (pintype "passive"))
      (node (ref "R177") (pin "2") (pinfunction "2_2") (pintype "passive"))
      (node (ref "U39") (pin "7") (pinfunction "OUT_7") (pintype "output"))
    )
    (net (code "216") (name "Net-(U39C-IN-)") (class "Default")
      (node (ref "C114") (pin "1") (pinfunction "1_1") (pintype "passive"))
      (node (ref "R156") (pin "2") (pinfunction "2_2") (pintype "passive"))
      (node (ref "R157") (pin "1") (pinfunction "1_1") (pintype "passive"))
      (node (ref "U39") (pin "9") (pinfunction "IN-_9") (pintype "input"))
    )
    (net (code "217") (name "Net-(U39C-OUT)") (class "Default")
      (node (ref "C114") (pin "2") (pinfunction "2_2") (pintype "passive"))
      (node (ref "R155") (pin "1") (pinfunction "1_1") (pintype "passive"))
      (node (ref "R157") (pin "2") (pinfunction "2_2") (pintype "passive"))
      (node (ref "U39") (pin "8") (pinfunction "OUT_8") (pintype "output"))
    )
    (net (code "218") (name "Net-(U39D-IN-)") (class "Default")
      (node (ref "C112") (pin "1") (pinfunction "1_1") (pintype "passive"))
      (node (ref "R151") (pin "2") (pinfunction "2_2") (pintype "passive"))
      (node (ref "R152") (pin "1") (pinfunction "1_1") (pintype "passive"))
      (node (ref "U39") (pin "13") (pinfunction "IN-_13") (pintype "input"))
    )
    (net (code "219") (name "Net-(U39D-OUT)") (class "Default")
      (node (ref "C112") (pin "2") (pinfunction "2_2") (pintype "passive"))
      (node (ref "R150") (pin "1") (pinfunction "1_1") (pintype "passive"))
      (node (ref "R152") (pin "2") (pinfunction "2_2") (pintype "passive"))
      (node (ref "U39") (pin "14") (pinfunction "OUT_14") (pintype "output"))
    )
    (net (code "220") (name "Net-(U40-I0)") (class "Default")
      (node (ref "C117") (pin "2") (pinfunction "2_2") (pintype "passive"))
      (node (ref "L14") (pin "2") (pinfunction "2_2") (pintype "passive"))
      (node (ref "U40") (pin "1") (pinfunction "I0_1") (pintype "input"))
      (node (ref "U40") (pin "5") (pinfunction "VCC_5") (pintype "passive"))
    )
    (net (code "221") (name "VCCP_24") (class "Default")
      (node (ref "C137") (pin "2") (pinfunction "2_2") (pintype "passive"))
      (node (ref "C138") (pin "2") (pinfunction "2_2") (pintype "passive"))
      (node (ref "C139") (pin "2") (pinfunction "2_2") (pintype "passive"))
      (node (ref "F9") (pin "1") (pinfunction "1_1") (pintype "passive"))
      (node (ref "F9") (pin "2") (pinfunction "2_2") (pintype "passive"))
      (node (ref "JP36") (pin "1") (pinfunction "1_1") (pintype "passive"))
      (node (ref "JP36") (pin "2") (pinfunction "2_2") (pintype "passive"))
      (node (ref "JP36") (pin "3") (pinfunction "3_3") (pintype "passive"))
      (node (ref "JP36") (pin "4") (pinfunction "4_4") (pintype "passive"))
      (node (ref "JP36") (pin "5") (pinfunction "5_5") (pintype "passive"))
      (node (ref "R50") (pin "2") (pinfunction "2_2") (pintype "passive"))
    )
    (net (code "222") (name "VCC_3") (class "Default")
      (node (ref "C22") (pin "1") (pinfunction "1_1") (pintype "passive"))
      (node (ref "C24") (pin "1") (pinfunction "1_1") (pintype "passive"))
      (node (ref "C31") (pin "1") (pinfunction "1_1") (pintype "passive"))
      (node (ref "C44") (pin "1") (pinfunction "1_1") (pintype "passive"))
      (node (ref "JH62") (pin "1") (pinfunction "1_1") (pintype "passive"))
      (node (ref "JP14") (pin "4") (pinfunction "4_4") (pintype "passive"))
      (node (ref "L1") (pin "2") (pinfunction "2_2") (pintype "passive"))
      (node (ref "L10") (pin "2") (pinfunction "2_2") (pintype "passive"))
      (node (ref "L11") (pin "2") (pinfunction "2_2") (pintype "passive"))
      (node (ref "L12") (pin "2") (pinfunction "2_2") (pintype "passive"))
      (node (ref "L13") (pin "2") (pinfunction "2_2") (pintype "passive"))
      (node (ref "L14") (pin "1") (pinfunction "1_1") (pintype "passive"))
      (node (ref "L2") (pin "1") (pinfunction "1_1") (pintype "passive"))
      (node (ref "L8") (pin "2") (pinfunction "2_2") (pintype "passive"))
      (node (ref "L9") (pin "2") (pinfunction "2_2") (pintype "passive"))
      (node (ref "R33") (pin "1") (pinfunction "1_1") (pintype "passive"))
      (node (ref "R34") (pin "1") (pinfunction "1_1") (pintype "passive"))
      (node (ref "R4") (pin "1") (pinfunction "1_1") (pintype "passive"))
      (node (ref "R67") (pin "2") (pinfunction "2_2") (pintype "passive"))
      (node (ref "R71") (pin "2") (pinfunction "2_2") (pintype "passive"))
      (node (ref "U15") (pin "1") (pinfunction "VOUT_1") (pintype "output"))
      (node (ref "U16") (pin "4") (pinfunction "V+_4") (pintype "input"))
      (node (ref "U39") (pin "4") (pinfunction "V+_4") (pintype "input"))
    )
    (net (code "223") (name "VCC_3_1") (class "Default")
      (node (ref "C10") (pin "2") (pinfunction "2_2") (pintype "passive"))
      (node (ref "C2") (pin "2") (pinfunction "2_2") (pintype "passive"))
      (node (ref "C7") (pin "1") (pinfunction "1_1") (pintype "passive"))
      (node (ref "C8") (pin "2") (pinfunction "2_2") (pintype "passive"))
      (node (ref "C9") (pin "1") (pinfunction "1_1") (pintype "passive"))
      (node (ref "L1") (pin "1") (pinfunction "1_1") (pintype "passive"))
      (node (ref "U2") (pin "10") (pinfunction "VDD_10") (pintype "passive"))
      (node (ref "U2") (pin "19") (pinfunction "AVDD_19") (pintype "passive"))
      (node (ref "U2") (pin "26") (pinfunction "VDD_26") (pintype "passive"))
      (node (ref "U2") (pin "38") (pinfunction "VDD_38") (pintype "passive"))
      (node (ref "U2") (pin "57") (pinfunction "VDD_57") (pintype "passive"))
    )
    (net (code "224") (name "VCC_3_MA") (class "Default")
      (node (ref "C132") (pin "2") (pinfunction "2_2") (pintype "passive"))
      (node (ref "C35") (pin "2") (pinfunction "2_2") (pintype "passive"))
      (node (ref "L9") (pin "1") (pinfunction "1_1") (pintype "passive"))
      (node (ref "U35") (pin "3") (pinfunction "VDD_3") (pintype "passive"))
      (node (ref "U35") (pin "8") (pinfunction "VDD_8") (pintype "passive"))
    )
    (net (code "225") (name "VCC_3_MB") (class "Default")
      (node (ref "C134") (pin "2") (pinfunction "2_2") (pintype "passive"))
      (node (ref "C82") (pin "2") (pinfunction "2_2") (pintype "passive"))
      (node (ref "L10") (pin "1") (pinfunction "1_1") (pintype "passive"))
      (node (ref "U36") (pin "3") (pinfunction "VDD_3") (pintype "passive"))
      (node (ref "U36") (pin "8") (pinfunction "VDD_8") (pintype "passive"))
    )
    (net (code "226") (name "VCC_3_MC") (class "Default")
      (node (ref "C106") (pin "2") (pinfunction "2_2") (pintype "passive"))
      (node (ref "C136") (pin "2") (pinfunction "2_2") (pintype "passive"))
      (node (ref "L11") (pin "1") (pinfunction "1_1") (pintype "passive"))
      (node (ref "U37") (pin "3") (pinfunction "VDD_3") (pintype "passive"))
      (node (ref "U37") (pin "8") (pinfunction "VDD_8") (pintype "passive"))
    )
    (net (code "227") (name "VCC_5") (class "Default")
      (node (ref "C30") (pin "1") (pinfunction "1_1") (pintype "passive"))
      (node (ref "C43") (pin "1") (pinfunction "1_1") (pintype "passive"))
      (node (ref "JH49") (pin "1") (pinfunction "1_1") (pintype "passive"))
      (node (ref "JH51") (pin "1") (pinfunction "1_1") (pintype "passive"))
      (node (ref "JH53") (pin "1") (pinfunction "1_1") (pintype "passive"))
      (node (ref "JH55") (pin "1") (pinfunction "1_1") (pintype "passive"))
      (node (ref "JH57") (pin "1") (pinfunction "1_1") (pintype "passive"))
      (node (ref "JH59") (pin "1") (pinfunction "1_1") (pintype "passive"))
      (node (ref "JH61") (pin "1") (pinfunction "1_1") (pintype "passive"))
      (node (ref "R125") (pin "2") (pinfunction "2_2") (pintype "passive"))
      (node (ref "R144") (pin "2") (pinfunction "2_2") (pintype "passive"))
      (node (ref "R46") (pin "2") (pinfunction "2_2") (pintype "passive"))
      (node (ref "U14") (pin "1") (pinfunction "VOUT_1") (pintype "output"))
      (node (ref "U15") (pin "2") (pinfunction "VIN_2") (pintype "input"))
    )
    (net (code "228") (name "VCC_5_MS") (class "Default")
      (node (ref "C64") (pin "1") (pinfunction "1_1") (pintype "passive"))
      (node (ref "C94") (pin "1") (pinfunction "1_1") (pintype "passive"))
      (node (ref "C95") (pin "2") (pinfunction "2_2") (pintype "passive"))
      (node (ref "C96") (pin "2") (pinfunction "2_2") (pintype "passive"))
      (node (ref "L7") (pin "2") (pinfunction "2_2") (pintype "passive"))
      (node (ref "R77") (pin "2") (pinfunction "2_2") (pintype "passive"))
      (node (ref "U20") (pin "16") (pinfunction "VDD2_16") (pintype "passive"))
      (node (ref "U21") (pin "1") (pinfunction "VDD1_1") (pintype "passive"))
      (node (ref "U23") (pin "1") (pinfunction "VDD1_1") (pintype "passive"))
    )
    (net (code "229") (name "VCC_12") (class "Default")
      (node (ref "C29") (pin "1") (pinfunction "1_1") (pintype "passive"))
      (node (ref "C36") (pin "1") (pinfunction "1_1") (pintype "passive"))
      (node (ref "C50") (pin "1") (pinfunction "1_1") (pintype "passive"))
      (node (ref "JH60") (pin "1") (pinfunction "1_1") (pintype "passive"))
      (node (ref "L6") (pin "2") (pinfunction "2_2") (pintype "passive"))
      (node (ref "R111") (pin "2") (pinfunction "2_2") (pintype "passive"))
      (node (ref "R117") (pin "1") (pinfunction "1_1") (pintype "passive"))
      (node (ref "R119") (pin "1") (pinfunction "1_1") (pintype "passive"))
      (node (ref "R138") (pin "2") (pinfunction "2_2") (pintype "passive"))
      (node (ref "R140") (pin "1") (pinfunction "1_1") (pintype "passive"))
      (node (ref "R165") (pin "2") (pinfunction "2_2") (pintype "passive"))
      (node (ref "R59") (pin "1") (pinfunction "1_1") (pintype "passive"))
      (node (ref "U14") (pin "2") (pinfunction "VIN_2") (pintype "input"))
    )
    (net (code "230") (name "VCC_12_MAH") (class "Default")
      (node (ref "C57") (pin "1") (pinfunction "1_1") (pintype "passive"))
      (node (ref "C60") (pin "2") (pinfunction "2_2") (pintype "passive"))
      (node (ref "D21") (pin "1") (pinfunction "1_1") (pintype "passive"))
      (node (ref "D26") (pin "1") (pinfunction "1_1") (pintype "passive"))
      (node (ref "D27") (pin "1") (pinfunction "1_1") (pintype "passive"))
      (node (ref "U35") (pin "16") (pinfunction "VDDA_16") (pintype "passive"))
    )
    (net (code "231") (name "VCC_12_MAL") (class "Default")
      (node (ref "C131") (pin "2") (pinfunction "2_2") (pintype "passive"))
      (node (ref "C56") (pin "2") (pinfunction "2_2") (pintype "passive"))
      (node (ref "R111") (pin "1") (pinfunction "1_1") (pintype "passive"))
      (node (ref "U35") (pin "11") (pinfunction "VDDB_11") (pintype "passive"))
    )
    (net (code "232") (name "VCC_12_MBH") (class "Default")
      (node (ref "C75") (pin "2") (pinfunction "2_2") (pintype "passive"))
      (node (ref "C87") (pin "1") (pinfunction "1_1") (pintype "passive"))
      (node (ref "D28") (pin "1") (pinfunction "1_1") (pintype "passive"))
      (node (ref "D34") (pin "1") (pinfunction "1_1") (pintype "passive"))
      (node (ref "D35") (pin "1") (pinfunction "1_1") (pintype "passive"))
      (node (ref "U36") (pin "16") (pinfunction "VDDA_16") (pintype "passive"))
    )
    (net (code "233") (name "VCC_12_MBL") (class "Default")
      (node (ref "C133") (pin "2") (pinfunction "2_2") (pintype "passive"))
      (node (ref "C83") (pin "2") (pinfunction "2_2") (pintype "passive"))
      (node (ref "R138") (pin "1") (pinfunction "1_1") (pintype "passive"))
      (node (ref "U36") (pin "11") (pinfunction "VDDB_11") (pintype "passive"))
    )
    (net (code "234") (name "VCC_12_MCH") (class "Default")
      (node (ref "C102") (pin "2") (pinfunction "2_2") (pintype "passive"))
      (node (ref "C108") (pin "1") (pinfunction "1_1") (pintype "passive"))
      (node (ref "D36") (pin "1") (pinfunction "1_1") (pintype "passive"))
      (node (ref "D42") (pin "1") (pinfunction "1_1") (pintype "passive"))
      (node (ref "D43") (pin "1") (pinfunction "1_1") (pintype "passive"))
      (node (ref "U37") (pin "16") (pinfunction "VDDA_16") (pintype "passive"))
    )
    (net (code "235") (name "VCC_12_MCL") (class "Default")
      (node (ref "C107") (pin "2") (pinfunction "2_2") (pintype "passive"))
      (node (ref "C135") (pin "2") (pinfunction "2_2") (pintype "passive"))
      (node (ref "R165") (pin "1") (pinfunction "1_1") (pintype "passive"))
      (node (ref "U37") (pin "11") (pinfunction "VDDB_11") (pintype "passive"))
    )
    (net (code "236") (name "VCC_24") (class "Default")
      (node (ref "D20") (pin "1") (pinfunction "1_1") (pintype "passive"))
      (node (ref "D32") (pin "1") (pinfunction "1_1") (pintype "passive"))
      (node (ref "D39") (pin "1") (pinfunction "1_1") (pintype "passive"))
      (node (ref "F9") (pin "3") (pinfunction "3_3") (pintype "passive"))
      (node (ref "F9") (pin "4") (pinfunction "4_4") (pintype "passive"))
      (node (ref "JP25") (pin "1") (pinfunction "1_1") (pintype "passive"))
      (node (ref "JP25") (pin "2") (pinfunction "2_2") (pintype "passive"))
      (node (ref "JP25") (pin "3") (pinfunction "3_3") (pintype "passive"))
      (node (ref "JP25") (pin "4") (pinfunction "4_4") (pintype "passive"))
      (node (ref "JP25") (pin "5") (pinfunction "5_5") (pintype "passive"))
      (node (ref "JP27") (pin "1") (pinfunction "1_1") (pintype "passive"))
      (node (ref "JP27") (pin "2") (pinfunction "2_2") (pintype "passive"))
      (node (ref "JP27") (pin "3") (pinfunction "3_3") (pintype "passive"))
      (node (ref "JP27") (pin "4") (pinfunction "4_4") (pintype "passive"))
      (node (ref "JP27") (pin "5") (pinfunction "5_5") (pintype "passive"))
      (node (ref "JP29") (pin "1") (pinfunction "1_1") (pintype "passive"))
      (node (ref "JP29") (pin "2") (pinfunction "2_2") (pintype "passive"))
      (node (ref "JP29") (pin "3") (pinfunction "3_3") (pintype "passive"))
      (node (ref "JP29") (pin "4") (pinfunction "4_4") (pintype "passive"))
      (node (ref "JP29") (pin "5") (pinfunction "5_5") (pintype "passive"))
      (node (ref "JP32") (pin "2") (pinfunction "2_2") (pintype "passive"))
      (node (ref "JP34") (pin "2") (pinfunction "2_2") (pintype "passive"))
      (node (ref "JP35") (pin "2") (pinfunction "2_2") (pintype "passive"))
      (node (ref "Q11") (pin "8") (pinfunction "8_8") (pintype "input"))
      (node (ref "Q7") (pin "8") (pinfunction "8_8") (pintype "input"))
      (node (ref "Q9") (pin "8") (pinfunction "8_8") (pintype "input"))
    )
    (net (code "237") (name "unconnected-(JH63-Pad1)") (class "Default")
      (node (ref "JH63") (pin "1") (pinfunction "1_1") (pintype "passive"))
    )
    (net (code "238") (name "unconnected-(JH64-Pad1)") (class "Default")
      (node (ref "JH64") (pin "1") (pinfunction "1_1") (pintype "passive"))
    )
    (net (code "239") (name "unconnected-(JH65-Pad1)") (class "Default")
      (node (ref "JH65") (pin "1") (pinfunction "1_1") (pintype "passive"))
    )
    (net (code "240") (name "unconnected-(JH66-Pad1)") (class "Default")
      (node (ref "JH66") (pin "1") (pinfunction "1_1") (pintype "passive"))
    )
    (net (code "241") (name "unconnected-(JP14-Pad2)") (class "Default")
      (node (ref "JP14") (pin "2") (pinfunction "2_2") (pintype "passive"))
    )
    (net (code "242") (name "unconnected-(JP30-Pad10)") (class "Default")
      (node (ref "JP30") (pin "10") (pinfunction "10_10") (pintype "passive"))
    )
    (net (code "243") (name "unconnected-(U13-SYNC-Pad2)") (class "Default")
      (node (ref "U13") (pin "2") (pinfunction "SYNC_2") (pintype "passive"))
    )
    (net (code "244") (name "unconnected-(U13-Vref-Pad6)") (class "Default")
      (node (ref "U13") (pin "6") (pinfunction "Vref_6") (pintype "passive"))
    )
    (net (code "245") (name "unconnected-(U20-ISODE-Pad10)") (class "Default")
      (node (ref "U20") (pin "10") (pinfunction "ISODE_10") (pintype "passive"))
    )
    (net (code "246") (name "unconnected-(Z48-Pad1)") (class "Default")
      (node (ref "Z48") (pin "1") (pinfunction "1_1") (pintype "passive"))
    )
    (net (code "247") (name "unconnected-(Z53-Pad1)") (class "Default")
      (node (ref "Z53") (pin "1") (pinfunction "1_1") (pintype "passive"))
    )
    (net (code "248") (name "unconnected-(Z56-Pad1)") (class "Default")
      (node (ref "Z56") (pin "1") (pinfunction "1_1") (pintype "passive"))
    )
    (net (code "249") (name "unconnected-(Z57-Pad1)") (class "Default")
      (node (ref "Z57") (pin "1") (pinfunction "1_1") (pintype "passive"))
    )
    (net (code "250") (name "unconnected-(Z58-Pad1)") (class "Default")
      (node (ref "Z58") (pin "1") (pinfunction "1_1") (pintype "passive"))
    )
    (net (code "251") (name "unconnected-(Z59-Pad1)") (class "Default")
      (node (ref "Z59") (pin "1") (pinfunction "1_1") (pintype "passive"))
    )
    (net (code "252") (name "unconnected-(Z60-Pad1)") (class "Default")
      (node (ref "Z60") (pin "1") (pinfunction "1_1") (pintype "passive"))
    )
    (net (code "253") (name "unconnected-(Z64-Pad1)") (class "Default")
      (node (ref "Z64") (pin "1") (pinfunction "1_1") (pintype "passive"))
    )
    (net (code "254") (name "unconnected-(Z71-Pad2)") (class "Default")
      (node (ref "Z71") (pin "2") (pinfunction "2_2") (pintype "passive"))
    )
    (net (code "255") (name "unconnected-(Z75-Pad2)") (class "Default")
      (node (ref "Z75") (pin "2") (pinfunction "2_2") (pintype "passive"))
    )
    (net (code "256") (name "unconnected-(Z77-Pad2)") (class "Default")
      (node (ref "Z77") (pin "2") (pinfunction "2_2") (pintype "passive"))
    )
    (net (code "257") (name "unconnected-(Z79-Pad2)") (class "Default")
      (node (ref "Z79") (pin "2") (pinfunction "2_2") (pintype "passive"))
    )
    (net (code "258") (name "unconnected-(Z81-Pad2)") (class "Default")
      (node (ref "Z81") (pin "2") (pinfunction "2_2") (pintype "passive"))
    )
    (net (code "259") (name "unconnected-(Z89-Pad2)") (class "Default")
      (node (ref "Z89") (pin "2") (pinfunction "2_2") (pintype "passive"))
    )
  )
)
